# BreakOutBoard_Cyclone.net
KiCad netlist of a schematic drawn in Altium Designer
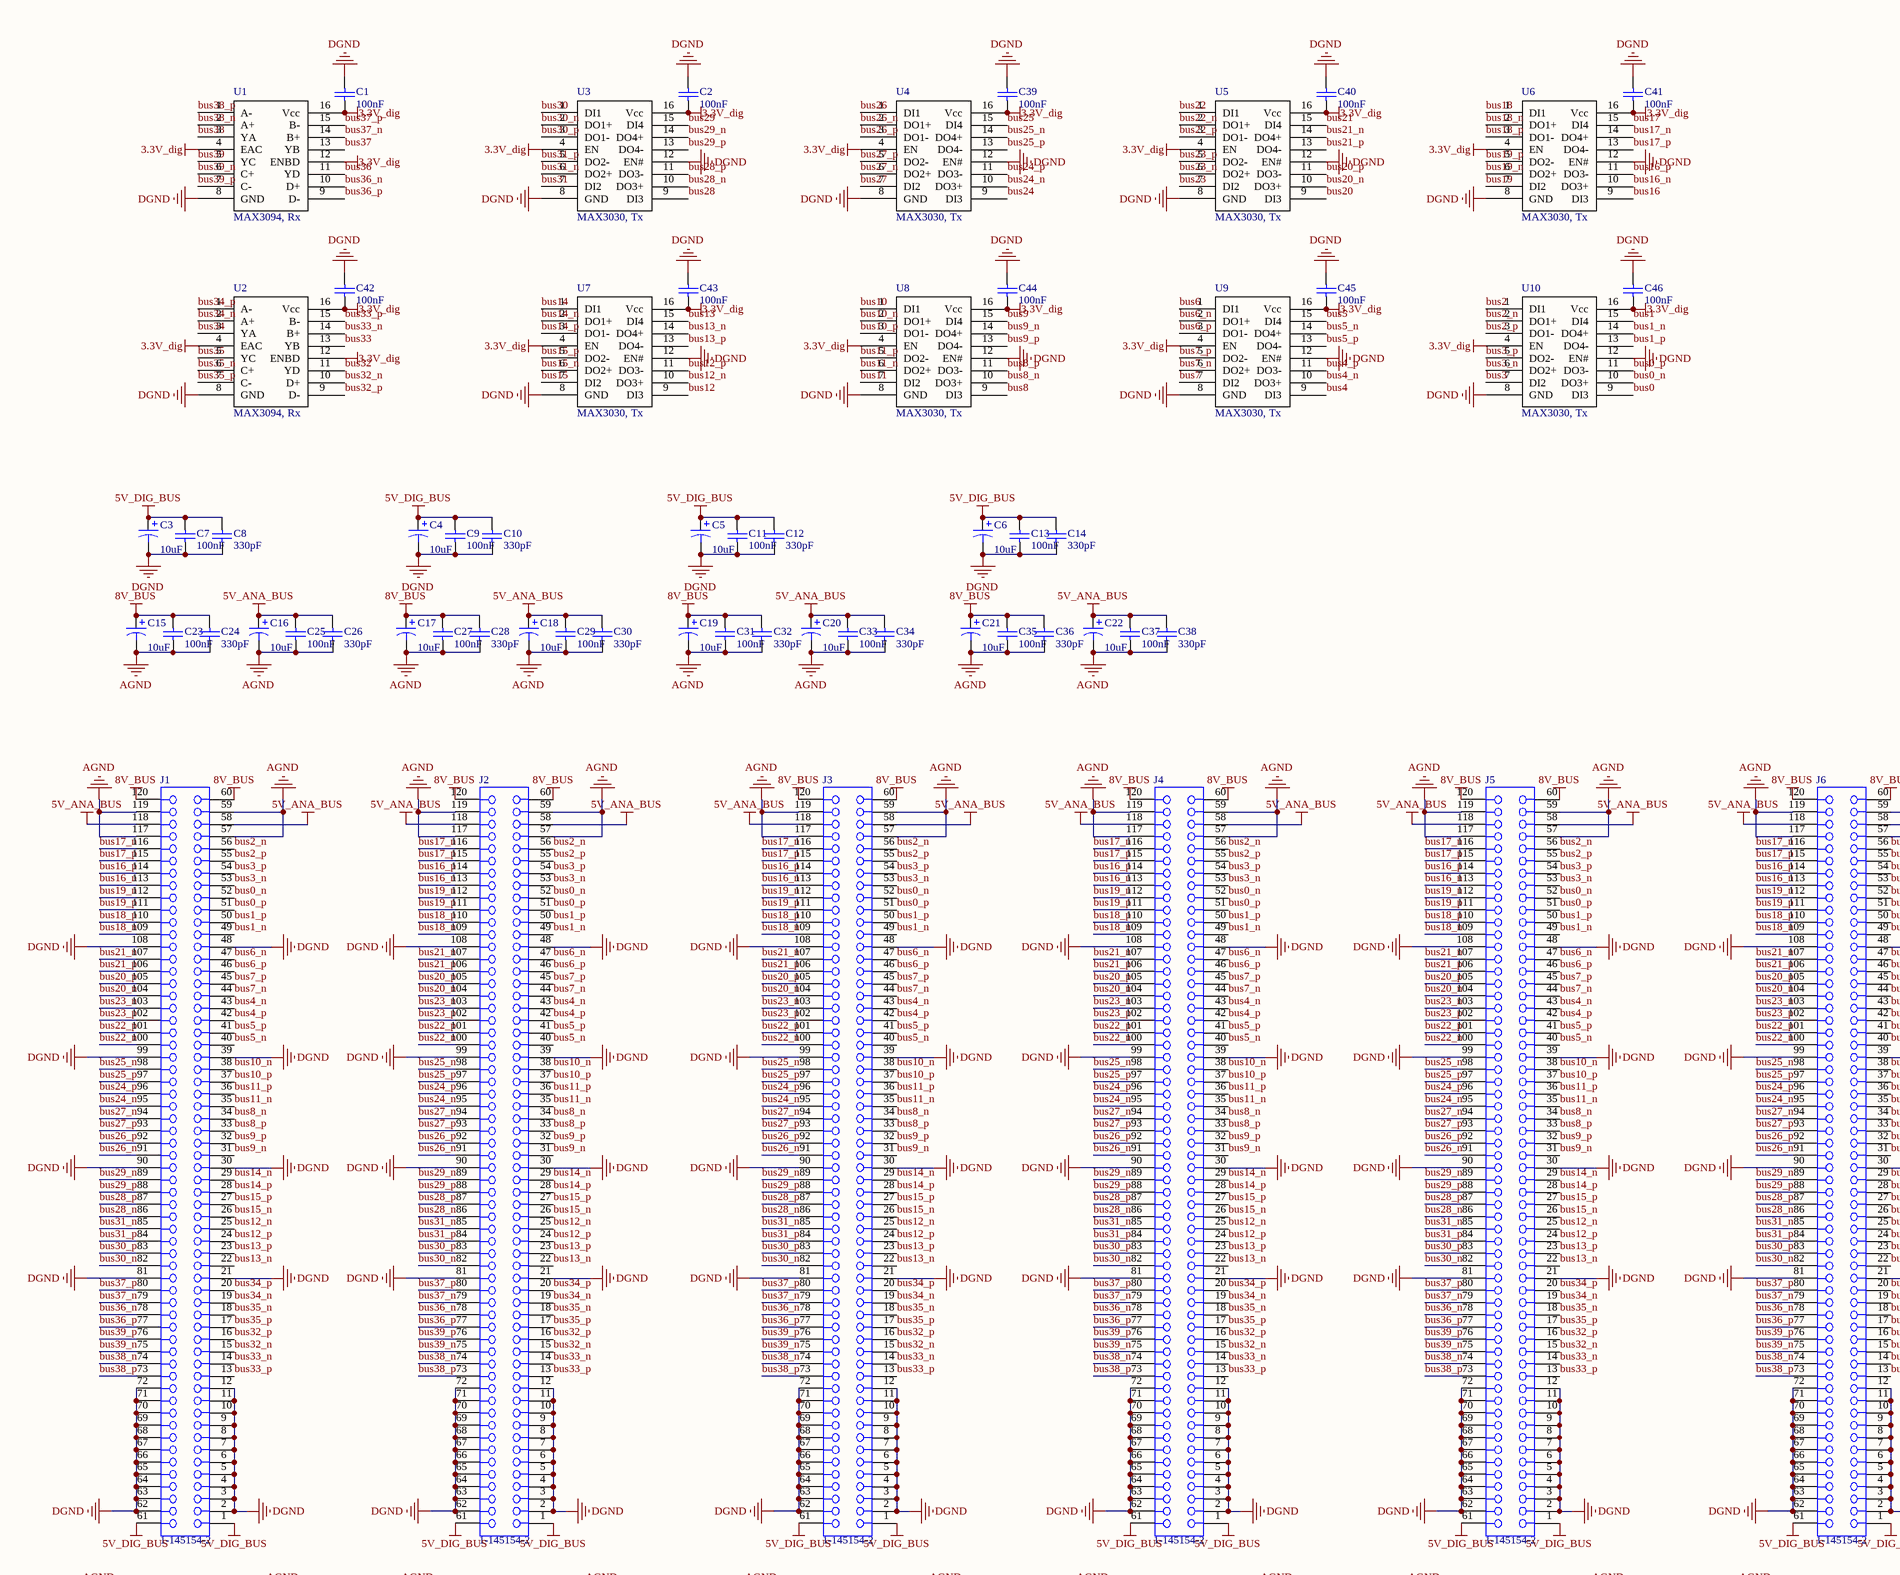
[diagram p0: BreakOutBoard_Cyclone.SchDoc, top left]
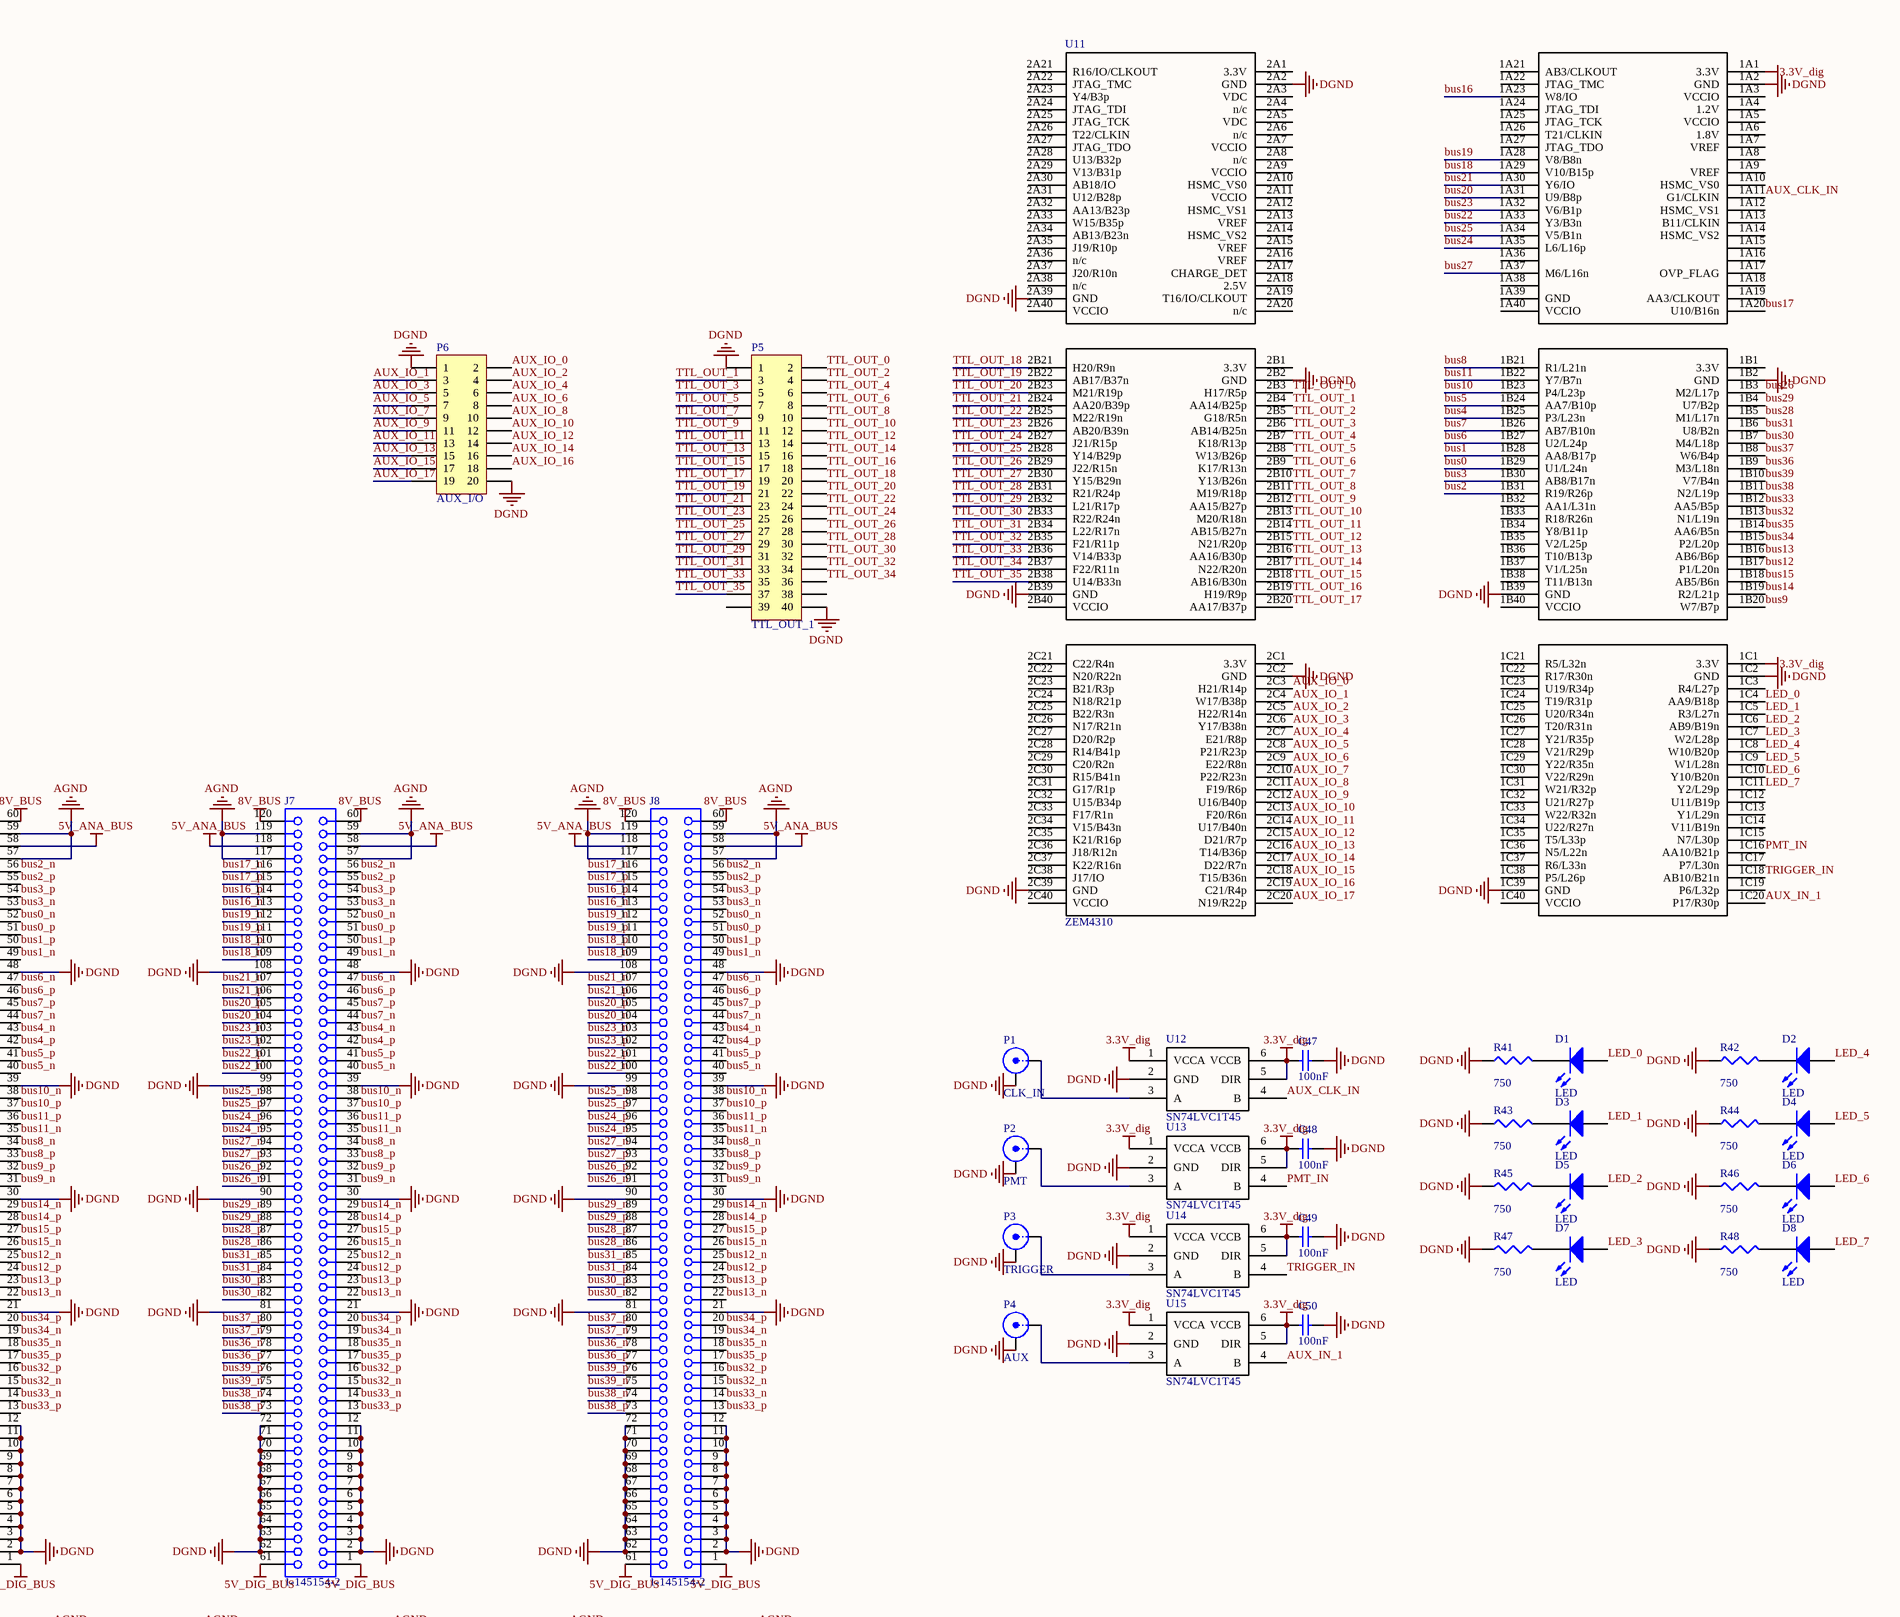
[diagram p1: BreakOutBoard_Cyclone.SchDoc, top right]
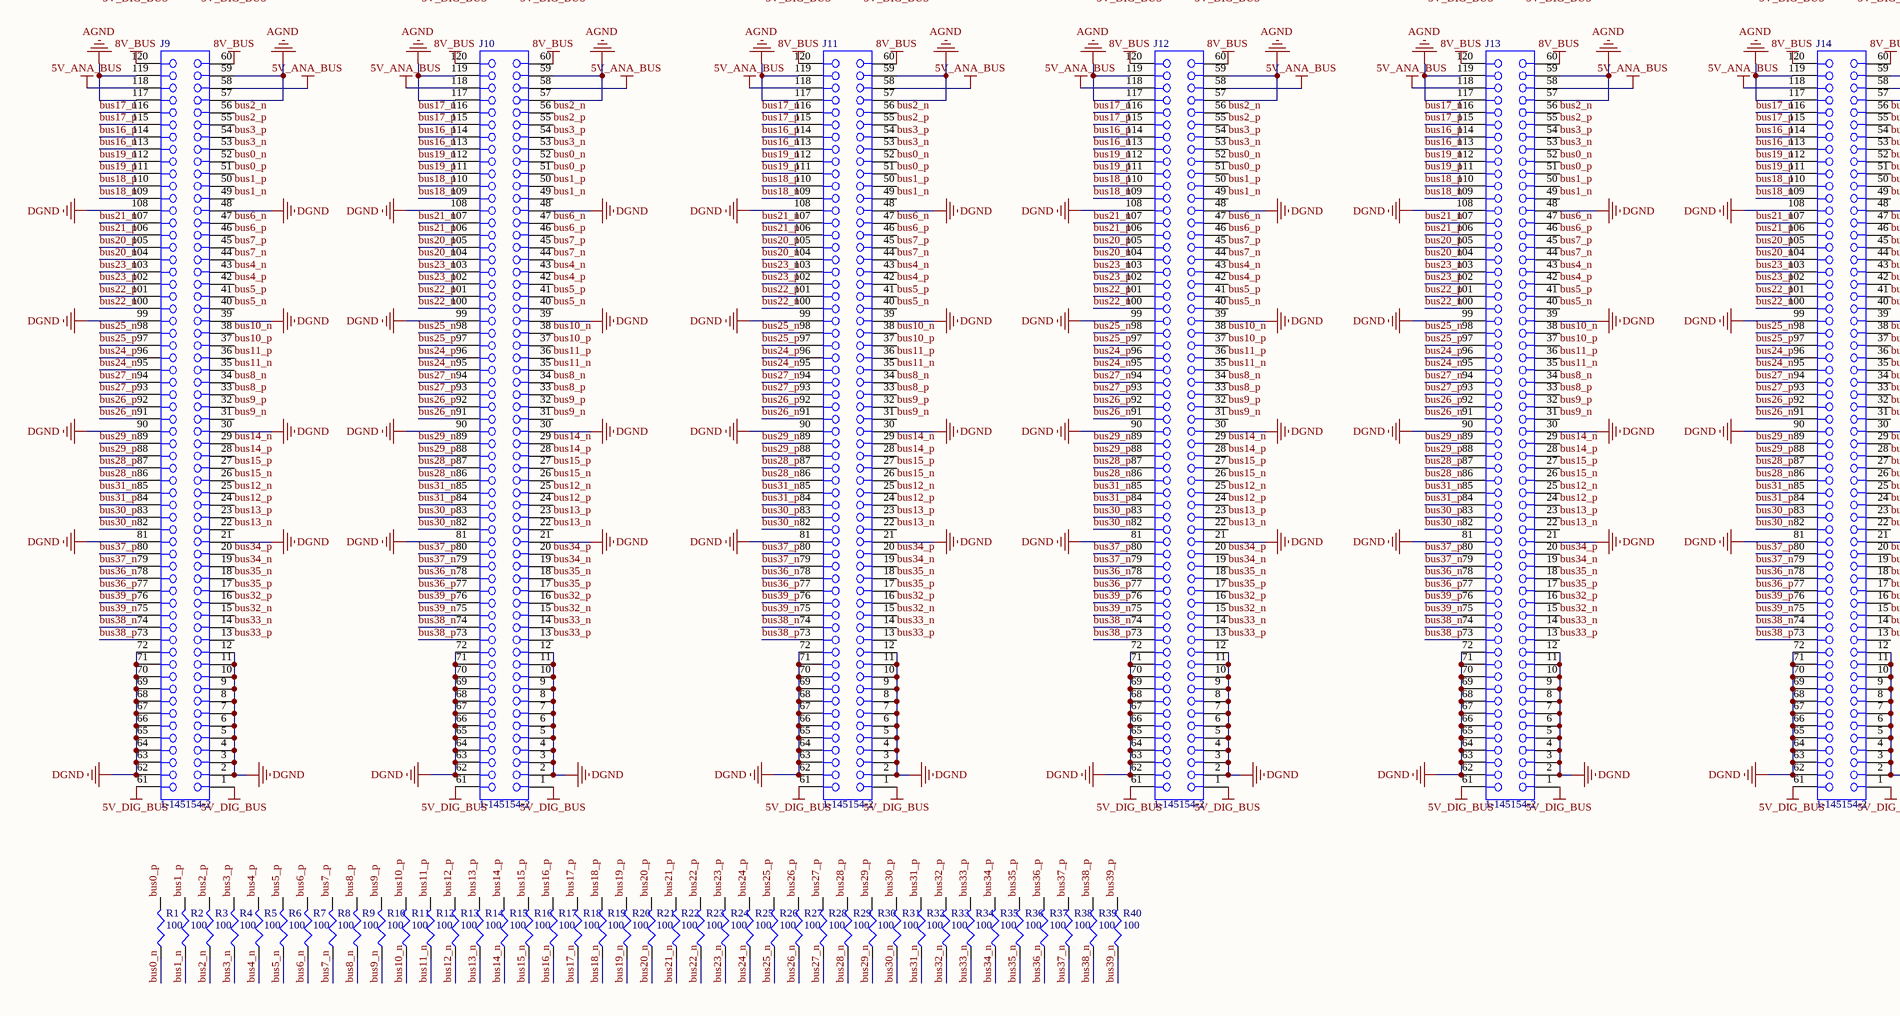
[diagram p2: BreakOutBoard_Cyclone.SchDoc, bottom left]
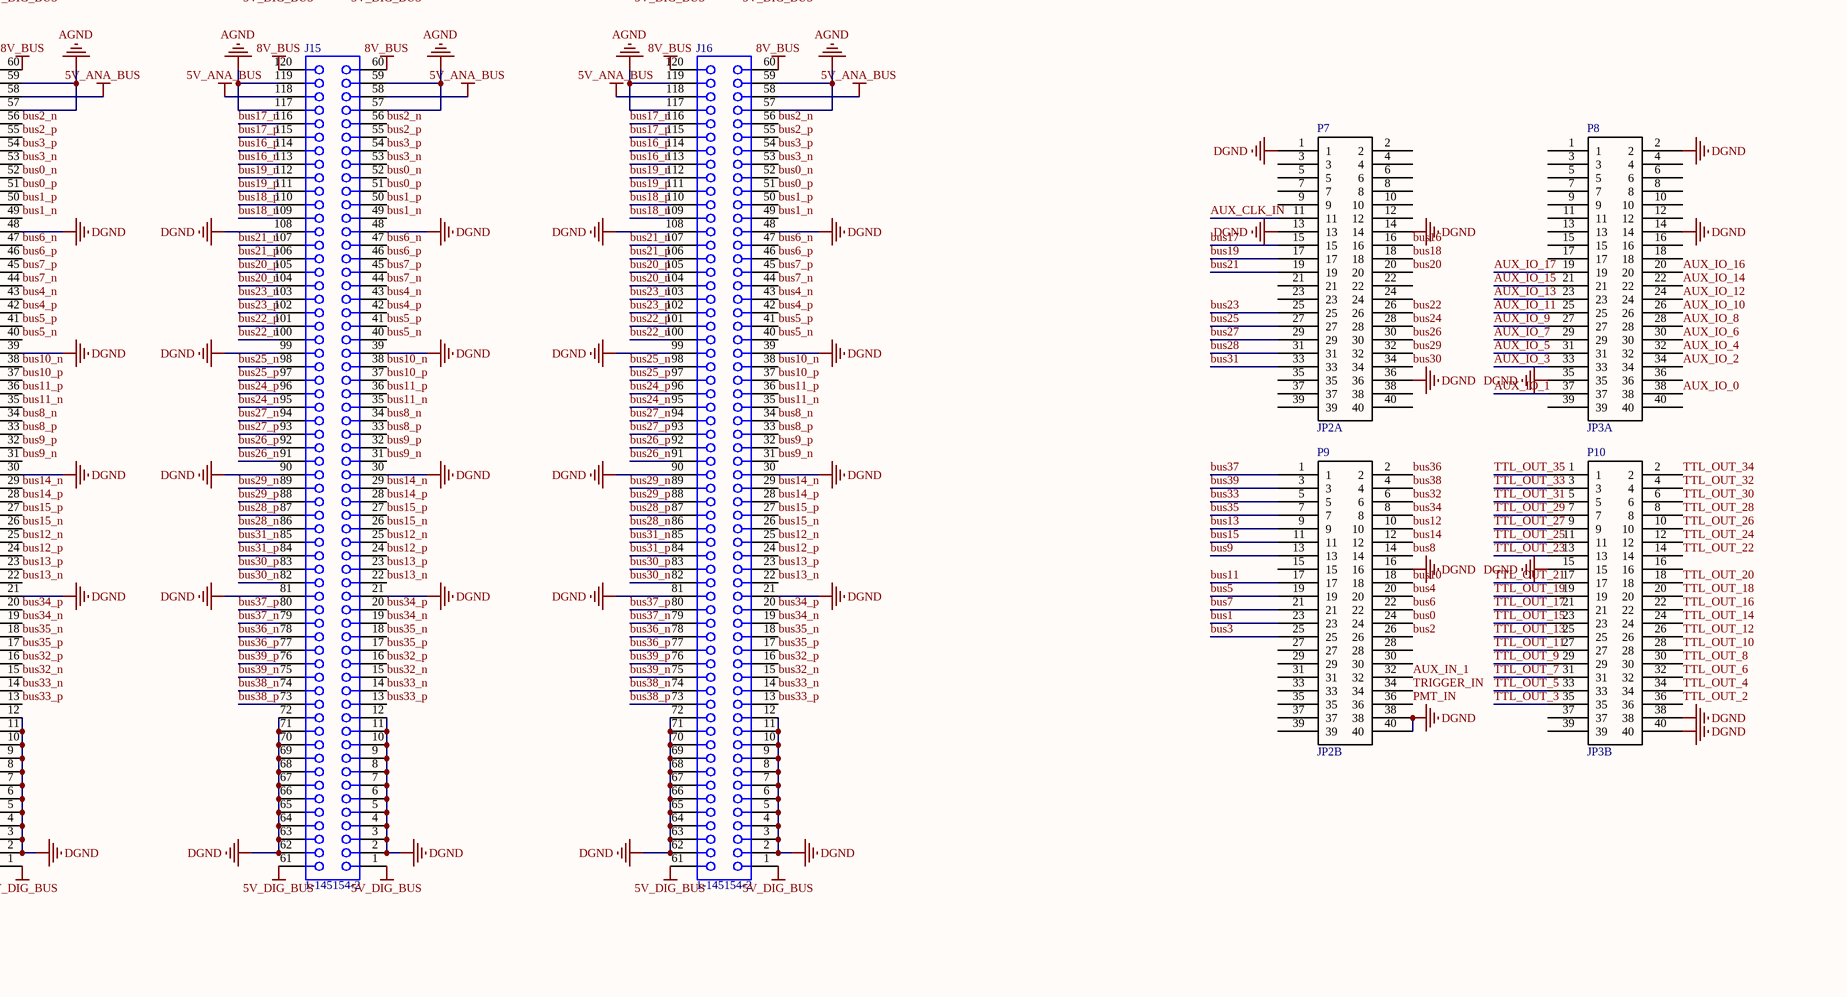
[diagram p3: BreakOutBoard_Cyclone.SchDoc, bottom right]

(export (version "E")
  (design (tool "Eeschema 10.0.6"))
  (components
    (comp (ref "C1")
      (value "100nF")
      (footprint "CAPC2012L")
      (description "Capacitor (Semiconductor SIM Model)")
      (fields (field (name "Comment") "Cap Semi") (field (name "PUBLISHER") "Altium Limited"))
      (libsource (lib "Miscellaneous Devices") (part "Cap Semi"))
    )
    (comp (ref "C2")
      (value "100nF")
      (footprint "CAPC2012L")
      (description "Capacitor (Semiconductor SIM Model)")
      (fields (field (name "Comment") "Cap Semi") (field (name "PUBLISHER") "Altium Limited"))
      (libsource (lib "Miscellaneous Devices") (part "Cap Semi"))
    )
    (comp (ref "C3")
      (value "10uF")
      (footprint "B")
      (description "Polarized Capacitor (Radial)")
      (fields
        (field (name "VOLTAGE") "16V")
        (field (name "Comment") "Cap Pol1")
        (field (name "PUBLISHER") "Altium Limited")
      )
      (libsource (lib "Miscellaneous Devices") (part "Cap Pol1"))
    )
    (comp (ref "C4")
      (value "10uF")
      (footprint "B")
      (description "Polarized Capacitor (Radial)")
      (fields
        (field (name "VOLTAGE") "16V")
        (field (name "Comment") "Cap Pol1")
        (field (name "PUBLISHER") "Altium Limited")
      )
      (libsource (lib "Miscellaneous Devices") (part "Cap Pol1"))
    )
    (comp (ref "C5")
      (value "10uF")
      (footprint "B")
      (description "Polarized Capacitor (Radial)")
      (fields
        (field (name "VOLTAGE") "16V")
        (field (name "Comment") "Cap Pol1")
        (field (name "PUBLISHER") "Altium Limited")
      )
      (libsource (lib "Miscellaneous Devices") (part "Cap Pol1"))
    )
    (comp (ref "C6")
      (value "10uF")
      (footprint "B")
      (description "Polarized Capacitor (Radial)")
      (fields
        (field (name "VOLTAGE") "16V")
        (field (name "Comment") "Cap Pol1")
        (field (name "PUBLISHER") "Altium Limited")
      )
      (libsource (lib "Miscellaneous Devices") (part "Cap Pol1"))
    )
    (comp (ref "C7")
      (value "100nF")
      (footprint "CAPC2012L")
      (description "Capacitor (Semiconductor SIM Model)")
      (fields (field (name "Comment") "Cap Semi") (field (name "PUBLISHER") "Altium Limited"))
      (libsource (lib "Miscellaneous Devices") (part "Cap Semi"))
    )
    (comp (ref "C8")
      (value "330pF")
      (footprint "CAPC2012L")
      (description "Capacitor (Semiconductor SIM Model)")
      (fields (field (name "Comment") "Cap Semi") (field (name "PUBLISHER") "Altium Limited"))
      (libsource (lib "Miscellaneous Devices") (part "Cap Semi"))
    )
    (comp (ref "C9")
      (value "100nF")
      (footprint "CAPC2012L")
      (description "Capacitor (Semiconductor SIM Model)")
      (fields (field (name "Comment") "Cap Semi") (field (name "PUBLISHER") "Altium Limited"))
      (libsource (lib "Miscellaneous Devices") (part "Cap Semi"))
    )
    (comp (ref "C10")
      (value "330pF")
      (footprint "CAPC2012L")
      (description "Capacitor (Semiconductor SIM Model)")
      (fields (field (name "Comment") "Cap Semi") (field (name "PUBLISHER") "Altium Limited"))
      (libsource (lib "Miscellaneous Devices") (part "Cap Semi"))
    )
    (comp (ref "C11")
      (value "100nF")
      (footprint "CAPC2012L")
      (description "Capacitor (Semiconductor SIM Model)")
      (fields (field (name "Comment") "Cap Semi") (field (name "PUBLISHER") "Altium Limited"))
      (libsource (lib "Miscellaneous Devices") (part "Cap Semi"))
    )
    (comp (ref "C12")
      (value "330pF")
      (footprint "CAPC2012L")
      (description "Capacitor (Semiconductor SIM Model)")
      (fields (field (name "Comment") "Cap Semi") (field (name "PUBLISHER") "Altium Limited"))
      (libsource (lib "Miscellaneous Devices") (part "Cap Semi"))
    )
    (comp (ref "C13")
      (value "100nF")
      (footprint "CAPC2012L")
      (description "Capacitor (Semiconductor SIM Model)")
      (fields (field (name "Comment") "Cap Semi") (field (name "PUBLISHER") "Altium Limited"))
      (libsource (lib "Miscellaneous Devices") (part "Cap Semi"))
    )
    (comp (ref "C14")
      (value "330pF")
      (footprint "CAPC2012L")
      (description "Capacitor (Semiconductor SIM Model)")
      (fields (field (name "Comment") "Cap Semi") (field (name "PUBLISHER") "Altium Limited"))
      (libsource (lib "Miscellaneous Devices") (part "Cap Semi"))
    )
    (comp (ref "C15")
      (value "10uF")
      (footprint "B")
      (description "Polarized Capacitor (Radial)")
      (fields
        (field (name "VOLTAGE") "16V")
        (field (name "Comment") "Cap Pol1")
        (field (name "PUBLISHER") "Altium Limited")
      )
      (libsource (lib "Miscellaneous Devices") (part "Cap Pol1"))
    )
    (comp (ref "C16")
      (value "10uF")
      (footprint "B")
      (description "Polarized Capacitor (Radial)")
      (fields
        (field (name "VOLTAGE") "16V")
        (field (name "Comment") "Cap Pol1")
        (field (name "PUBLISHER") "Altium Limited")
      )
      (libsource (lib "Miscellaneous Devices") (part "Cap Pol1"))
    )
    (comp (ref "C17")
      (value "10uF")
      (footprint "B")
      (description "Polarized Capacitor (Radial)")
      (fields
        (field (name "VOLTAGE") "16V")
        (field (name "Comment") "Cap Pol1")
        (field (name "PUBLISHER") "Altium Limited")
      )
      (libsource (lib "Miscellaneous Devices") (part "Cap Pol1"))
    )
    (comp (ref "C18")
      (value "10uF")
      (footprint "B")
      (description "Polarized Capacitor (Radial)")
      (fields
        (field (name "VOLTAGE") "16V")
        (field (name "Comment") "Cap Pol1")
        (field (name "PUBLISHER") "Altium Limited")
      )
      (libsource (lib "Miscellaneous Devices") (part "Cap Pol1"))
    )
    (comp (ref "C19")
      (value "10uF")
      (footprint "B")
      (description "Polarized Capacitor (Radial)")
      (fields
        (field (name "VOLTAGE") "16V")
        (field (name "Comment") "Cap Pol1")
        (field (name "PUBLISHER") "Altium Limited")
      )
      (libsource (lib "Miscellaneous Devices") (part "Cap Pol1"))
    )
    (comp (ref "C20")
      (value "10uF")
      (footprint "B")
      (description "Polarized Capacitor (Radial)")
      (fields
        (field (name "VOLTAGE") "16V")
        (field (name "Comment") "Cap Pol1")
        (field (name "PUBLISHER") "Altium Limited")
      )
      (libsource (lib "Miscellaneous Devices") (part "Cap Pol1"))
    )
    (comp (ref "C21")
      (value "10uF")
      (footprint "B")
      (description "Polarized Capacitor (Radial)")
      (fields
        (field (name "VOLTAGE") "16V")
        (field (name "Comment") "Cap Pol1")
        (field (name "PUBLISHER") "Altium Limited")
      )
      (libsource (lib "Miscellaneous Devices") (part "Cap Pol1"))
    )
    (comp (ref "C22")
      (value "10uF")
      (footprint "B")
      (description "Polarized Capacitor (Radial)")
      (fields
        (field (name "VOLTAGE") "16V")
        (field (name "Comment") "Cap Pol1")
        (field (name "PUBLISHER") "Altium Limited")
      )
      (libsource (lib "Miscellaneous Devices") (part "Cap Pol1"))
    )
    (comp (ref "C23")
      (value "100nF")
      (footprint "CAPC2012L")
      (description "Capacitor (Semiconductor SIM Model)")
      (fields (field (name "Comment") "Cap Semi") (field (name "PUBLISHER") "Altium Limited"))
      (libsource (lib "Miscellaneous Devices") (part "Cap Semi"))
    )
    (comp (ref "C24")
      (value "330pF")
      (footprint "CAPC2012L")
      (description "Capacitor (Semiconductor SIM Model)")
      (fields (field (name "Comment") "Cap Semi") (field (name "PUBLISHER") "Altium Limited"))
      (libsource (lib "Miscellaneous Devices") (part "Cap Semi"))
    )
    (comp (ref "C25")
      (value "100nF")
      (footprint "CAPC2012L")
      (description "Capacitor (Semiconductor SIM Model)")
      (fields (field (name "Comment") "Cap Semi") (field (name "PUBLISHER") "Altium Limited"))
      (libsource (lib "Miscellaneous Devices") (part "Cap Semi"))
    )
    (comp (ref "C26")
      (value "330pF")
      (footprint "CAPC2012L")
      (description "Capacitor (Semiconductor SIM Model)")
      (fields (field (name "Comment") "Cap Semi") (field (name "PUBLISHER") "Altium Limited"))
      (libsource (lib "Miscellaneous Devices") (part "Cap Semi"))
    )
    (comp (ref "C27")
      (value "100nF")
      (footprint "CAPC2012L")
      (description "Capacitor (Semiconductor SIM Model)")
      (fields (field (name "Comment") "Cap Semi") (field (name "PUBLISHER") "Altium Limited"))
      (libsource (lib "Miscellaneous Devices") (part "Cap Semi"))
    )
    (comp (ref "C28")
      (value "330pF")
      (footprint "CAPC2012L")
      (description "Capacitor (Semiconductor SIM Model)")
      (fields (field (name "Comment") "Cap Semi") (field (name "PUBLISHER") "Altium Limited"))
      (libsource (lib "Miscellaneous Devices") (part "Cap Semi"))
    )
    (comp (ref "C29")
      (value "100nF")
      (footprint "CAPC2012L")
      (description "Capacitor (Semiconductor SIM Model)")
      (fields (field (name "Comment") "Cap Semi") (field (name "PUBLISHER") "Altium Limited"))
      (libsource (lib "Miscellaneous Devices") (part "Cap Semi"))
    )
    (comp (ref "C30")
      (value "330pF")
      (footprint "CAPC2012L")
      (description "Capacitor (Semiconductor SIM Model)")
      (fields (field (name "Comment") "Cap Semi") (field (name "PUBLISHER") "Altium Limited"))
      (libsource (lib "Miscellaneous Devices") (part "Cap Semi"))
    )
    (comp (ref "C31")
      (value "100nF")
      (footprint "CAPC2012L")
      (description "Capacitor (Semiconductor SIM Model)")
      (fields (field (name "Comment") "Cap Semi") (field (name "PUBLISHER") "Altium Limited"))
      (libsource (lib "Miscellaneous Devices") (part "Cap Semi"))
    )
    (comp (ref "C32")
      (value "330pF")
      (footprint "CAPC2012L")
      (description "Capacitor (Semiconductor SIM Model)")
      (fields (field (name "Comment") "Cap Semi") (field (name "PUBLISHER") "Altium Limited"))
      (libsource (lib "Miscellaneous Devices") (part "Cap Semi"))
    )
    (comp (ref "C33")
      (value "100nF")
      (footprint "CAPC2012L")
      (description "Capacitor (Semiconductor SIM Model)")
      (fields (field (name "Comment") "Cap Semi") (field (name "PUBLISHER") "Altium Limited"))
      (libsource (lib "Miscellaneous Devices") (part "Cap Semi"))
    )
    (comp (ref "C34")
      (value "330pF")
      (footprint "CAPC2012L")
      (description "Capacitor (Semiconductor SIM Model)")
      (fields (field (name "Comment") "Cap Semi") (field (name "PUBLISHER") "Altium Limited"))
      (libsource (lib "Miscellaneous Devices") (part "Cap Semi"))
    )
    (comp (ref "C35")
      (value "100nF")
      (footprint "CAPC2012L")
      (description "Capacitor (Semiconductor SIM Model)")
      (fields (field (name "Comment") "Cap Semi") (field (name "PUBLISHER") "Altium Limited"))
      (libsource (lib "Miscellaneous Devices") (part "Cap Semi"))
    )
    (comp (ref "C36")
      (value "330pF")
      (footprint "CAPC2012L")
      (description "Capacitor (Semiconductor SIM Model)")
      (fields (field (name "Comment") "Cap Semi") (field (name "PUBLISHER") "Altium Limited"))
      (libsource (lib "Miscellaneous Devices") (part "Cap Semi"))
    )
    (comp (ref "C37")
      (value "100nF")
      (footprint "CAPC2012L")
      (description "Capacitor (Semiconductor SIM Model)")
      (fields (field (name "Comment") "Cap Semi") (field (name "PUBLISHER") "Altium Limited"))
      (libsource (lib "Miscellaneous Devices") (part "Cap Semi"))
    )
    (comp (ref "C38")
      (value "330pF")
      (footprint "CAPC2012L")
      (description "Capacitor (Semiconductor SIM Model)")
      (fields (field (name "Comment") "Cap Semi") (field (name "PUBLISHER") "Altium Limited"))
      (libsource (lib "Miscellaneous Devices") (part "Cap Semi"))
    )
    (comp (ref "C39")
      (value "100nF")
      (footprint "CAPC2012L")
      (description "Capacitor (Semiconductor SIM Model)")
      (fields (field (name "Comment") "Cap Semi") (field (name "PUBLISHER") "Altium Limited"))
      (libsource (lib "Miscellaneous Devices") (part "Cap Semi"))
    )
    (comp (ref "C40")
      (value "100nF")
      (footprint "CAPC2012L")
      (description "Capacitor (Semiconductor SIM Model)")
      (fields (field (name "Comment") "Cap Semi") (field (name "PUBLISHER") "Altium Limited"))
      (libsource (lib "Miscellaneous Devices") (part "Cap Semi"))
    )
    (comp (ref "C41")
      (value "100nF")
      (footprint "CAPC2012L")
      (description "Capacitor (Semiconductor SIM Model)")
      (fields (field (name "Comment") "Cap Semi") (field (name "PUBLISHER") "Altium Limited"))
      (libsource (lib "Miscellaneous Devices") (part "Cap Semi"))
    )
    (comp (ref "C42")
      (value "100nF")
      (footprint "CAPC2012L")
      (description "Capacitor (Semiconductor SIM Model)")
      (fields (field (name "Comment") "Cap Semi") (field (name "PUBLISHER") "Altium Limited"))
      (libsource (lib "Miscellaneous Devices") (part "Cap Semi"))
    )
    (comp (ref "C43")
      (value "100nF")
      (footprint "CAPC2012L")
      (description "Capacitor (Semiconductor SIM Model)")
      (fields (field (name "Comment") "Cap Semi") (field (name "PUBLISHER") "Altium Limited"))
      (libsource (lib "Miscellaneous Devices") (part "Cap Semi"))
    )
    (comp (ref "C44")
      (value "100nF")
      (footprint "CAPC2012L")
      (description "Capacitor (Semiconductor SIM Model)")
      (fields (field (name "Comment") "Cap Semi") (field (name "PUBLISHER") "Altium Limited"))
      (libsource (lib "Miscellaneous Devices") (part "Cap Semi"))
    )
    (comp (ref "C45")
      (value "100nF")
      (footprint "CAPC2012L")
      (description "Capacitor (Semiconductor SIM Model)")
      (fields (field (name "Comment") "Cap Semi") (field (name "PUBLISHER") "Altium Limited"))
      (libsource (lib "Miscellaneous Devices") (part "Cap Semi"))
    )
    (comp (ref "C46")
      (value "100nF")
      (footprint "CAPC2012L")
      (description "Capacitor (Semiconductor SIM Model)")
      (fields (field (name "Comment") "Cap Semi") (field (name "PUBLISHER") "Altium Limited"))
      (libsource (lib "Miscellaneous Devices") (part "Cap Semi"))
    )
    (comp (ref "C47")
      (value "100nF")
      (footprint "CAPC2012L")
      (description "Capacitor (Semiconductor SIM Model)")
      (fields (field (name "Comment") "Cap Semi") (field (name "PUBLISHER") "Altium Limited"))
      (libsource (lib "Miscellaneous Devices") (part "Cap Semi"))
    )
    (comp (ref "C48")
      (value "100nF")
      (footprint "CAPC2012L")
      (description "Capacitor (Semiconductor SIM Model)")
      (fields (field (name "Comment") "Cap Semi") (field (name "PUBLISHER") "Altium Limited"))
      (libsource (lib "Miscellaneous Devices") (part "Cap Semi"))
    )
    (comp (ref "C49")
      (value "100nF")
      (footprint "CAPC2012L")
      (description "Capacitor (Semiconductor SIM Model)")
      (fields (field (name "Comment") "Cap Semi") (field (name "PUBLISHER") "Altium Limited"))
      (libsource (lib "Miscellaneous Devices") (part "Cap Semi"))
    )
    (comp (ref "C50")
      (value "100nF")
      (footprint "CAPC2012L")
      (description "Capacitor (Semiconductor SIM Model)")
      (fields (field (name "Comment") "Cap Semi") (field (name "PUBLISHER") "Altium Limited"))
      (libsource (lib "Miscellaneous Devices") (part "Cap Semi"))
    )
    (comp (ref "D1")
      (value "LED")
      (footprint "RESC2012M")
      (description "Typical BLUE SiC LED")
      (fields (field (name "PUBLISHER") "Altium Limited"))
      (libsource (lib "Miscellaneous Devices") (part "LED3"))
    )
    (comp (ref "D2")
      (value "LED")
      (footprint "RESC2012M")
      (description "Typical BLUE SiC LED")
      (fields (field (name "PUBLISHER") "Altium Limited"))
      (libsource (lib "Miscellaneous Devices") (part "LED3"))
    )
    (comp (ref "D3")
      (value "LED")
      (footprint "RESC2012M")
      (description "Typical BLUE SiC LED")
      (fields (field (name "PUBLISHER") "Altium Limited"))
      (libsource (lib "Miscellaneous Devices") (part "LED3"))
    )
    (comp (ref "D4")
      (value "LED")
      (footprint "RESC2012M")
      (description "Typical BLUE SiC LED")
      (fields (field (name "PUBLISHER") "Altium Limited"))
      (libsource (lib "Miscellaneous Devices") (part "LED3"))
    )
    (comp (ref "D5")
      (value "LED")
      (footprint "RESC2012M")
      (description "Typical BLUE SiC LED")
      (fields (field (name "PUBLISHER") "Altium Limited"))
      (libsource (lib "Miscellaneous Devices") (part "LED3"))
    )
    (comp (ref "D6")
      (value "LED")
      (footprint "RESC2012M")
      (description "Typical BLUE SiC LED")
      (fields (field (name "PUBLISHER") "Altium Limited"))
      (libsource (lib "Miscellaneous Devices") (part "LED3"))
    )
    (comp (ref "D7")
      (value "LED")
      (footprint "RESC2012M")
      (description "Typical BLUE SiC LED")
      (fields (field (name "PUBLISHER") "Altium Limited"))
      (libsource (lib "Miscellaneous Devices") (part "LED3"))
    )
    (comp (ref "D8")
      (value "LED")
      (footprint "RESC2012M")
      (description "Typical BLUE SiC LED")
      (fields (field (name "PUBLISHER") "Altium Limited"))
      (libsource (lib "Miscellaneous Devices") (part "LED3"))
    )
    (comp (ref "J1")
      (value "1-145154-2")
      (footprint "1-145154-2")
      (description "Connector Assembly, 60 Dual Position, 1.27 [.050] Series, Standard Edge")
      (fields (field (name "VOLTAGE") "3.3V, 5V") (field (name "PUBLISHER") "Altium Limited"))
      (libsource (lib "AMP Card Edge 050 Series PCI") (part "1-145154-2"))
    )
    (comp (ref "J2")
      (value "1-145154-2")
      (footprint "1-145154-2")
      (description "Connector Assembly, 60 Dual Position, 1.27 [.050] Series, Standard Edge")
      (fields (field (name "VOLTAGE") "3.3V, 5V") (field (name "PUBLISHER") "Altium Limited"))
      (libsource (lib "AMP Card Edge 050 Series PCI") (part "1-145154-2"))
    )
    (comp (ref "J3")
      (value "1-145154-2")
      (footprint "1-145154-2")
      (description "Connector Assembly, 60 Dual Position, 1.27 [.050] Series, Standard Edge")
      (fields (field (name "VOLTAGE") "3.3V, 5V") (field (name "PUBLISHER") "Altium Limited"))
      (libsource (lib "AMP Card Edge 050 Series PCI") (part "1-145154-2"))
    )
    (comp (ref "J4")
      (value "1-145154-2")
      (footprint "1-145154-2")
      (description "Connector Assembly, 60 Dual Position, 1.27 [.050] Series, Standard Edge")
      (fields (field (name "VOLTAGE") "3.3V, 5V") (field (name "PUBLISHER") "Altium Limited"))
      (libsource (lib "AMP Card Edge 050 Series PCI") (part "1-145154-2"))
    )
    (comp (ref "J5")
      (value "1-145154-2")
      (footprint "1-145154-2")
      (description "Connector Assembly, 60 Dual Position, 1.27 [.050] Series, Standard Edge")
      (fields (field (name "VOLTAGE") "3.3V, 5V") (field (name "PUBLISHER") "Altium Limited"))
      (libsource (lib "AMP Card Edge 050 Series PCI") (part "1-145154-2"))
    )
    (comp (ref "J6")
      (value "1-145154-2")
      (footprint "1-145154-2")
      (description "Connector Assembly, 60 Dual Position, 1.27 [.050] Series, Standard Edge")
      (fields (field (name "VOLTAGE") "3.3V, 5V") (field (name "PUBLISHER") "Altium Limited"))
      (libsource (lib "AMP Card Edge 050 Series PCI") (part "1-145154-2"))
    )
    (comp (ref "J7")
      (value "1-145154-2")
      (footprint "1-145154-2")
      (description "Connector Assembly, 60 Dual Position, 1.27 [.050] Series, Standard Edge")
      (fields (field (name "VOLTAGE") "3.3V, 5V") (field (name "PUBLISHER") "Altium Limited"))
      (libsource (lib "AMP Card Edge 050 Series PCI") (part "1-145154-2"))
    )
    (comp (ref "J8")
      (value "1-145154-2")
      (footprint "1-145154-2")
      (description "Connector Assembly, 60 Dual Position, 1.27 [.050] Series, Standard Edge")
      (fields (field (name "VOLTAGE") "3.3V, 5V") (field (name "PUBLISHER") "Altium Limited"))
      (libsource (lib "AMP Card Edge 050 Series PCI") (part "1-145154-2"))
    )
    (comp (ref "J9")
      (value "1-145154-2")
      (footprint "1-145154-2")
      (description "Connector Assembly, 60 Dual Position, 1.27 [.050] Series, Standard Edge")
      (fields (field (name "VOLTAGE") "3.3V, 5V") (field (name "PUBLISHER") "Altium Limited"))
      (libsource (lib "AMP Card Edge 050 Series PCI") (part "1-145154-2"))
    )
    (comp (ref "J10")
      (value "1-145154-2")
      (footprint "1-145154-2")
      (description "Connector Assembly, 60 Dual Position, 1.27 [.050] Series, Standard Edge")
      (fields (field (name "VOLTAGE") "3.3V, 5V") (field (name "PUBLISHER") "Altium Limited"))
      (libsource (lib "AMP Card Edge 050 Series PCI") (part "1-145154-2"))
    )
    (comp (ref "J11")
      (value "1-145154-2")
      (footprint "1-145154-2")
      (description "Connector Assembly, 60 Dual Position, 1.27 [.050] Series, Standard Edge")
      (fields (field (name "VOLTAGE") "3.3V, 5V") (field (name "PUBLISHER") "Altium Limited"))
      (libsource (lib "AMP Card Edge 050 Series PCI") (part "1-145154-2"))
    )
    (comp (ref "J12")
      (value "1-145154-2")
      (footprint "1-145154-2")
      (description "Connector Assembly, 60 Dual Position, 1.27 [.050] Series, Standard Edge")
      (fields (field (name "VOLTAGE") "3.3V, 5V") (field (name "PUBLISHER") "Altium Limited"))
      (libsource (lib "AMP Card Edge 050 Series PCI") (part "1-145154-2"))
    )
    (comp (ref "J13")
      (value "1-145154-2")
      (footprint "1-145154-2")
      (description "Connector Assembly, 60 Dual Position, 1.27 [.050] Series, Standard Edge")
      (fields (field (name "VOLTAGE") "3.3V, 5V") (field (name "PUBLISHER") "Altium Limited"))
      (libsource (lib "AMP Card Edge 050 Series PCI") (part "1-145154-2"))
    )
    (comp (ref "J14")
      (value "1-145154-2")
      (footprint "1-145154-2")
      (description "Connector Assembly, 60 Dual Position, 1.27 [.050] Series, Standard Edge")
      (fields (field (name "VOLTAGE") "3.3V, 5V") (field (name "PUBLISHER") "Altium Limited"))
      (libsource (lib "AMP Card Edge 050 Series PCI") (part "1-145154-2"))
    )
    (comp (ref "J15")
      (value "1-145154-2")
      (footprint "1-145154-2")
      (description "Connector Assembly, 60 Dual Position, 1.27 [.050] Series, Standard Edge")
      (fields (field (name "VOLTAGE") "3.3V, 5V") (field (name "PUBLISHER") "Altium Limited"))
      (libsource (lib "AMP Card Edge 050 Series PCI") (part "1-145154-2"))
    )
    (comp (ref "J16")
      (value "1-145154-2")
      (footprint "1-145154-2")
      (description "Connector Assembly, 60 Dual Position, 1.27 [.050] Series, Standard Edge")
      (fields (field (name "VOLTAGE") "3.3V, 5V") (field (name "PUBLISHER") "Altium Limited"))
      (libsource (lib "AMP Card Edge 050 Series PCI") (part "1-145154-2"))
    )
    (comp (ref "P1")
      (value "CLK_IN")
      (footprint "BNC_RA CON")
      (description "BNC Elbow Connector")
      (fields (field (name "PUBLISHER") "Altium Limited"))
      (libsource (lib "Miscellaneous Connectors") (part "BNC"))
    )
    (comp (ref "P2")
      (value "PMT")
      (footprint "BNC_RA CON")
      (description "BNC Elbow Connector")
      (fields (field (name "PUBLISHER") "Altium Limited"))
      (libsource (lib "Miscellaneous Connectors") (part "BNC"))
    )
    (comp (ref "P3")
      (value "TRIGGER")
      (footprint "BNC_RA CON")
      (description "BNC Elbow Connector")
      (fields (field (name "PUBLISHER") "Altium Limited"))
      (libsource (lib "Miscellaneous Connectors") (part "BNC"))
    )
    (comp (ref "P4")
      (value "AUX")
      (footprint "BNC_RA CON")
      (description "BNC Elbow Connector")
      (fields (field (name "PUBLISHER") "Altium Limited"))
      (libsource (lib "Miscellaneous Connectors") (part "BNC"))
    )
    (comp (ref "P5")
      (value "TTL_OUT_1")
      (footprint "HDR2X20")
      (description "Header, 20-Pin, Dual row")
      (fields (field (name "PUBLISHER") "Altium Limited"))
      (libsource (lib "Miscellaneous Connectors") (part "Header 20X2"))
    )
    (comp (ref "P6")
      (value "AUX_I/O")
      (footprint "HDR2X10")
      (description "Header, 10-Pin, Dual row")
      (fields (field (name "PUBLISHER") "Altium Limited"))
      (libsource (lib "Miscellaneous Connectors") (part "Header 10X2"))
    )
    (comp (ref "P7")
      (value "JP2A")
      (footprint "connector_40pos_2mm")
      (description "2 mm connector 40 positions")
      (fields (field (name "PUBLISHER") "Altium Limited"))
      (libsource (lib "HH_chips") (part "CONN_40_2mm"))
    )
    (comp (ref "P8")
      (value "JP3A")
      (footprint "connector_40pos_2mm")
      (description "2 mm connector 40 positions")
      (fields (field (name "PUBLISHER") "Altium Limited"))
      (libsource (lib "HH_chips") (part "CONN_40_2mm"))
    )
    (comp (ref "P9")
      (value "JP2B")
      (footprint "connector_40pos_2mm")
      (description "2 mm connector 40 positions")
      (fields (field (name "PUBLISHER") "Altium Limited"))
      (libsource (lib "HH_chips") (part "CONN_40_2mm"))
    )
    (comp (ref "P10")
      (value "JP3B")
      (footprint "connector_40pos_2mm")
      (description "2 mm connector 40 positions")
      (fields (field (name "PUBLISHER") "Altium Limited"))
      (libsource (lib "HH_chips") (part "CONN_40_2mm"))
    )
    (comp (ref "R1")
      (value "100")
      (footprint "RESC3216L")
      (description "Resistor")
      (fields (field (name "PUBLISHER") "Altium Limited"))
      (libsource (lib "Miscellaneous Devices") (part "Res3"))
    )
    (comp (ref "R2")
      (value "100")
      (footprint "RESC3216L")
      (description "Resistor")
      (fields (field (name "PUBLISHER") "Altium Limited"))
      (libsource (lib "Miscellaneous Devices") (part "Res3"))
    )
    (comp (ref "R3")
      (value "100")
      (footprint "RESC3216L")
      (description "Resistor")
      (fields (field (name "PUBLISHER") "Altium Limited"))
      (libsource (lib "Miscellaneous Devices") (part "Res3"))
    )
    (comp (ref "R4")
      (value "100")
      (footprint "RESC3216L")
      (description "Resistor")
      (fields (field (name "PUBLISHER") "Altium Limited"))
      (libsource (lib "Miscellaneous Devices") (part "Res3"))
    )
    (comp (ref "R5")
      (value "100")
      (footprint "RESC3216L")
      (description "Resistor")
      (fields (field (name "PUBLISHER") "Altium Limited"))
      (libsource (lib "Miscellaneous Devices") (part "Res3"))
    )
    (comp (ref "R6")
      (value "100")
      (footprint "RESC3216L")
      (description "Resistor")
      (fields (field (name "PUBLISHER") "Altium Limited"))
      (libsource (lib "Miscellaneous Devices") (part "Res3"))
    )
    (comp (ref "R7")
      (value "100")
      (footprint "RESC3216L")
      (description "Resistor")
      (fields (field (name "PUBLISHER") "Altium Limited"))
      (libsource (lib "Miscellaneous Devices") (part "Res3"))
    )
    (comp (ref "R8")
      (value "100")
      (footprint "RESC3216L")
      (description "Resistor")
      (fields (field (name "PUBLISHER") "Altium Limited"))
      (libsource (lib "Miscellaneous Devices") (part "Res3"))
    )
    (comp (ref "R9")
      (value "100")
      (footprint "RESC3216L")
      (description "Resistor")
      (fields (field (name "PUBLISHER") "Altium Limited"))
      (libsource (lib "Miscellaneous Devices") (part "Res3"))
    )
    (comp (ref "R10")
      (value "100")
      (footprint "RESC3216L")
      (description "Resistor")
      (fields (field (name "PUBLISHER") "Altium Limited"))
      (libsource (lib "Miscellaneous Devices") (part "Res3"))
    )
    (comp (ref "R11")
      (value "100")
      (footprint "RESC3216L")
      (description "Resistor")
      (fields (field (name "PUBLISHER") "Altium Limited"))
      (libsource (lib "Miscellaneous Devices") (part "Res3"))
    )
    (comp (ref "R12")
      (value "100")
      (footprint "RESC3216L")
      (description "Resistor")
      (fields (field (name "PUBLISHER") "Altium Limited"))
      (libsource (lib "Miscellaneous Devices") (part "Res3"))
    )
    (comp (ref "R13")
      (value "100")
      (footprint "RESC3216L")
      (description "Resistor")
      (fields (field (name "PUBLISHER") "Altium Limited"))
      (libsource (lib "Miscellaneous Devices") (part "Res3"))
    )
    (comp (ref "R14")
      (value "100")
      (footprint "RESC3216L")
      (description "Resistor")
      (fields (field (name "PUBLISHER") "Altium Limited"))
      (libsource (lib "Miscellaneous Devices") (part "Res3"))
    )
    (comp (ref "R15")
      (value "100")
      (footprint "RESC3216L")
      (description "Resistor")
      (fields (field (name "PUBLISHER") "Altium Limited"))
      (libsource (lib "Miscellaneous Devices") (part "Res3"))
    )
    (comp (ref "R16")
      (value "100")
      (footprint "RESC3216L")
      (description "Resistor")
      (fields (field (name "PUBLISHER") "Altium Limited"))
      (libsource (lib "Miscellaneous Devices") (part "Res3"))
    )
    (comp (ref "R17")
      (value "100")
      (footprint "RESC3216L")
      (description "Resistor")
      (fields (field (name "PUBLISHER") "Altium Limited"))
      (libsource (lib "Miscellaneous Devices") (part "Res3"))
    )
    (comp (ref "R18")
      (value "100")
      (footprint "RESC3216L")
      (description "Resistor")
      (fields (field (name "PUBLISHER") "Altium Limited"))
      (libsource (lib "Miscellaneous Devices") (part "Res3"))
    )
    (comp (ref "R19")
      (value "100")
      (footprint "RESC3216L")
      (description "Resistor")
      (fields (field (name "PUBLISHER") "Altium Limited"))
      (libsource (lib "Miscellaneous Devices") (part "Res3"))
    )
    (comp (ref "R20")
      (value "100")
      (footprint "RESC3216L")
      (description "Resistor")
      (fields (field (name "PUBLISHER") "Altium Limited"))
      (libsource (lib "Miscellaneous Devices") (part "Res3"))
    )
    (comp (ref "R21")
      (value "100")
      (footprint "RESC3216L")
      (description "Resistor")
      (fields (field (name "PUBLISHER") "Altium Limited"))
      (libsource (lib "Miscellaneous Devices") (part "Res3"))
    )
    (comp (ref "R22")
      (value "100")
      (footprint "RESC3216L")
      (description "Resistor")
      (fields (field (name "PUBLISHER") "Altium Limited"))
      (libsource (lib "Miscellaneous Devices") (part "Res3"))
    )
    (comp (ref "R23")
      (value "100")
      (footprint "RESC3216L")
      (description "Resistor")
      (fields (field (name "PUBLISHER") "Altium Limited"))
      (libsource (lib "Miscellaneous Devices") (part "Res3"))
    )
    (comp (ref "R24")
      (value "100")
      (footprint "RESC3216L")
      (description "Resistor")
      (fields (field (name "PUBLISHER") "Altium Limited"))
      (libsource (lib "Miscellaneous Devices") (part "Res3"))
    )
    (comp (ref "R25")
      (value "100")
      (footprint "RESC3216L")
      (description "Resistor")
      (fields (field (name "PUBLISHER") "Altium Limited"))
      (libsource (lib "Miscellaneous Devices") (part "Res3"))
    )
    (comp (ref "R26")
      (value "100")
      (footprint "RESC3216L")
      (description "Resistor")
      (fields (field (name "PUBLISHER") "Altium Limited"))
      (libsource (lib "Miscellaneous Devices") (part "Res3"))
    )
    (comp (ref "R27")
      (value "100")
      (footprint "RESC3216L")
      (description "Resistor")
      (fields (field (name "PUBLISHER") "Altium Limited"))
      (libsource (lib "Miscellaneous Devices") (part "Res3"))
    )
    (comp (ref "R28")
      (value "100")
      (footprint "RESC3216L")
      (description "Resistor")
      (fields (field (name "PUBLISHER") "Altium Limited"))
      (libsource (lib "Miscellaneous Devices") (part "Res3"))
    )
    (comp (ref "R29")
      (value "100")
      (footprint "RESC3216L")
      (description "Resistor")
      (fields (field (name "PUBLISHER") "Altium Limited"))
      (libsource (lib "Miscellaneous Devices") (part "Res3"))
    )
    (comp (ref "R30")
      (value "100")
      (footprint "RESC3216L")
      (description "Resistor")
      (fields (field (name "PUBLISHER") "Altium Limited"))
      (libsource (lib "Miscellaneous Devices") (part "Res3"))
    )
    (comp (ref "R31")
      (value "100")
      (footprint "RESC3216L")
      (description "Resistor")
      (fields (field (name "PUBLISHER") "Altium Limited"))
      (libsource (lib "Miscellaneous Devices") (part "Res3"))
    )
    (comp (ref "R32")
      (value "100")
      (footprint "RESC3216L")
      (description "Resistor")
      (fields (field (name "PUBLISHER") "Altium Limited"))
      (libsource (lib "Miscellaneous Devices") (part "Res3"))
    )
    (comp (ref "R33")
      (value "100")
      (footprint "RESC3216L")
      (description "Resistor")
      (fields (field (name "PUBLISHER") "Altium Limited"))
      (libsource (lib "Miscellaneous Devices") (part "Res3"))
    )
    (comp (ref "R34")
      (value "100")
      (footprint "RESC3216L")
      (description "Resistor")
      (fields (field (name "PUBLISHER") "Altium Limited"))
      (libsource (lib "Miscellaneous Devices") (part "Res3"))
    )
    (comp (ref "R35")
      (value "100")
      (footprint "RESC3216L")
      (description "Resistor")
      (fields (field (name "PUBLISHER") "Altium Limited"))
      (libsource (lib "Miscellaneous Devices") (part "Res3"))
    )
    (comp (ref "R36")
      (value "100")
      (footprint "RESC3216L")
      (description "Resistor")
      (fields (field (name "PUBLISHER") "Altium Limited"))
      (libsource (lib "Miscellaneous Devices") (part "Res3"))
    )
    (comp (ref "R37")
      (value "100")
      (footprint "RESC3216L")
      (description "Resistor")
      (fields (field (name "PUBLISHER") "Altium Limited"))
      (libsource (lib "Miscellaneous Devices") (part "Res3"))
    )
    (comp (ref "R38")
      (value "100")
      (footprint "RESC3216L")
      (description "Resistor")
      (fields (field (name "PUBLISHER") "Altium Limited"))
      (libsource (lib "Miscellaneous Devices") (part "Res3"))
    )
    (comp (ref "R39")
      (value "100")
      (footprint "RESC3216L")
      (description "Resistor")
      (fields (field (name "PUBLISHER") "Altium Limited"))
      (libsource (lib "Miscellaneous Devices") (part "Res3"))
    )
    (comp (ref "R40")
      (value "100")
      (footprint "RESC3216L")
      (description "Resistor")
      (fields (field (name "PUBLISHER") "Altium Limited"))
      (libsource (lib "Miscellaneous Devices") (part "Res3"))
    )
    (comp (ref "R41")
      (value "750")
      (footprint "RESC2012M")
      (description "Resistor")
      (fields (field (name "Comment") "Res3") (field (name "PUBLISHER") "Altium Limited"))
      (libsource (lib "Miscellaneous Devices") (part "Res3"))
    )
    (comp (ref "R42")
      (value "750")
      (footprint "RESC2012M")
      (description "Resistor")
      (fields (field (name "Comment") "Res3") (field (name "PUBLISHER") "Altium Limited"))
      (libsource (lib "Miscellaneous Devices") (part "Res3"))
    )
    (comp (ref "R43")
      (value "750")
      (footprint "RESC2012M")
      (description "Resistor")
      (fields (field (name "Comment") "Res3") (field (name "PUBLISHER") "Altium Limited"))
      (libsource (lib "Miscellaneous Devices") (part "Res3"))
    )
    (comp (ref "R44")
      (value "750")
      (footprint "RESC2012M")
      (description "Resistor")
      (fields (field (name "Comment") "Res3") (field (name "PUBLISHER") "Altium Limited"))
      (libsource (lib "Miscellaneous Devices") (part "Res3"))
    )
    (comp (ref "R45")
      (value "750")
      (footprint "RESC2012M")
      (description "Resistor")
      (fields (field (name "Comment") "Res3") (field (name "PUBLISHER") "Altium Limited"))
      (libsource (lib "Miscellaneous Devices") (part "Res3"))
    )
    (comp (ref "R46")
      (value "750")
      (footprint "RESC2012M")
      (description "Resistor")
      (fields (field (name "Comment") "Res3") (field (name "PUBLISHER") "Altium Limited"))
      (libsource (lib "Miscellaneous Devices") (part "Res3"))
    )
    (comp (ref "R47")
      (value "750")
      (footprint "RESC2012M")
      (description "Resistor")
      (fields (field (name "Comment") "Res3") (field (name "PUBLISHER") "Altium Limited"))
      (libsource (lib "Miscellaneous Devices") (part "Res3"))
    )
    (comp (ref "R48")
      (value "750")
      (footprint "RESC2012M")
      (description "Resistor")
      (fields (field (name "Comment") "Res3") (field (name "PUBLISHER") "Altium Limited"))
      (libsource (lib "Miscellaneous Devices") (part "Res3"))
    )
    (comp (ref "U1")
      (value "MAX3094, Rx")
      (footprint "NSO16_N")
      (description "Differential Line Receivers")
      (libsource (lib "HH_chips") (part "MAX3094"))
    )
    (comp (ref "U2")
      (value "MAX3094, Rx")
      (footprint "NSO16_N")
      (description "Differential Line Receivers")
      (libsource (lib "HH_chips") (part "MAX3094"))
    )
    (comp (ref "U3")
      (value "MAX3030, Tx")
      (footprint "NSO16_N")
      (description "Differential Line Transmitter")
      (libsource (lib "HH_chips") (part "MAX3030"))
    )
    (comp (ref "U4")
      (value "MAX3030, Tx")
      (footprint "NSO16_N")
      (description "Differential Line Transmitter")
      (libsource (lib "HH_chips") (part "MAX3030"))
    )
    (comp (ref "U5")
      (value "MAX3030, Tx")
      (footprint "NSO16_N")
      (description "Differential Line Transmitter")
      (libsource (lib "HH_chips") (part "MAX3030"))
    )
    (comp (ref "U6")
      (value "MAX3030, Tx")
      (footprint "NSO16_N")
      (description "Differential Line Transmitter")
      (libsource (lib "HH_chips") (part "MAX3030"))
    )
    (comp (ref "U7")
      (value "MAX3030, Tx")
      (footprint "NSO16_N")
      (description "Differential Line Transmitter")
      (libsource (lib "HH_chips") (part "MAX3030"))
    )
    (comp (ref "U8")
      (value "MAX3030, Tx")
      (footprint "NSO16_N")
      (description "Differential Line Transmitter")
      (libsource (lib "HH_chips") (part "MAX3030"))
    )
    (comp (ref "U9")
      (value "MAX3030, Tx")
      (footprint "NSO16_N")
      (description "Differential Line Transmitter")
      (libsource (lib "HH_chips") (part "MAX3030"))
    )
    (comp (ref "U10")
      (value "MAX3030, Tx")
      (footprint "NSO16_N")
      (description "Differential Line Transmitter")
      (libsource (lib "HH_chips") (part "MAX3030"))
    )
    (comp (ref "U11")
      (value "ZEM4310")
      (footprint "ZEM4310")
      (description "ZEM4310 breakout module")
      (libsource (lib "HH_chips") (part "ZEM4310"))
    )
    (comp (ref "U12")
      (value "SN74LVC1T45")
      (footprint "SOT23-6")
      (description "Logic Translator (Bidirectional)")
      (libsource (lib "HH_chips") (part "SN74LVC1T45"))
    )
    (comp (ref "U13")
      (value "SN74LVC1T45")
      (footprint "SOT23-6")
      (description "Logic Translator (Bidirectional)")
      (libsource (lib "HH_chips") (part "SN74LVC1T45"))
    )
    (comp (ref "U14")
      (value "SN74LVC1T45")
      (footprint "SOT23-6")
      (description "Logic Translator (Bidirectional)")
      (libsource (lib "HH_chips") (part "SN74LVC1T45"))
    )
    (comp (ref "U15")
      (value "SN74LVC1T45")
      (footprint "SOT23-6")
      (description "Logic Translator (Bidirectional)")
      (libsource (lib "HH_chips") (part "SN74LVC1T45"))
    )
  )
  (nets
    (net (code "1") (name "/AUX_CLK_IN") (class "Default")
      (node (ref "P7") (pin "11") (pinfunction "11_11") (pintype "passive"))
      (node (ref "U11") (pin "1A11") (pinfunction "G1/CLKIN_1A11") (pintype "passive"))
      (node (ref "U12") (pin "4") (pinfunction "B_4") (pintype "passive"))
    )
    (net (code "2") (name "/AUX_IN_1") (class "Default")
      (node (ref "P9") (pin "32") (pinfunction "32_32") (pintype "passive"))
      (node (ref "U11") (pin "1C20") (pinfunction "P17/R30p_1C20") (pintype "passive"))
      (node (ref "U15") (pin "4") (pinfunction "B_4") (pintype "passive"))
    )
    (net (code "3") (name "/AUX_IO_0") (class "Default")
      (node (ref "P6") (pin "2") (pinfunction "2_2") (pintype "passive"))
      (node (ref "P8") (pin "38") (pinfunction "38_38") (pintype "passive"))
      (node (ref "U11") (pin "2C3") (pinfunction "H21/R14p_2C3") (pintype "passive"))
    )
    (net (code "4") (name "/AUX_IO_1") (class "Default")
      (node (ref "P6") (pin "3") (pinfunction "3_3") (pintype "passive"))
      (node (ref "P8") (pin "37") (pinfunction "37_37") (pintype "passive"))
      (node (ref "U11") (pin "2C4") (pinfunction "W17/B38p_2C4") (pintype "passive"))
    )
    (net (code "5") (name "/AUX_IO_2") (class "Default")
      (node (ref "P6") (pin "4") (pinfunction "4_4") (pintype "passive"))
      (node (ref "P8") (pin "34") (pinfunction "34_34") (pintype "passive"))
      (node (ref "U11") (pin "2C5") (pinfunction "H22/R14n_2C5") (pintype "passive"))
    )
    (net (code "6") (name "/AUX_IO_3") (class "Default")
      (node (ref "P6") (pin "5") (pinfunction "5_5") (pintype "passive"))
      (node (ref "P8") (pin "33") (pinfunction "33_33") (pintype "passive"))
      (node (ref "U11") (pin "2C6") (pinfunction "Y17/B38n_2C6") (pintype "passive"))
    )
    (net (code "7") (name "/AUX_IO_4") (class "Default")
      (node (ref "P6") (pin "6") (pinfunction "6_6") (pintype "passive"))
      (node (ref "P8") (pin "32") (pinfunction "32_32") (pintype "passive"))
      (node (ref "U11") (pin "2C7") (pinfunction "E21/R8p_2C7") (pintype "passive"))
    )
    (net (code "8") (name "/AUX_IO_5") (class "Default")
      (node (ref "P6") (pin "7") (pinfunction "7_7") (pintype "passive"))
      (node (ref "P8") (pin "31") (pinfunction "31_31") (pintype "passive"))
      (node (ref "U11") (pin "2C8") (pinfunction "P21/R23p_2C8") (pintype "passive"))
    )
    (net (code "9") (name "/AUX_IO_6") (class "Default")
      (node (ref "P6") (pin "8") (pinfunction "8_8") (pintype "passive"))
      (node (ref "P8") (pin "30") (pinfunction "30_30") (pintype "passive"))
      (node (ref "U11") (pin "2C9") (pinfunction "E22/R8n_2C9") (pintype "passive"))
    )
    (net (code "10") (name "/AUX_IO_7") (class "Default")
      (node (ref "P6") (pin "9") (pinfunction "9_9") (pintype "passive"))
      (node (ref "P8") (pin "29") (pinfunction "29_29") (pintype "passive"))
      (node (ref "U11") (pin "2C10") (pinfunction "P22/R23n_2C10") (pintype "passive"))
    )
    (net (code "11") (name "/AUX_IO_8") (class "Default")
      (node (ref "P6") (pin "10") (pinfunction "10_10") (pintype "passive"))
      (node (ref "P8") (pin "28") (pinfunction "28_28") (pintype "passive"))
      (node (ref "U11") (pin "2C11") (pinfunction "F19/R6p_2C11") (pintype "passive"))
    )
    (net (code "12") (name "/AUX_IO_9") (class "Default")
      (node (ref "P6") (pin "11") (pinfunction "11_11") (pintype "passive"))
      (node (ref "P8") (pin "27") (pinfunction "27_27") (pintype "passive"))
      (node (ref "U11") (pin "2C12") (pinfunction "U16/B40p_2C12") (pintype "passive"))
    )
    (net (code "13") (name "/AUX_IO_10") (class "Default")
      (node (ref "P6") (pin "12") (pinfunction "12_12") (pintype "passive"))
      (node (ref "P8") (pin "26") (pinfunction "26_26") (pintype "passive"))
      (node (ref "U11") (pin "2C13") (pinfunction "F20/R6n_2C13") (pintype "passive"))
    )
    (net (code "14") (name "/AUX_IO_11") (class "Default")
      (node (ref "P6") (pin "13") (pinfunction "13_13") (pintype "passive"))
      (node (ref "P8") (pin "25") (pinfunction "25_25") (pintype "passive"))
      (node (ref "U11") (pin "2C14") (pinfunction "U17/B40n_2C14") (pintype "passive"))
    )
    (net (code "15") (name "/AUX_IO_12") (class "Default")
      (node (ref "P6") (pin "14") (pinfunction "14_14") (pintype "passive"))
      (node (ref "P8") (pin "24") (pinfunction "24_24") (pintype "passive"))
      (node (ref "U11") (pin "2C15") (pinfunction "D21/R7p_2C15") (pintype "passive"))
    )
    (net (code "16") (name "/AUX_IO_13") (class "Default")
      (node (ref "P6") (pin "15") (pinfunction "15_15") (pintype "passive"))
      (node (ref "P8") (pin "23") (pinfunction "23_23") (pintype "passive"))
      (node (ref "U11") (pin "2C16") (pinfunction "T14/B36p_2C16") (pintype "passive"))
    )
    (net (code "17") (name "/AUX_IO_14") (class "Default")
      (node (ref "P6") (pin "16") (pinfunction "16_16") (pintype "passive"))
      (node (ref "P8") (pin "22") (pinfunction "22_22") (pintype "passive"))
      (node (ref "U11") (pin "2C17") (pinfunction "D22/R7n_2C17") (pintype "passive"))
    )
    (net (code "18") (name "/AUX_IO_15") (class "Default")
      (node (ref "P6") (pin "17") (pinfunction "17_17") (pintype "passive"))
      (node (ref "P8") (pin "21") (pinfunction "21_21") (pintype "passive"))
      (node (ref "U11") (pin "2C18") (pinfunction "T15/B36n_2C18") (pintype "passive"))
    )
    (net (code "19") (name "/AUX_IO_16") (class "Default")
      (node (ref "P6") (pin "18") (pinfunction "18_18") (pintype "passive"))
      (node (ref "P8") (pin "20") (pinfunction "20_20") (pintype "passive"))
      (node (ref "U11") (pin "2C19") (pinfunction "C21/R4p_2C19") (pintype "passive"))
    )
    (net (code "20") (name "/AUX_IO_17") (class "Default")
      (node (ref "P6") (pin "19") (pinfunction "19_19") (pintype "passive"))
      (node (ref "P8") (pin "19") (pinfunction "19_19") (pintype "passive"))
      (node (ref "U11") (pin "2C20") (pinfunction "N19/R22p_2C20") (pintype "passive"))
    )
    (net (code "21") (name "/LED_0") (class "Default")
      (node (ref "D1") (pin "1") (pinfunction "A_1") (pintype "passive"))
      (node (ref "U11") (pin "1C4") (pinfunction "AA9/B18p_1C4") (pintype "passive"))
    )
    (net (code "22") (name "/LED_1") (class "Default")
      (node (ref "D3") (pin "1") (pinfunction "A_1") (pintype "passive"))
      (node (ref "U11") (pin "1C5") (pinfunction "R3/L27n_1C5") (pintype "passive"))
    )
    (net (code "23") (name "/LED_2") (class "Default")
      (node (ref "D5") (pin "1") (pinfunction "A_1") (pintype "passive"))
      (node (ref "U11") (pin "1C6") (pinfunction "AB9/B19n_1C6") (pintype "passive"))
    )
    (net (code "24") (name "/LED_3") (class "Default")
      (node (ref "D7") (pin "1") (pinfunction "A_1") (pintype "passive"))
      (node (ref "U11") (pin "1C7") (pinfunction "W2/L28p_1C7") (pintype "passive"))
    )
    (net (code "25") (name "/LED_4") (class "Default")
      (node (ref "D2") (pin "1") (pinfunction "A_1") (pintype "passive"))
      (node (ref "U11") (pin "1C8") (pinfunction "W10/B20p_1C8") (pintype "passive"))
    )
    (net (code "26") (name "/LED_5") (class "Default")
      (node (ref "D4") (pin "1") (pinfunction "A_1") (pintype "passive"))
      (node (ref "U11") (pin "1C9") (pinfunction "W1/L28n_1C9") (pintype "passive"))
    )
    (net (code "27") (name "/LED_6") (class "Default")
      (node (ref "D6") (pin "1") (pinfunction "A_1") (pintype "passive"))
      (node (ref "U11") (pin "1C10") (pinfunction "Y10/B20n_1C10") (pintype "passive"))
    )
    (net (code "28") (name "/LED_7") (class "Default")
      (node (ref "D8") (pin "1") (pinfunction "A_1") (pintype "passive"))
      (node (ref "U11") (pin "1C11") (pinfunction "Y2/L29p_1C11") (pintype "passive"))
    )
    (net (code "29") (name "/PMT_IN") (class "Default")
      (node (ref "P9") (pin "36") (pinfunction "36_36") (pintype "passive"))
      (node (ref "U11") (pin "1C16") (pinfunction "AA10/B21p_1C16") (pintype "passive"))
      (node (ref "U13") (pin "4") (pinfunction "B_4") (pintype "passive"))
    )
    (net (code "30") (name "/TRIGGER_IN") (class "Default")
      (node (ref "P9") (pin "34") (pinfunction "34_34") (pintype "passive"))
      (node (ref "U11") (pin "1C18") (pinfunction "AB10/B21n_1C18") (pintype "passive"))
      (node (ref "U14") (pin "4") (pinfunction "B_4") (pintype "passive"))
    )
    (net (code "31") (name "/TTL_OUT_0") (class "Default")
      (node (ref "P5") (pin "2") (pinfunction "2_2") (pintype "passive"))
      (node (ref "U11") (pin "2B3") (pinfunction "H17/R5p_2B3") (pintype "passive"))
    )
    (net (code "32") (name "/TTL_OUT_1") (class "Default")
      (node (ref "P5") (pin "3") (pinfunction "3_3") (pintype "passive"))
      (node (ref "U11") (pin "2B4") (pinfunction "AA14/B25p_2B4") (pintype "passive"))
    )
    (net (code "33") (name "/TTL_OUT_2") (class "Default")
      (node (ref "P10") (pin "36") (pinfunction "36_36") (pintype "passive"))
      (node (ref "P5") (pin "4") (pinfunction "4_4") (pintype "passive"))
      (node (ref "U11") (pin "2B5") (pinfunction "G18/R5n_2B5") (pintype "passive"))
    )
    (net (code "34") (name "/TTL_OUT_3") (class "Default")
      (node (ref "P10") (pin "35") (pinfunction "35_35") (pintype "passive"))
      (node (ref "P5") (pin "5") (pinfunction "5_5") (pintype "passive"))
      (node (ref "U11") (pin "2B6") (pinfunction "AB14/B25n_2B6") (pintype "passive"))
    )
    (net (code "35") (name "/TTL_OUT_4") (class "Default")
      (node (ref "P10") (pin "34") (pinfunction "34_34") (pintype "passive"))
      (node (ref "P5") (pin "6") (pinfunction "6_6") (pintype "passive"))
      (node (ref "U11") (pin "2B7") (pinfunction "K18/R13p_2B7") (pintype "passive"))
    )
    (net (code "36") (name "/TTL_OUT_5") (class "Default")
      (node (ref "P10") (pin "33") (pinfunction "33_33") (pintype "passive"))
      (node (ref "P5") (pin "7") (pinfunction "7_7") (pintype "passive"))
      (node (ref "U11") (pin "2B8") (pinfunction "W13/B26p_2B8") (pintype "passive"))
    )
    (net (code "37") (name "/TTL_OUT_6") (class "Default")
      (node (ref "P10") (pin "32") (pinfunction "32_32") (pintype "passive"))
      (node (ref "P5") (pin "8") (pinfunction "8_8") (pintype "passive"))
      (node (ref "U11") (pin "2B9") (pinfunction "K17/R13n_2B9") (pintype "passive"))
    )
    (net (code "38") (name "/TTL_OUT_7") (class "Default")
      (node (ref "P10") (pin "31") (pinfunction "31_31") (pintype "passive"))
      (node (ref "P5") (pin "9") (pinfunction "9_9") (pintype "passive"))
      (node (ref "U11") (pin "2B10") (pinfunction "Y13/B26n_2B10") (pintype "passive"))
    )
    (net (code "39") (name "/TTL_OUT_8") (class "Default")
      (node (ref "P10") (pin "30") (pinfunction "30_30") (pintype "passive"))
      (node (ref "P5") (pin "10") (pinfunction "10_10") (pintype "passive"))
      (node (ref "U11") (pin "2B11") (pinfunction "M19/R18p_2B11") (pintype "passive"))
    )
    (net (code "40") (name "/TTL_OUT_9") (class "Default")
      (node (ref "P10") (pin "29") (pinfunction "29_29") (pintype "passive"))
      (node (ref "P5") (pin "11") (pinfunction "11_11") (pintype "passive"))
      (node (ref "U11") (pin "2B12") (pinfunction "AA15/B27p_2B12") (pintype "passive"))
    )
    (net (code "41") (name "/TTL_OUT_10") (class "Default")
      (node (ref "P10") (pin "28") (pinfunction "28_28") (pintype "passive"))
      (node (ref "P5") (pin "12") (pinfunction "12_12") (pintype "passive"))
      (node (ref "U11") (pin "2B13") (pinfunction "M20/R18n_2B13") (pintype "passive"))
    )
    (net (code "42") (name "/TTL_OUT_11") (class "Default")
      (node (ref "P10") (pin "27") (pinfunction "27_27") (pintype "passive"))
      (node (ref "P5") (pin "13") (pinfunction "13_13") (pintype "passive"))
      (node (ref "U11") (pin "2B14") (pinfunction "AB15/B27n_2B14") (pintype "passive"))
    )
    (net (code "43") (name "/TTL_OUT_12") (class "Default")
      (node (ref "P10") (pin "26") (pinfunction "26_26") (pintype "passive"))
      (node (ref "P5") (pin "14") (pinfunction "14_14") (pintype "passive"))
      (node (ref "U11") (pin "2B15") (pinfunction "N21/R20p_2B15") (pintype "passive"))
    )
    (net (code "44") (name "/TTL_OUT_13") (class "Default")
      (node (ref "P10") (pin "25") (pinfunction "25_25") (pintype "passive"))
      (node (ref "P5") (pin "15") (pinfunction "15_15") (pintype "passive"))
      (node (ref "U11") (pin "2B16") (pinfunction "AA16/B30p_2B16") (pintype "passive"))
    )
    (net (code "45") (name "/TTL_OUT_14") (class "Default")
      (node (ref "P10") (pin "24") (pinfunction "24_24") (pintype "passive"))
      (node (ref "P5") (pin "16") (pinfunction "16_16") (pintype "passive"))
      (node (ref "U11") (pin "2B17") (pinfunction "N22/R20n_2B17") (pintype "passive"))
    )
    (net (code "46") (name "/TTL_OUT_15") (class "Default")
      (node (ref "P10") (pin "23") (pinfunction "23_23") (pintype "passive"))
      (node (ref "P5") (pin "17") (pinfunction "17_17") (pintype "passive"))
      (node (ref "U11") (pin "2B18") (pinfunction "AB16/B30n_2B18") (pintype "passive"))
    )
    (net (code "47") (name "/TTL_OUT_16") (class "Default")
      (node (ref "P10") (pin "22") (pinfunction "22_22") (pintype "passive"))
      (node (ref "P5") (pin "18") (pinfunction "18_18") (pintype "passive"))
      (node (ref "U11") (pin "2B19") (pinfunction "H19/R9p_2B19") (pintype "passive"))
    )
    (net (code "48") (name "/TTL_OUT_17") (class "Default")
      (node (ref "P10") (pin "21") (pinfunction "21_21") (pintype "passive"))
      (node (ref "P5") (pin "19") (pinfunction "19_19") (pintype "passive"))
      (node (ref "U11") (pin "2B20") (pinfunction "AA17/B37p_2B20") (pintype "passive"))
    )
    (net (code "49") (name "/TTL_OUT_18") (class "Default")
      (node (ref "P10") (pin "20") (pinfunction "20_20") (pintype "passive"))
      (node (ref "P5") (pin "20") (pinfunction "20_20") (pintype "passive"))
      (node (ref "U11") (pin "2B21") (pinfunction "H20/R9n_2B21") (pintype "passive"))
    )
    (net (code "50") (name "/TTL_OUT_19") (class "Default")
      (node (ref "P10") (pin "19") (pinfunction "19_19") (pintype "passive"))
      (node (ref "P5") (pin "21") (pinfunction "21_21") (pintype "passive"))
      (node (ref "U11") (pin "2B22") (pinfunction "AB17/B37n_2B22") (pintype "passive"))
    )
    (net (code "51") (name "/TTL_OUT_20") (class "Default")
      (node (ref "P10") (pin "18") (pinfunction "18_18") (pintype "passive"))
      (node (ref "P5") (pin "22") (pinfunction "22_22") (pintype "passive"))
      (node (ref "U11") (pin "2B23") (pinfunction "M21/R19p_2B23") (pintype "passive"))
    )
    (net (code "52") (name "/TTL_OUT_21") (class "Default")
      (node (ref "P10") (pin "17") (pinfunction "17_17") (pintype "passive"))
      (node (ref "P5") (pin "23") (pinfunction "23_23") (pintype "passive"))
      (node (ref "U11") (pin "2B24") (pinfunction "AA20/B39p_2B24") (pintype "passive"))
    )
    (net (code "53") (name "/TTL_OUT_22") (class "Default")
      (node (ref "P10") (pin "14") (pinfunction "14_14") (pintype "passive"))
      (node (ref "P5") (pin "24") (pinfunction "24_24") (pintype "passive"))
      (node (ref "U11") (pin "2B25") (pinfunction "M22/R19n_2B25") (pintype "passive"))
    )
    (net (code "54") (name "/TTL_OUT_23") (class "Default")
      (node (ref "P10") (pin "13") (pinfunction "13_13") (pintype "passive"))
      (node (ref "P5") (pin "25") (pinfunction "25_25") (pintype "passive"))
      (node (ref "U11") (pin "2B26") (pinfunction "AB20/B39n_2B26") (pintype "passive"))
    )
    (net (code "55") (name "/TTL_OUT_24") (class "Default")
      (node (ref "P10") (pin "12") (pinfunction "12_12") (pintype "passive"))
      (node (ref "P5") (pin "26") (pinfunction "26_26") (pintype "passive"))
      (node (ref "U11") (pin "2B27") (pinfunction "J21/R15p_2B27") (pintype "passive"))
    )
    (net (code "56") (name "/TTL_OUT_25") (class "Default")
      (node (ref "P10") (pin "11") (pinfunction "11_11") (pintype "passive"))
      (node (ref "P5") (pin "27") (pinfunction "27_27") (pintype "passive"))
      (node (ref "U11") (pin "2B28") (pinfunction "Y14/B29p_2B28") (pintype "passive"))
    )
    (net (code "57") (name "/TTL_OUT_26") (class "Default")
      (node (ref "P10") (pin "10") (pinfunction "10_10") (pintype "passive"))
      (node (ref "P5") (pin "28") (pinfunction "28_28") (pintype "passive"))
      (node (ref "U11") (pin "2B29") (pinfunction "J22/R15n_2B29") (pintype "passive"))
    )
    (net (code "58") (name "/TTL_OUT_27") (class "Default")
      (node (ref "P10") (pin "9") (pinfunction "9_9") (pintype "passive"))
      (node (ref "P5") (pin "29") (pinfunction "29_29") (pintype "passive"))
      (node (ref "U11") (pin "2B30") (pinfunction "Y15/B29n_2B30") (pintype "passive"))
    )
    (net (code "59") (name "/TTL_OUT_28") (class "Default")
      (node (ref "P10") (pin "8") (pinfunction "8_8") (pintype "passive"))
      (node (ref "P5") (pin "30") (pinfunction "30_30") (pintype "passive"))
      (node (ref "U11") (pin "2B31") (pinfunction "R21/R24p_2B31") (pintype "passive"))
    )
    (net (code "60") (name "/TTL_OUT_29") (class "Default")
      (node (ref "P10") (pin "7") (pinfunction "7_7") (pintype "passive"))
      (node (ref "P5") (pin "31") (pinfunction "31_31") (pintype "passive"))
      (node (ref "U11") (pin "2B32") (pinfunction "L21/R17p_2B32") (pintype "passive"))
    )
    (net (code "61") (name "/TTL_OUT_30") (class "Default")
      (node (ref "P10") (pin "6") (pinfunction "6_6") (pintype "passive"))
      (node (ref "P5") (pin "32") (pinfunction "32_32") (pintype "passive"))
      (node (ref "U11") (pin "2B33") (pinfunction "R22/R24n_2B33") (pintype "passive"))
    )
    (net (code "62") (name "/TTL_OUT_31") (class "Default")
      (node (ref "P10") (pin "5") (pinfunction "5_5") (pintype "passive"))
      (node (ref "P5") (pin "33") (pinfunction "33_33") (pintype "passive"))
      (node (ref "U11") (pin "2B34") (pinfunction "L22/R17n_2B34") (pintype "passive"))
    )
    (net (code "63") (name "/TTL_OUT_32") (class "Default")
      (node (ref "P10") (pin "4") (pinfunction "4_4") (pintype "passive"))
      (node (ref "P5") (pin "34") (pinfunction "34_34") (pintype "passive"))
      (node (ref "U11") (pin "2B35") (pinfunction "F21/R11p_2B35") (pintype "passive"))
    )
    (net (code "64") (name "/TTL_OUT_33") (class "Default")
      (node (ref "P10") (pin "3") (pinfunction "3_3") (pintype "passive"))
      (node (ref "P5") (pin "35") (pinfunction "35_35") (pintype "passive"))
      (node (ref "U11") (pin "2B36") (pinfunction "V14/B33p_2B36") (pintype "passive"))
    )
    (net (code "65") (name "/TTL_OUT_34") (class "Default")
      (node (ref "P10") (pin "2") (pinfunction "2_2") (pintype "passive"))
      (node (ref "P5") (pin "36") (pinfunction "36_36") (pintype "passive"))
      (node (ref "U11") (pin "2B37") (pinfunction "F22/R11n_2B37") (pintype "passive"))
    )
    (net (code "66") (name "/TTL_OUT_35") (class "Default")
      (node (ref "P10") (pin "1") (pinfunction "1_1") (pintype "passive"))
      (node (ref "P5") (pin "37") (pinfunction "37_37") (pintype "passive"))
      (node (ref "U11") (pin "2B38") (pinfunction "U14/B33n_2B38") (pintype "passive"))
    )
    (net (code "67") (name "/bus0") (class "Default")
      (node (ref "P9") (pin "24") (pinfunction "24_24") (pintype "passive"))
      (node (ref "U10") (pin "9") (pinfunction "DI3_9") (pintype "passive"))
      (node (ref "U11") (pin "1B29") (pinfunction "U1/L24n_1B29") (pintype "passive"))
    )
    (net (code "68") (name "/bus0_n") (class "Default")
      (node (ref "J1") (pin "52") (pinfunction "A52_52") (pintype "passive"))
      (node (ref "J10") (pin "52") (pinfunction "A52_52") (pintype "passive"))
      (node (ref "J11") (pin "52") (pinfunction "A52_52") (pintype "passive"))
      (node (ref "J12") (pin "52") (pinfunction "A52_52") (pintype "passive"))
      (node (ref "J13") (pin "52") (pinfunction "A52_52") (pintype "passive"))
      (node (ref "J14") (pin "52") (pinfunction "A52_52") (pintype "passive"))
      (node (ref "J15") (pin "52") (pinfunction "A52_52") (pintype "passive"))
      (node (ref "J16") (pin "52") (pinfunction "A52_52") (pintype "passive"))
      (node (ref "J2") (pin "52") (pinfunction "A52_52") (pintype "passive"))
      (node (ref "J3") (pin "52") (pinfunction "A52_52") (pintype "passive"))
      (node (ref "J4") (pin "52") (pinfunction "A52_52") (pintype "passive"))
      (node (ref "J5") (pin "52") (pinfunction "A52_52") (pintype "passive"))
      (node (ref "J6") (pin "52") (pinfunction "A52_52") (pintype "passive"))
      (node (ref "J7") (pin "52") (pinfunction "A52_52") (pintype "passive"))
      (node (ref "J8") (pin "52") (pinfunction "A52_52") (pintype "passive"))
      (node (ref "J9") (pin "52") (pinfunction "A52_52") (pintype "passive"))
      (node (ref "R1") (pin "1") (pinfunction "1_1") (pintype "passive"))
      (node (ref "U10") (pin "10") (pinfunction "DO3+_10") (pintype "passive"))
    )
    (net (code "69") (name "/bus0_p") (class "Default")
      (node (ref "J1") (pin "51") (pinfunction "A51_51") (pintype "passive"))
      (node (ref "J10") (pin "51") (pinfunction "A51_51") (pintype "passive"))
      (node (ref "J11") (pin "51") (pinfunction "A51_51") (pintype "passive"))
      (node (ref "J12") (pin "51") (pinfunction "A51_51") (pintype "passive"))
      (node (ref "J13") (pin "51") (pinfunction "A51_51") (pintype "passive"))
      (node (ref "J14") (pin "51") (pinfunction "A51_51") (pintype "passive"))
      (node (ref "J15") (pin "51") (pinfunction "A51_51") (pintype "passive"))
      (node (ref "J16") (pin "51") (pinfunction "A51_51") (pintype "passive"))
      (node (ref "J2") (pin "51") (pinfunction "A51_51") (pintype "passive"))
      (node (ref "J3") (pin "51") (pinfunction "A51_51") (pintype "passive"))
      (node (ref "J4") (pin "51") (pinfunction "A51_51") (pintype "passive"))
      (node (ref "J5") (pin "51") (pinfunction "A51_51") (pintype "passive"))
      (node (ref "J6") (pin "51") (pinfunction "A51_51") (pintype "passive"))
      (node (ref "J7") (pin "51") (pinfunction "A51_51") (pintype "passive"))
      (node (ref "J8") (pin "51") (pinfunction "A51_51") (pintype "passive"))
      (node (ref "J9") (pin "51") (pinfunction "A51_51") (pintype "passive"))
      (node (ref "R1") (pin "2") (pinfunction "2_2") (pintype "passive"))
      (node (ref "U10") (pin "11") (pinfunction "DO3-_11") (pintype "passive"))
    )
    (net (code "70") (name "/bus1") (class "Default")
      (node (ref "P9") (pin "23") (pinfunction "23_23") (pintype "passive"))
      (node (ref "U10") (pin "15") (pinfunction "DI4_15") (pintype "passive"))
      (node (ref "U11") (pin "1B28") (pinfunction "AA8/B17p_1B28") (pintype "passive"))
    )
    (net (code "71") (name "/bus1_n") (class "Default")
      (node (ref "J1") (pin "49") (pinfunction "A49_49") (pintype "passive"))
      (node (ref "J10") (pin "49") (pinfunction "A49_49") (pintype "passive"))
      (node (ref "J11") (pin "49") (pinfunction "A49_49") (pintype "passive"))
      (node (ref "J12") (pin "49") (pinfunction "A49_49") (pintype "passive"))
      (node (ref "J13") (pin "49") (pinfunction "A49_49") (pintype "passive"))
      (node (ref "J14") (pin "49") (pinfunction "A49_49") (pintype "passive"))
      (node (ref "J15") (pin "49") (pinfunction "A49_49") (pintype "passive"))
      (node (ref "J16") (pin "49") (pinfunction "A49_49") (pintype "passive"))
      (node (ref "J2") (pin "49") (pinfunction "A49_49") (pintype "passive"))
      (node (ref "J3") (pin "49") (pinfunction "A49_49") (pintype "passive"))
      (node (ref "J4") (pin "49") (pinfunction "A49_49") (pintype "passive"))
      (node (ref "J5") (pin "49") (pinfunction "A49_49") (pintype "passive"))
      (node (ref "J6") (pin "49") (pinfunction "A49_49") (pintype "passive"))
      (node (ref "J7") (pin "49") (pinfunction "A49_49") (pintype "passive"))
      (node (ref "J8") (pin "49") (pinfunction "A49_49") (pintype "passive"))
      (node (ref "J9") (pin "49") (pinfunction "A49_49") (pintype "passive"))
      (node (ref "R2") (pin "1") (pinfunction "1_1") (pintype "passive"))
      (node (ref "U10") (pin "14") (pinfunction "DO4+_14") (pintype "passive"))
    )
    (net (code "72") (name "/bus1_p") (class "Default")
      (node (ref "J1") (pin "50") (pinfunction "A50_50") (pintype "passive"))
      (node (ref "J10") (pin "50") (pinfunction "A50_50") (pintype "passive"))
      (node (ref "J11") (pin "50") (pinfunction "A50_50") (pintype "passive"))
      (node (ref "J12") (pin "50") (pinfunction "A50_50") (pintype "passive"))
      (node (ref "J13") (pin "50") (pinfunction "A50_50") (pintype "passive"))
      (node (ref "J14") (pin "50") (pinfunction "A50_50") (pintype "passive"))
      (node (ref "J15") (pin "50") (pinfunction "A50_50") (pintype "passive"))
      (node (ref "J16") (pin "50") (pinfunction "A50_50") (pintype "passive"))
      (node (ref "J2") (pin "50") (pinfunction "A50_50") (pintype "passive"))
      (node (ref "J3") (pin "50") (pinfunction "A50_50") (pintype "passive"))
      (node (ref "J4") (pin "50") (pinfunction "A50_50") (pintype "passive"))
      (node (ref "J5") (pin "50") (pinfunction "A50_50") (pintype "passive"))
      (node (ref "J6") (pin "50") (pinfunction "A50_50") (pintype "passive"))
      (node (ref "J7") (pin "50") (pinfunction "A50_50") (pintype "passive"))
      (node (ref "J8") (pin "50") (pinfunction "A50_50") (pintype "passive"))
      (node (ref "J9") (pin "50") (pinfunction "A50_50") (pintype "passive"))
      (node (ref "R2") (pin "2") (pinfunction "2_2") (pintype "passive"))
      (node (ref "U10") (pin "13") (pinfunction "DO4-_13") (pintype "passive"))
    )
    (net (code "73") (name "/bus2") (class "Default")
      (node (ref "P9") (pin "26") (pinfunction "26_26") (pintype "passive"))
      (node (ref "U10") (pin "1") (pinfunction "DI1_1") (pintype "passive"))
      (node (ref "U11") (pin "1B31") (pinfunction "R19/R26p_1B31") (pintype "passive"))
    )
    (net (code "74") (name "/bus2_n") (class "Default")
      (node (ref "J1") (pin "56") (pinfunction "A56_56") (pintype "passive"))
      (node (ref "J10") (pin "56") (pinfunction "A56_56") (pintype "passive"))
      (node (ref "J11") (pin "56") (pinfunction "A56_56") (pintype "passive"))
      (node (ref "J12") (pin "56") (pinfunction "A56_56") (pintype "passive"))
      (node (ref "J13") (pin "56") (pinfunction "A56_56") (pintype "passive"))
      (node (ref "J14") (pin "56") (pinfunction "A56_56") (pintype "passive"))
      (node (ref "J15") (pin "56") (pinfunction "A56_56") (pintype "passive"))
      (node (ref "J16") (pin "56") (pinfunction "A56_56") (pintype "passive"))
      (node (ref "J2") (pin "56") (pinfunction "A56_56") (pintype "passive"))
      (node (ref "J3") (pin "56") (pinfunction "A56_56") (pintype "passive"))
      (node (ref "J4") (pin "56") (pinfunction "A56_56") (pintype "passive"))
      (node (ref "J5") (pin "56") (pinfunction "A56_56") (pintype "passive"))
      (node (ref "J6") (pin "56") (pinfunction "A56_56") (pintype "passive"))
      (node (ref "J7") (pin "56") (pinfunction "A56_56") (pintype "passive"))
      (node (ref "J8") (pin "56") (pinfunction "A56_56") (pintype "passive"))
      (node (ref "J9") (pin "56") (pinfunction "A56_56") (pintype "passive"))
      (node (ref "R3") (pin "1") (pinfunction "1_1") (pintype "passive"))
      (node (ref "U10") (pin "2") (pinfunction "DO1+_2") (pintype "passive"))
    )
    (net (code "75") (name "/bus2_p") (class "Default")
      (node (ref "J1") (pin "55") (pinfunction "A55_55") (pintype "passive"))
      (node (ref "J10") (pin "55") (pinfunction "A55_55") (pintype "passive"))
      (node (ref "J11") (pin "55") (pinfunction "A55_55") (pintype "passive"))
      (node (ref "J12") (pin "55") (pinfunction "A55_55") (pintype "passive"))
      (node (ref "J13") (pin "55") (pinfunction "A55_55") (pintype "passive"))
      (node (ref "J14") (pin "55") (pinfunction "A55_55") (pintype "passive"))
      (node (ref "J15") (pin "55") (pinfunction "A55_55") (pintype "passive"))
      (node (ref "J16") (pin "55") (pinfunction "A55_55") (pintype "passive"))
      (node (ref "J2") (pin "55") (pinfunction "A55_55") (pintype "passive"))
      (node (ref "J3") (pin "55") (pinfunction "A55_55") (pintype "passive"))
      (node (ref "J4") (pin "55") (pinfunction "A55_55") (pintype "passive"))
      (node (ref "J5") (pin "55") (pinfunction "A55_55") (pintype "passive"))
      (node (ref "J6") (pin "55") (pinfunction "A55_55") (pintype "passive"))
      (node (ref "J7") (pin "55") (pinfunction "A55_55") (pintype "passive"))
      (node (ref "J8") (pin "55") (pinfunction "A55_55") (pintype "passive"))
      (node (ref "J9") (pin "55") (pinfunction "A55_55") (pintype "passive"))
      (node (ref "R3") (pin "2") (pinfunction "2_2") (pintype "passive"))
      (node (ref "U10") (pin "3") (pinfunction "DO1-_3") (pintype "passive"))
    )
    (net (code "76") (name "/bus3") (class "Default")
      (node (ref "P9") (pin "25") (pinfunction "25_25") (pintype "passive"))
      (node (ref "U10") (pin "7") (pinfunction "DI2_7") (pintype "passive"))
      (node (ref "U11") (pin "1B30") (pinfunction "AB8/B17n_1B30") (pintype "passive"))
    )
    (net (code "77") (name "/bus3_n") (class "Default")
      (node (ref "J1") (pin "53") (pinfunction "A53_53") (pintype "passive"))
      (node (ref "J10") (pin "53") (pinfunction "A53_53") (pintype "passive"))
      (node (ref "J11") (pin "53") (pinfunction "A53_53") (pintype "passive"))
      (node (ref "J12") (pin "53") (pinfunction "A53_53") (pintype "passive"))
      (node (ref "J13") (pin "53") (pinfunction "A53_53") (pintype "passive"))
      (node (ref "J14") (pin "53") (pinfunction "A53_53") (pintype "passive"))
      (node (ref "J15") (pin "53") (pinfunction "A53_53") (pintype "passive"))
      (node (ref "J16") (pin "53") (pinfunction "A53_53") (pintype "passive"))
      (node (ref "J2") (pin "53") (pinfunction "A53_53") (pintype "passive"))
      (node (ref "J3") (pin "53") (pinfunction "A53_53") (pintype "passive"))
      (node (ref "J4") (pin "53") (pinfunction "A53_53") (pintype "passive"))
      (node (ref "J5") (pin "53") (pinfunction "A53_53") (pintype "passive"))
      (node (ref "J6") (pin "53") (pinfunction "A53_53") (pintype "passive"))
      (node (ref "J7") (pin "53") (pinfunction "A53_53") (pintype "passive"))
      (node (ref "J8") (pin "53") (pinfunction "A53_53") (pintype "passive"))
      (node (ref "J9") (pin "53") (pinfunction "A53_53") (pintype "passive"))
      (node (ref "R4") (pin "1") (pinfunction "1_1") (pintype "passive"))
      (node (ref "U10") (pin "6") (pinfunction "DO2+_6") (pintype "passive"))
    )
    (net (code "78") (name "/bus3_p") (class "Default")
      (node (ref "J1") (pin "54") (pinfunction "A54_54") (pintype "passive"))
      (node (ref "J10") (pin "54") (pinfunction "A54_54") (pintype "passive"))
      (node (ref "J11") (pin "54") (pinfunction "A54_54") (pintype "passive"))
      (node (ref "J12") (pin "54") (pinfunction "A54_54") (pintype "passive"))
      (node (ref "J13") (pin "54") (pinfunction "A54_54") (pintype "passive"))
      (node (ref "J14") (pin "54") (pinfunction "A54_54") (pintype "passive"))
      (node (ref "J15") (pin "54") (pinfunction "A54_54") (pintype "passive"))
      (node (ref "J16") (pin "54") (pinfunction "A54_54") (pintype "passive"))
      (node (ref "J2") (pin "54") (pinfunction "A54_54") (pintype "passive"))
      (node (ref "J3") (pin "54") (pinfunction "A54_54") (pintype "passive"))
      (node (ref "J4") (pin "54") (pinfunction "A54_54") (pintype "passive"))
      (node (ref "J5") (pin "54") (pinfunction "A54_54") (pintype "passive"))
      (node (ref "J6") (pin "54") (pinfunction "A54_54") (pintype "passive"))
      (node (ref "J7") (pin "54") (pinfunction "A54_54") (pintype "passive"))
      (node (ref "J8") (pin "54") (pinfunction "A54_54") (pintype "passive"))
      (node (ref "J9") (pin "54") (pinfunction "A54_54") (pintype "passive"))
      (node (ref "R4") (pin "2") (pinfunction "2_2") (pintype "passive"))
      (node (ref "U10") (pin "5") (pinfunction "DO2-_5") (pintype "passive"))
    )
    (net (code "79") (name "/bus4") (class "Default")
      (node (ref "P9") (pin "20") (pinfunction "20_20") (pintype "passive"))
      (node (ref "U11") (pin "1B25") (pinfunction "P3/L23n_1B25") (pintype "passive"))
      (node (ref "U9") (pin "9") (pinfunction "DI3_9") (pintype "passive"))
    )
    (net (code "80") (name "/bus4_n") (class "Default")
      (node (ref "J1") (pin "43") (pinfunction "A43_43") (pintype "passive"))
      (node (ref "J10") (pin "43") (pinfunction "A43_43") (pintype "passive"))
      (node (ref "J11") (pin "43") (pinfunction "A43_43") (pintype "passive"))
      (node (ref "J12") (pin "43") (pinfunction "A43_43") (pintype "passive"))
      (node (ref "J13") (pin "43") (pinfunction "A43_43") (pintype "passive"))
      (node (ref "J14") (pin "43") (pinfunction "A43_43") (pintype "passive"))
      (node (ref "J15") (pin "43") (pinfunction "A43_43") (pintype "passive"))
      (node (ref "J16") (pin "43") (pinfunction "A43_43") (pintype "passive"))
      (node (ref "J2") (pin "43") (pinfunction "A43_43") (pintype "passive"))
      (node (ref "J3") (pin "43") (pinfunction "A43_43") (pintype "passive"))
      (node (ref "J4") (pin "43") (pinfunction "A43_43") (pintype "passive"))
      (node (ref "J5") (pin "43") (pinfunction "A43_43") (pintype "passive"))
      (node (ref "J6") (pin "43") (pinfunction "A43_43") (pintype "passive"))
      (node (ref "J7") (pin "43") (pinfunction "A43_43") (pintype "passive"))
      (node (ref "J8") (pin "43") (pinfunction "A43_43") (pintype "passive"))
      (node (ref "J9") (pin "43") (pinfunction "A43_43") (pintype "passive"))
      (node (ref "R5") (pin "1") (pinfunction "1_1") (pintype "passive"))
      (node (ref "U9") (pin "10") (pinfunction "DO3+_10") (pintype "passive"))
    )
    (net (code "81") (name "/bus4_p") (class "Default")
      (node (ref "J1") (pin "42") (pinfunction "A42_42") (pintype "passive"))
      (node (ref "J10") (pin "42") (pinfunction "A42_42") (pintype "passive"))
      (node (ref "J11") (pin "42") (pinfunction "A42_42") (pintype "passive"))
      (node (ref "J12") (pin "42") (pinfunction "A42_42") (pintype "passive"))
      (node (ref "J13") (pin "42") (pinfunction "A42_42") (pintype "passive"))
      (node (ref "J14") (pin "42") (pinfunction "A42_42") (pintype "passive"))
      (node (ref "J15") (pin "42") (pinfunction "A42_42") (pintype "passive"))
      (node (ref "J16") (pin "42") (pinfunction "A42_42") (pintype "passive"))
      (node (ref "J2") (pin "42") (pinfunction "A42_42") (pintype "passive"))
      (node (ref "J3") (pin "42") (pinfunction "A42_42") (pintype "passive"))
      (node (ref "J4") (pin "42") (pinfunction "A42_42") (pintype "passive"))
      (node (ref "J5") (pin "42") (pinfunction "A42_42") (pintype "passive"))
      (node (ref "J6") (pin "42") (pinfunction "A42_42") (pintype "passive"))
      (node (ref "J7") (pin "42") (pinfunction "A42_42") (pintype "passive"))
      (node (ref "J8") (pin "42") (pinfunction "A42_42") (pintype "passive"))
      (node (ref "J9") (pin "42") (pinfunction "A42_42") (pintype "passive"))
      (node (ref "R5") (pin "2") (pinfunction "2_2") (pintype "passive"))
      (node (ref "U9") (pin "11") (pinfunction "DO3-_11") (pintype "passive"))
    )
    (net (code "82") (name "/bus5") (class "Default")
      (node (ref "P9") (pin "19") (pinfunction "19_19") (pintype "passive"))
      (node (ref "U11") (pin "1B24") (pinfunction "AA7/B10p_1B24") (pintype "passive"))
      (node (ref "U9") (pin "15") (pinfunction "DI4_15") (pintype "passive"))
    )
    (net (code "83") (name "/bus5_n") (class "Default")
      (node (ref "J1") (pin "40") (pinfunction "A40_40") (pintype "passive"))
      (node (ref "J10") (pin "40") (pinfunction "A40_40") (pintype "passive"))
      (node (ref "J11") (pin "40") (pinfunction "A40_40") (pintype "passive"))
      (node (ref "J12") (pin "40") (pinfunction "A40_40") (pintype "passive"))
      (node (ref "J13") (pin "40") (pinfunction "A40_40") (pintype "passive"))
      (node (ref "J14") (pin "40") (pinfunction "A40_40") (pintype "passive"))
      (node (ref "J15") (pin "40") (pinfunction "A40_40") (pintype "passive"))
      (node (ref "J16") (pin "40") (pinfunction "A40_40") (pintype "passive"))
      (node (ref "J2") (pin "40") (pinfunction "A40_40") (pintype "passive"))
      (node (ref "J3") (pin "40") (pinfunction "A40_40") (pintype "passive"))
      (node (ref "J4") (pin "40") (pinfunction "A40_40") (pintype "passive"))
      (node (ref "J5") (pin "40") (pinfunction "A40_40") (pintype "passive"))
      (node (ref "J6") (pin "40") (pinfunction "A40_40") (pintype "passive"))
      (node (ref "J7") (pin "40") (pinfunction "A40_40") (pintype "passive"))
      (node (ref "J8") (pin "40") (pinfunction "A40_40") (pintype "passive"))
      (node (ref "J9") (pin "40") (pinfunction "A40_40") (pintype "passive"))
      (node (ref "R6") (pin "1") (pinfunction "1_1") (pintype "passive"))
      (node (ref "U9") (pin "14") (pinfunction "DO4+_14") (pintype "passive"))
    )
    (net (code "84") (name "/bus5_p") (class "Default")
      (node (ref "J1") (pin "41") (pinfunction "A41_41") (pintype "passive"))
      (node (ref "J10") (pin "41") (pinfunction "A41_41") (pintype "passive"))
      (node (ref "J11") (pin "41") (pinfunction "A41_41") (pintype "passive"))
      (node (ref "J12") (pin "41") (pinfunction "A41_41") (pintype "passive"))
      (node (ref "J13") (pin "41") (pinfunction "A41_41") (pintype "passive"))
      (node (ref "J14") (pin "41") (pinfunction "A41_41") (pintype "passive"))
      (node (ref "J15") (pin "41") (pinfunction "A41_41") (pintype "passive"))
      (node (ref "J16") (pin "41") (pinfunction "A41_41") (pintype "passive"))
      (node (ref "J2") (pin "41") (pinfunction "A41_41") (pintype "passive"))
      (node (ref "J3") (pin "41") (pinfunction "A41_41") (pintype "passive"))
      (node (ref "J4") (pin "41") (pinfunction "A41_41") (pintype "passive"))
      (node (ref "J5") (pin "41") (pinfunction "A41_41") (pintype "passive"))
      (node (ref "J6") (pin "41") (pinfunction "A41_41") (pintype "passive"))
      (node (ref "J7") (pin "41") (pinfunction "A41_41") (pintype "passive"))
      (node (ref "J8") (pin "41") (pinfunction "A41_41") (pintype "passive"))
      (node (ref "J9") (pin "41") (pinfunction "A41_41") (pintype "passive"))
      (node (ref "R6") (pin "2") (pinfunction "2_2") (pintype "passive"))
      (node (ref "U9") (pin "13") (pinfunction "DO4-_13") (pintype "passive"))
    )
    (net (code "85") (name "/bus6") (class "Default")
      (node (ref "P9") (pin "22") (pinfunction "22_22") (pintype "passive"))
      (node (ref "U11") (pin "1B27") (pinfunction "U2/L24p_1B27") (pintype "passive"))
      (node (ref "U9") (pin "1") (pinfunction "DI1_1") (pintype "passive"))
    )
    (net (code "86") (name "/bus6_n") (class "Default")
      (node (ref "J1") (pin "47") (pinfunction "A47_47") (pintype "passive"))
      (node (ref "J10") (pin "47") (pinfunction "A47_47") (pintype "passive"))
      (node (ref "J11") (pin "47") (pinfunction "A47_47") (pintype "passive"))
      (node (ref "J12") (pin "47") (pinfunction "A47_47") (pintype "passive"))
      (node (ref "J13") (pin "47") (pinfunction "A47_47") (pintype "passive"))
      (node (ref "J14") (pin "47") (pinfunction "A47_47") (pintype "passive"))
      (node (ref "J15") (pin "47") (pinfunction "A47_47") (pintype "passive"))
      (node (ref "J16") (pin "47") (pinfunction "A47_47") (pintype "passive"))
      (node (ref "J2") (pin "47") (pinfunction "A47_47") (pintype "passive"))
      (node (ref "J3") (pin "47") (pinfunction "A47_47") (pintype "passive"))
      (node (ref "J4") (pin "47") (pinfunction "A47_47") (pintype "passive"))
      (node (ref "J5") (pin "47") (pinfunction "A47_47") (pintype "passive"))
      (node (ref "J6") (pin "47") (pinfunction "A47_47") (pintype "passive"))
      (node (ref "J7") (pin "47") (pinfunction "A47_47") (pintype "passive"))
      (node (ref "J8") (pin "47") (pinfunction "A47_47") (pintype "passive"))
      (node (ref "J9") (pin "47") (pinfunction "A47_47") (pintype "passive"))
      (node (ref "R7") (pin "1") (pinfunction "1_1") (pintype "passive"))
      (node (ref "U9") (pin "2") (pinfunction "DO1+_2") (pintype "passive"))
    )
    (net (code "87") (name "/bus6_p") (class "Default")
      (node (ref "J1") (pin "46") (pinfunction "A46_46") (pintype "passive"))
      (node (ref "J10") (pin "46") (pinfunction "A46_46") (pintype "passive"))
      (node (ref "J11") (pin "46") (pinfunction "A46_46") (pintype "passive"))
      (node (ref "J12") (pin "46") (pinfunction "A46_46") (pintype "passive"))
      (node (ref "J13") (pin "46") (pinfunction "A46_46") (pintype "passive"))
      (node (ref "J14") (pin "46") (pinfunction "A46_46") (pintype "passive"))
      (node (ref "J15") (pin "46") (pinfunction "A46_46") (pintype "passive"))
      (node (ref "J16") (pin "46") (pinfunction "A46_46") (pintype "passive"))
      (node (ref "J2") (pin "46") (pinfunction "A46_46") (pintype "passive"))
      (node (ref "J3") (pin "46") (pinfunction "A46_46") (pintype "passive"))
      (node (ref "J4") (pin "46") (pinfunction "A46_46") (pintype "passive"))
      (node (ref "J5") (pin "46") (pinfunction "A46_46") (pintype "passive"))
      (node (ref "J6") (pin "46") (pinfunction "A46_46") (pintype "passive"))
      (node (ref "J7") (pin "46") (pinfunction "A46_46") (pintype "passive"))
      (node (ref "J8") (pin "46") (pinfunction "A46_46") (pintype "passive"))
      (node (ref "J9") (pin "46") (pinfunction "A46_46") (pintype "passive"))
      (node (ref "R7") (pin "2") (pinfunction "2_2") (pintype "passive"))
      (node (ref "U9") (pin "3") (pinfunction "DO1-_3") (pintype "passive"))
    )
    (net (code "88") (name "/bus7") (class "Default")
      (node (ref "P9") (pin "21") (pinfunction "21_21") (pintype "passive"))
      (node (ref "U11") (pin "1B26") (pinfunction "AB7/B10n_1B26") (pintype "passive"))
      (node (ref "U9") (pin "7") (pinfunction "DI2_7") (pintype "passive"))
    )
    (net (code "89") (name "/bus7_n") (class "Default")
      (node (ref "J1") (pin "44") (pinfunction "A44_44") (pintype "passive"))
      (node (ref "J10") (pin "44") (pinfunction "A44_44") (pintype "passive"))
      (node (ref "J11") (pin "44") (pinfunction "A44_44") (pintype "passive"))
      (node (ref "J12") (pin "44") (pinfunction "A44_44") (pintype "passive"))
      (node (ref "J13") (pin "44") (pinfunction "A44_44") (pintype "passive"))
      (node (ref "J14") (pin "44") (pinfunction "A44_44") (pintype "passive"))
      (node (ref "J15") (pin "44") (pinfunction "A44_44") (pintype "passive"))
      (node (ref "J16") (pin "44") (pinfunction "A44_44") (pintype "passive"))
      (node (ref "J2") (pin "44") (pinfunction "A44_44") (pintype "passive"))
      (node (ref "J3") (pin "44") (pinfunction "A44_44") (pintype "passive"))
      (node (ref "J4") (pin "44") (pinfunction "A44_44") (pintype "passive"))
      (node (ref "J5") (pin "44") (pinfunction "A44_44") (pintype "passive"))
      (node (ref "J6") (pin "44") (pinfunction "A44_44") (pintype "passive"))
      (node (ref "J7") (pin "44") (pinfunction "A44_44") (pintype "passive"))
      (node (ref "J8") (pin "44") (pinfunction "A44_44") (pintype "passive"))
      (node (ref "J9") (pin "44") (pinfunction "A44_44") (pintype "passive"))
      (node (ref "R8") (pin "1") (pinfunction "1_1") (pintype "passive"))
      (node (ref "U9") (pin "6") (pinfunction "DO2+_6") (pintype "passive"))
    )
    (net (code "90") (name "/bus7_p") (class "Default")
      (node (ref "J1") (pin "45") (pinfunction "A45_45") (pintype "passive"))
      (node (ref "J10") (pin "45") (pinfunction "A45_45") (pintype "passive"))
      (node (ref "J11") (pin "45") (pinfunction "A45_45") (pintype "passive"))
      (node (ref "J12") (pin "45") (pinfunction "A45_45") (pintype "passive"))
      (node (ref "J13") (pin "45") (pinfunction "A45_45") (pintype "passive"))
      (node (ref "J14") (pin "45") (pinfunction "A45_45") (pintype "passive"))
      (node (ref "J15") (pin "45") (pinfunction "A45_45") (pintype "passive"))
      (node (ref "J16") (pin "45") (pinfunction "A45_45") (pintype "passive"))
      (node (ref "J2") (pin "45") (pinfunction "A45_45") (pintype "passive"))
      (node (ref "J3") (pin "45") (pinfunction "A45_45") (pintype "passive"))
      (node (ref "J4") (pin "45") (pinfunction "A45_45") (pintype "passive"))
      (node (ref "J5") (pin "45") (pinfunction "A45_45") (pintype "passive"))
      (node (ref "J6") (pin "45") (pinfunction "A45_45") (pintype "passive"))
      (node (ref "J7") (pin "45") (pinfunction "A45_45") (pintype "passive"))
      (node (ref "J8") (pin "45") (pinfunction "A45_45") (pintype "passive"))
      (node (ref "J9") (pin "45") (pinfunction "A45_45") (pintype "passive"))
      (node (ref "R8") (pin "2") (pinfunction "2_2") (pintype "passive"))
      (node (ref "U9") (pin "5") (pinfunction "DO2-_5") (pintype "passive"))
    )
    (net (code "91") (name "/bus8") (class "Default")
      (node (ref "P9") (pin "14") (pinfunction "14_14") (pintype "passive"))
      (node (ref "U11") (pin "1B21") (pinfunction "R1/L21n_1B21") (pintype "passive"))
      (node (ref "U8") (pin "9") (pinfunction "DI3_9") (pintype "passive"))
    )
    (net (code "92") (name "/bus8_n") (class "Default")
      (node (ref "J1") (pin "34") (pinfunction "A34_34") (pintype "passive"))
      (node (ref "J10") (pin "34") (pinfunction "A34_34") (pintype "passive"))
      (node (ref "J11") (pin "34") (pinfunction "A34_34") (pintype "passive"))
      (node (ref "J12") (pin "34") (pinfunction "A34_34") (pintype "passive"))
      (node (ref "J13") (pin "34") (pinfunction "A34_34") (pintype "passive"))
      (node (ref "J14") (pin "34") (pinfunction "A34_34") (pintype "passive"))
      (node (ref "J15") (pin "34") (pinfunction "A34_34") (pintype "passive"))
      (node (ref "J16") (pin "34") (pinfunction "A34_34") (pintype "passive"))
      (node (ref "J2") (pin "34") (pinfunction "A34_34") (pintype "passive"))
      (node (ref "J3") (pin "34") (pinfunction "A34_34") (pintype "passive"))
      (node (ref "J4") (pin "34") (pinfunction "A34_34") (pintype "passive"))
      (node (ref "J5") (pin "34") (pinfunction "A34_34") (pintype "passive"))
      (node (ref "J6") (pin "34") (pinfunction "A34_34") (pintype "passive"))
      (node (ref "J7") (pin "34") (pinfunction "A34_34") (pintype "passive"))
      (node (ref "J8") (pin "34") (pinfunction "A34_34") (pintype "passive"))
      (node (ref "J9") (pin "34") (pinfunction "A34_34") (pintype "passive"))
      (node (ref "R9") (pin "1") (pinfunction "1_1") (pintype "passive"))
      (node (ref "U8") (pin "10") (pinfunction "DO3+_10") (pintype "passive"))
    )
    (net (code "93") (name "/bus8_p") (class "Default")
      (node (ref "J1") (pin "33") (pinfunction "A33_33") (pintype "passive"))
      (node (ref "J10") (pin "33") (pinfunction "A33_33") (pintype "passive"))
      (node (ref "J11") (pin "33") (pinfunction "A33_33") (pintype "passive"))
      (node (ref "J12") (pin "33") (pinfunction "A33_33") (pintype "passive"))
      (node (ref "J13") (pin "33") (pinfunction "A33_33") (pintype "passive"))
      (node (ref "J14") (pin "33") (pinfunction "A33_33") (pintype "passive"))
      (node (ref "J15") (pin "33") (pinfunction "A33_33") (pintype "passive"))
      (node (ref "J16") (pin "33") (pinfunction "A33_33") (pintype "passive"))
      (node (ref "J2") (pin "33") (pinfunction "A33_33") (pintype "passive"))
      (node (ref "J3") (pin "33") (pinfunction "A33_33") (pintype "passive"))
      (node (ref "J4") (pin "33") (pinfunction "A33_33") (pintype "passive"))
      (node (ref "J5") (pin "33") (pinfunction "A33_33") (pintype "passive"))
      (node (ref "J6") (pin "33") (pinfunction "A33_33") (pintype "passive"))
      (node (ref "J7") (pin "33") (pinfunction "A33_33") (pintype "passive"))
      (node (ref "J8") (pin "33") (pinfunction "A33_33") (pintype "passive"))
      (node (ref "J9") (pin "33") (pinfunction "A33_33") (pintype "passive"))
      (node (ref "R9") (pin "2") (pinfunction "2_2") (pintype "passive"))
      (node (ref "U8") (pin "11") (pinfunction "DO3-_11") (pintype "passive"))
    )
    (net (code "94") (name "/bus9") (class "Default")
      (node (ref "P9") (pin "13") (pinfunction "13_13") (pintype "passive"))
      (node (ref "U11") (pin "1B20") (pinfunction "W7/B7p_1B20") (pintype "passive"))
      (node (ref "U8") (pin "15") (pinfunction "DI4_15") (pintype "passive"))
    )
    (net (code "95") (name "/bus9_n") (class "Default")
      (node (ref "J1") (pin "31") (pinfunction "A31_31") (pintype "passive"))
      (node (ref "J10") (pin "31") (pinfunction "A31_31") (pintype "passive"))
      (node (ref "J11") (pin "31") (pinfunction "A31_31") (pintype "passive"))
      (node (ref "J12") (pin "31") (pinfunction "A31_31") (pintype "passive"))
      (node (ref "J13") (pin "31") (pinfunction "A31_31") (pintype "passive"))
      (node (ref "J14") (pin "31") (pinfunction "A31_31") (pintype "passive"))
      (node (ref "J15") (pin "31") (pinfunction "A31_31") (pintype "passive"))
      (node (ref "J16") (pin "31") (pinfunction "A31_31") (pintype "passive"))
      (node (ref "J2") (pin "31") (pinfunction "A31_31") (pintype "passive"))
      (node (ref "J3") (pin "31") (pinfunction "A31_31") (pintype "passive"))
      (node (ref "J4") (pin "31") (pinfunction "A31_31") (pintype "passive"))
      (node (ref "J5") (pin "31") (pinfunction "A31_31") (pintype "passive"))
      (node (ref "J6") (pin "31") (pinfunction "A31_31") (pintype "passive"))
      (node (ref "J7") (pin "31") (pinfunction "A31_31") (pintype "passive"))
      (node (ref "J8") (pin "31") (pinfunction "A31_31") (pintype "passive"))
      (node (ref "J9") (pin "31") (pinfunction "A31_31") (pintype "passive"))
      (node (ref "R10") (pin "1") (pinfunction "1_1") (pintype "passive"))
      (node (ref "U8") (pin "14") (pinfunction "DO4+_14") (pintype "passive"))
    )
    (net (code "96") (name "/bus9_p") (class "Default")
      (node (ref "J1") (pin "32") (pinfunction "A32_32") (pintype "passive"))
      (node (ref "J10") (pin "32") (pinfunction "A32_32") (pintype "passive"))
      (node (ref "J11") (pin "32") (pinfunction "A32_32") (pintype "passive"))
      (node (ref "J12") (pin "32") (pinfunction "A32_32") (pintype "passive"))
      (node (ref "J13") (pin "32") (pinfunction "A32_32") (pintype "passive"))
      (node (ref "J14") (pin "32") (pinfunction "A32_32") (pintype "passive"))
      (node (ref "J15") (pin "32") (pinfunction "A32_32") (pintype "passive"))
      (node (ref "J16") (pin "32") (pinfunction "A32_32") (pintype "passive"))
      (node (ref "J2") (pin "32") (pinfunction "A32_32") (pintype "passive"))
      (node (ref "J3") (pin "32") (pinfunction "A32_32") (pintype "passive"))
      (node (ref "J4") (pin "32") (pinfunction "A32_32") (pintype "passive"))
      (node (ref "J5") (pin "32") (pinfunction "A32_32") (pintype "passive"))
      (node (ref "J6") (pin "32") (pinfunction "A32_32") (pintype "passive"))
      (node (ref "J7") (pin "32") (pinfunction "A32_32") (pintype "passive"))
      (node (ref "J8") (pin "32") (pinfunction "A32_32") (pintype "passive"))
      (node (ref "J9") (pin "32") (pinfunction "A32_32") (pintype "passive"))
      (node (ref "R10") (pin "2") (pinfunction "2_2") (pintype "passive"))
      (node (ref "U8") (pin "13") (pinfunction "DO4-_13") (pintype "passive"))
    )
    (net (code "97") (name "/bus10") (class "Default")
      (node (ref "P9") (pin "18") (pinfunction "18_18") (pintype "passive"))
      (node (ref "U11") (pin "1B23") (pinfunction "P4/L23p_1B23") (pintype "passive"))
      (node (ref "U8") (pin "1") (pinfunction "DI1_1") (pintype "passive"))
    )
    (net (code "98") (name "/bus10_n") (class "Default")
      (node (ref "J1") (pin "38") (pinfunction "A38_38") (pintype "passive"))
      (node (ref "J10") (pin "38") (pinfunction "A38_38") (pintype "passive"))
      (node (ref "J11") (pin "38") (pinfunction "A38_38") (pintype "passive"))
      (node (ref "J12") (pin "38") (pinfunction "A38_38") (pintype "passive"))
      (node (ref "J13") (pin "38") (pinfunction "A38_38") (pintype "passive"))
      (node (ref "J14") (pin "38") (pinfunction "A38_38") (pintype "passive"))
      (node (ref "J15") (pin "38") (pinfunction "A38_38") (pintype "passive"))
      (node (ref "J16") (pin "38") (pinfunction "A38_38") (pintype "passive"))
      (node (ref "J2") (pin "38") (pinfunction "A38_38") (pintype "passive"))
      (node (ref "J3") (pin "38") (pinfunction "A38_38") (pintype "passive"))
      (node (ref "J4") (pin "38") (pinfunction "A38_38") (pintype "passive"))
      (node (ref "J5") (pin "38") (pinfunction "A38_38") (pintype "passive"))
      (node (ref "J6") (pin "38") (pinfunction "A38_38") (pintype "passive"))
      (node (ref "J7") (pin "38") (pinfunction "A38_38") (pintype "passive"))
      (node (ref "J8") (pin "38") (pinfunction "A38_38") (pintype "passive"))
      (node (ref "J9") (pin "38") (pinfunction "A38_38") (pintype "passive"))
      (node (ref "R11") (pin "1") (pinfunction "1_1") (pintype "passive"))
      (node (ref "U8") (pin "2") (pinfunction "DO1+_2") (pintype "passive"))
    )
    (net (code "99") (name "/bus10_p") (class "Default")
      (node (ref "J1") (pin "37") (pinfunction "A37_37") (pintype "passive"))
      (node (ref "J10") (pin "37") (pinfunction "A37_37") (pintype "passive"))
      (node (ref "J11") (pin "37") (pinfunction "A37_37") (pintype "passive"))
      (node (ref "J12") (pin "37") (pinfunction "A37_37") (pintype "passive"))
      (node (ref "J13") (pin "37") (pinfunction "A37_37") (pintype "passive"))
      (node (ref "J14") (pin "37") (pinfunction "A37_37") (pintype "passive"))
      (node (ref "J15") (pin "37") (pinfunction "A37_37") (pintype "passive"))
      (node (ref "J16") (pin "37") (pinfunction "A37_37") (pintype "passive"))
      (node (ref "J2") (pin "37") (pinfunction "A37_37") (pintype "passive"))
      (node (ref "J3") (pin "37") (pinfunction "A37_37") (pintype "passive"))
      (node (ref "J4") (pin "37") (pinfunction "A37_37") (pintype "passive"))
      (node (ref "J5") (pin "37") (pinfunction "A37_37") (pintype "passive"))
      (node (ref "J6") (pin "37") (pinfunction "A37_37") (pintype "passive"))
      (node (ref "J7") (pin "37") (pinfunction "A37_37") (pintype "passive"))
      (node (ref "J8") (pin "37") (pinfunction "A37_37") (pintype "passive"))
      (node (ref "J9") (pin "37") (pinfunction "A37_37") (pintype "passive"))
      (node (ref "R11") (pin "2") (pinfunction "2_2") (pintype "passive"))
      (node (ref "U8") (pin "3") (pinfunction "DO1-_3") (pintype "passive"))
    )
    (net (code "100") (name "/bus11") (class "Default")
      (node (ref "P9") (pin "17") (pinfunction "17_17") (pintype "passive"))
      (node (ref "U11") (pin "1B22") (pinfunction "Y7/B7n_1B22") (pintype "passive"))
      (node (ref "U8") (pin "7") (pinfunction "DI2_7") (pintype "passive"))
    )
    (net (code "101") (name "/bus11_n") (class "Default")
      (node (ref "J1") (pin "35") (pinfunction "A35_35") (pintype "passive"))
      (node (ref "J10") (pin "35") (pinfunction "A35_35") (pintype "passive"))
      (node (ref "J11") (pin "35") (pinfunction "A35_35") (pintype "passive"))
      (node (ref "J12") (pin "35") (pinfunction "A35_35") (pintype "passive"))
      (node (ref "J13") (pin "35") (pinfunction "A35_35") (pintype "passive"))
      (node (ref "J14") (pin "35") (pinfunction "A35_35") (pintype "passive"))
      (node (ref "J15") (pin "35") (pinfunction "A35_35") (pintype "passive"))
      (node (ref "J16") (pin "35") (pinfunction "A35_35") (pintype "passive"))
      (node (ref "J2") (pin "35") (pinfunction "A35_35") (pintype "passive"))
      (node (ref "J3") (pin "35") (pinfunction "A35_35") (pintype "passive"))
      (node (ref "J4") (pin "35") (pinfunction "A35_35") (pintype "passive"))
      (node (ref "J5") (pin "35") (pinfunction "A35_35") (pintype "passive"))
      (node (ref "J6") (pin "35") (pinfunction "A35_35") (pintype "passive"))
      (node (ref "J7") (pin "35") (pinfunction "A35_35") (pintype "passive"))
      (node (ref "J8") (pin "35") (pinfunction "A35_35") (pintype "passive"))
      (node (ref "J9") (pin "35") (pinfunction "A35_35") (pintype "passive"))
      (node (ref "R12") (pin "1") (pinfunction "1_1") (pintype "passive"))
      (node (ref "U8") (pin "6") (pinfunction "DO2+_6") (pintype "passive"))
    )
    (net (code "102") (name "/bus11_p") (class "Default")
      (node (ref "J1") (pin "36") (pinfunction "A36_36") (pintype "passive"))
      (node (ref "J10") (pin "36") (pinfunction "A36_36") (pintype "passive"))
      (node (ref "J11") (pin "36") (pinfunction "A36_36") (pintype "passive"))
      (node (ref "J12") (pin "36") (pinfunction "A36_36") (pintype "passive"))
      (node (ref "J13") (pin "36") (pinfunction "A36_36") (pintype "passive"))
      (node (ref "J14") (pin "36") (pinfunction "A36_36") (pintype "passive"))
      (node (ref "J15") (pin "36") (pinfunction "A36_36") (pintype "passive"))
      (node (ref "J16") (pin "36") (pinfunction "A36_36") (pintype "passive"))
      (node (ref "J2") (pin "36") (pinfunction "A36_36") (pintype "passive"))
      (node (ref "J3") (pin "36") (pinfunction "A36_36") (pintype "passive"))
      (node (ref "J4") (pin "36") (pinfunction "A36_36") (pintype "passive"))
      (node (ref "J5") (pin "36") (pinfunction "A36_36") (pintype "passive"))
      (node (ref "J6") (pin "36") (pinfunction "A36_36") (pintype "passive"))
      (node (ref "J7") (pin "36") (pinfunction "A36_36") (pintype "passive"))
      (node (ref "J8") (pin "36") (pinfunction "A36_36") (pintype "passive"))
      (node (ref "J9") (pin "36") (pinfunction "A36_36") (pintype "passive"))
      (node (ref "R12") (pin "2") (pinfunction "2_2") (pintype "passive"))
      (node (ref "U8") (pin "5") (pinfunction "DO2-_5") (pintype "passive"))
    )
    (net (code "103") (name "/bus12") (class "Default")
      (node (ref "P9") (pin "10") (pinfunction "10_10") (pintype "passive"))
      (node (ref "U11") (pin "1B17") (pinfunction "P1/L20n_1B17") (pintype "passive"))
      (node (ref "U7") (pin "9") (pinfunction "DI3_9") (pintype "passive"))
    )
    (net (code "104") (name "/bus12_n") (class "Default")
      (node (ref "J1") (pin "25") (pinfunction "A25_25") (pintype "passive"))
      (node (ref "J10") (pin "25") (pinfunction "A25_25") (pintype "passive"))
      (node (ref "J11") (pin "25") (pinfunction "A25_25") (pintype "passive"))
      (node (ref "J12") (pin "25") (pinfunction "A25_25") (pintype "passive"))
      (node (ref "J13") (pin "25") (pinfunction "A25_25") (pintype "passive"))
      (node (ref "J14") (pin "25") (pinfunction "A25_25") (pintype "passive"))
      (node (ref "J15") (pin "25") (pinfunction "A25_25") (pintype "passive"))
      (node (ref "J16") (pin "25") (pinfunction "A25_25") (pintype "passive"))
      (node (ref "J2") (pin "25") (pinfunction "A25_25") (pintype "passive"))
      (node (ref "J3") (pin "25") (pinfunction "A25_25") (pintype "passive"))
      (node (ref "J4") (pin "25") (pinfunction "A25_25") (pintype "passive"))
      (node (ref "J5") (pin "25") (pinfunction "A25_25") (pintype "passive"))
      (node (ref "J6") (pin "25") (pinfunction "A25_25") (pintype "passive"))
      (node (ref "J7") (pin "25") (pinfunction "A25_25") (pintype "passive"))
      (node (ref "J8") (pin "25") (pinfunction "A25_25") (pintype "passive"))
      (node (ref "J9") (pin "25") (pinfunction "A25_25") (pintype "passive"))
      (node (ref "R13") (pin "1") (pinfunction "1_1") (pintype "passive"))
      (node (ref "U7") (pin "10") (pinfunction "DO3+_10") (pintype "passive"))
    )
    (net (code "105") (name "/bus12_p") (class "Default")
      (node (ref "J1") (pin "24") (pinfunction "A24_24") (pintype "passive"))
      (node (ref "J10") (pin "24") (pinfunction "A24_24") (pintype "passive"))
      (node (ref "J11") (pin "24") (pinfunction "A24_24") (pintype "passive"))
      (node (ref "J12") (pin "24") (pinfunction "A24_24") (pintype "passive"))
      (node (ref "J13") (pin "24") (pinfunction "A24_24") (pintype "passive"))
      (node (ref "J14") (pin "24") (pinfunction "A24_24") (pintype "passive"))
      (node (ref "J15") (pin "24") (pinfunction "A24_24") (pintype "passive"))
      (node (ref "J16") (pin "24") (pinfunction "A24_24") (pintype "passive"))
      (node (ref "J2") (pin "24") (pinfunction "A24_24") (pintype "passive"))
      (node (ref "J3") (pin "24") (pinfunction "A24_24") (pintype "passive"))
      (node (ref "J4") (pin "24") (pinfunction "A24_24") (pintype "passive"))
      (node (ref "J5") (pin "24") (pinfunction "A24_24") (pintype "passive"))
      (node (ref "J6") (pin "24") (pinfunction "A24_24") (pintype "passive"))
      (node (ref "J7") (pin "24") (pinfunction "A24_24") (pintype "passive"))
      (node (ref "J8") (pin "24") (pinfunction "A24_24") (pintype "passive"))
      (node (ref "J9") (pin "24") (pinfunction "A24_24") (pintype "passive"))
      (node (ref "R13") (pin "2") (pinfunction "2_2") (pintype "passive"))
      (node (ref "U7") (pin "11") (pinfunction "DO3-_11") (pintype "passive"))
    )
    (net (code "106") (name "/bus13") (class "Default")
      (node (ref "P9") (pin "9") (pinfunction "9_9") (pintype "passive"))
      (node (ref "U11") (pin "1B16") (pinfunction "AB6/B6p_1B16") (pintype "passive"))
      (node (ref "U7") (pin "15") (pinfunction "DI4_15") (pintype "passive"))
    )
    (net (code "107") (name "/bus13_n") (class "Default")
      (node (ref "J1") (pin "22") (pinfunction "A22_22") (pintype "passive"))
      (node (ref "J10") (pin "22") (pinfunction "A22_22") (pintype "passive"))
      (node (ref "J11") (pin "22") (pinfunction "A22_22") (pintype "passive"))
      (node (ref "J12") (pin "22") (pinfunction "A22_22") (pintype "passive"))
      (node (ref "J13") (pin "22") (pinfunction "A22_22") (pintype "passive"))
      (node (ref "J14") (pin "22") (pinfunction "A22_22") (pintype "passive"))
      (node (ref "J15") (pin "22") (pinfunction "A22_22") (pintype "passive"))
      (node (ref "J16") (pin "22") (pinfunction "A22_22") (pintype "passive"))
      (node (ref "J2") (pin "22") (pinfunction "A22_22") (pintype "passive"))
      (node (ref "J3") (pin "22") (pinfunction "A22_22") (pintype "passive"))
      (node (ref "J4") (pin "22") (pinfunction "A22_22") (pintype "passive"))
      (node (ref "J5") (pin "22") (pinfunction "A22_22") (pintype "passive"))
      (node (ref "J6") (pin "22") (pinfunction "A22_22") (pintype "passive"))
      (node (ref "J7") (pin "22") (pinfunction "A22_22") (pintype "passive"))
      (node (ref "J8") (pin "22") (pinfunction "A22_22") (pintype "passive"))
      (node (ref "J9") (pin "22") (pinfunction "A22_22") (pintype "passive"))
      (node (ref "R14") (pin "1") (pinfunction "1_1") (pintype "passive"))
      (node (ref "U7") (pin "14") (pinfunction "DO4+_14") (pintype "passive"))
    )
    (net (code "108") (name "/bus13_p") (class "Default")
      (node (ref "J1") (pin "23") (pinfunction "A23_23") (pintype "passive"))
      (node (ref "J10") (pin "23") (pinfunction "A23_23") (pintype "passive"))
      (node (ref "J11") (pin "23") (pinfunction "A23_23") (pintype "passive"))
      (node (ref "J12") (pin "23") (pinfunction "A23_23") (pintype "passive"))
      (node (ref "J13") (pin "23") (pinfunction "A23_23") (pintype "passive"))
      (node (ref "J14") (pin "23") (pinfunction "A23_23") (pintype "passive"))
      (node (ref "J15") (pin "23") (pinfunction "A23_23") (pintype "passive"))
      (node (ref "J16") (pin "23") (pinfunction "A23_23") (pintype "passive"))
      (node (ref "J2") (pin "23") (pinfunction "A23_23") (pintype "passive"))
      (node (ref "J3") (pin "23") (pinfunction "A23_23") (pintype "passive"))
      (node (ref "J4") (pin "23") (pinfunction "A23_23") (pintype "passive"))
      (node (ref "J5") (pin "23") (pinfunction "A23_23") (pintype "passive"))
      (node (ref "J6") (pin "23") (pinfunction "A23_23") (pintype "passive"))
      (node (ref "J7") (pin "23") (pinfunction "A23_23") (pintype "passive"))
      (node (ref "J8") (pin "23") (pinfunction "A23_23") (pintype "passive"))
      (node (ref "J9") (pin "23") (pinfunction "A23_23") (pintype "passive"))
      (node (ref "R14") (pin "2") (pinfunction "2_2") (pintype "passive"))
      (node (ref "U7") (pin "13") (pinfunction "DO4-_13") (pintype "passive"))
    )
    (net (code "109") (name "/bus14") (class "Default")
      (node (ref "P9") (pin "12") (pinfunction "12_12") (pintype "passive"))
      (node (ref "U11") (pin "1B19") (pinfunction "R2/L21p_1B19") (pintype "passive"))
      (node (ref "U7") (pin "1") (pinfunction "DI1_1") (pintype "passive"))
    )
    (net (code "110") (name "/bus14_n") (class "Default")
      (node (ref "J1") (pin "29") (pinfunction "A29_29") (pintype "passive"))
      (node (ref "J10") (pin "29") (pinfunction "A29_29") (pintype "passive"))
      (node (ref "J11") (pin "29") (pinfunction "A29_29") (pintype "passive"))
      (node (ref "J12") (pin "29") (pinfunction "A29_29") (pintype "passive"))
      (node (ref "J13") (pin "29") (pinfunction "A29_29") (pintype "passive"))
      (node (ref "J14") (pin "29") (pinfunction "A29_29") (pintype "passive"))
      (node (ref "J15") (pin "29") (pinfunction "A29_29") (pintype "passive"))
      (node (ref "J16") (pin "29") (pinfunction "A29_29") (pintype "passive"))
      (node (ref "J2") (pin "29") (pinfunction "A29_29") (pintype "passive"))
      (node (ref "J3") (pin "29") (pinfunction "A29_29") (pintype "passive"))
      (node (ref "J4") (pin "29") (pinfunction "A29_29") (pintype "passive"))
      (node (ref "J5") (pin "29") (pinfunction "A29_29") (pintype "passive"))
      (node (ref "J6") (pin "29") (pinfunction "A29_29") (pintype "passive"))
      (node (ref "J7") (pin "29") (pinfunction "A29_29") (pintype "passive"))
      (node (ref "J8") (pin "29") (pinfunction "A29_29") (pintype "passive"))
      (node (ref "J9") (pin "29") (pinfunction "A29_29") (pintype "passive"))
      (node (ref "R15") (pin "1") (pinfunction "1_1") (pintype "passive"))
      (node (ref "U7") (pin "2") (pinfunction "DO1+_2") (pintype "passive"))
    )
    (net (code "111") (name "/bus14_p") (class "Default")
      (node (ref "J1") (pin "28") (pinfunction "A28_28") (pintype "passive"))
      (node (ref "J10") (pin "28") (pinfunction "A28_28") (pintype "passive"))
      (node (ref "J11") (pin "28") (pinfunction "A28_28") (pintype "passive"))
      (node (ref "J12") (pin "28") (pinfunction "A28_28") (pintype "passive"))
      (node (ref "J13") (pin "28") (pinfunction "A28_28") (pintype "passive"))
      (node (ref "J14") (pin "28") (pinfunction "A28_28") (pintype "passive"))
      (node (ref "J15") (pin "28") (pinfunction "A28_28") (pintype "passive"))
      (node (ref "J16") (pin "28") (pinfunction "A28_28") (pintype "passive"))
      (node (ref "J2") (pin "28") (pinfunction "A28_28") (pintype "passive"))
      (node (ref "J3") (pin "28") (pinfunction "A28_28") (pintype "passive"))
      (node (ref "J4") (pin "28") (pinfunction "A28_28") (pintype "passive"))
      (node (ref "J5") (pin "28") (pinfunction "A28_28") (pintype "passive"))
      (node (ref "J6") (pin "28") (pinfunction "A28_28") (pintype "passive"))
      (node (ref "J7") (pin "28") (pinfunction "A28_28") (pintype "passive"))
      (node (ref "J8") (pin "28") (pinfunction "A28_28") (pintype "passive"))
      (node (ref "J9") (pin "28") (pinfunction "A28_28") (pintype "passive"))
      (node (ref "R15") (pin "2") (pinfunction "2_2") (pintype "passive"))
      (node (ref "U7") (pin "3") (pinfunction "DO1-_3") (pintype "passive"))
    )
    (net (code "112") (name "/bus15") (class "Default")
      (node (ref "P9") (pin "11") (pinfunction "11_11") (pintype "passive"))
      (node (ref "U11") (pin "1B18") (pinfunction "AB5/B6n_1B18") (pintype "passive"))
      (node (ref "U7") (pin "7") (pinfunction "DI2_7") (pintype "passive"))
    )
    (net (code "113") (name "/bus15_n") (class "Default")
      (node (ref "J1") (pin "26") (pinfunction "A26_26") (pintype "passive"))
      (node (ref "J10") (pin "26") (pinfunction "A26_26") (pintype "passive"))
      (node (ref "J11") (pin "26") (pinfunction "A26_26") (pintype "passive"))
      (node (ref "J12") (pin "26") (pinfunction "A26_26") (pintype "passive"))
      (node (ref "J13") (pin "26") (pinfunction "A26_26") (pintype "passive"))
      (node (ref "J14") (pin "26") (pinfunction "A26_26") (pintype "passive"))
      (node (ref "J15") (pin "26") (pinfunction "A26_26") (pintype "passive"))
      (node (ref "J16") (pin "26") (pinfunction "A26_26") (pintype "passive"))
      (node (ref "J2") (pin "26") (pinfunction "A26_26") (pintype "passive"))
      (node (ref "J3") (pin "26") (pinfunction "A26_26") (pintype "passive"))
      (node (ref "J4") (pin "26") (pinfunction "A26_26") (pintype "passive"))
      (node (ref "J5") (pin "26") (pinfunction "A26_26") (pintype "passive"))
      (node (ref "J6") (pin "26") (pinfunction "A26_26") (pintype "passive"))
      (node (ref "J7") (pin "26") (pinfunction "A26_26") (pintype "passive"))
      (node (ref "J8") (pin "26") (pinfunction "A26_26") (pintype "passive"))
      (node (ref "J9") (pin "26") (pinfunction "A26_26") (pintype "passive"))
      (node (ref "R16") (pin "1") (pinfunction "1_1") (pintype "passive"))
      (node (ref "U7") (pin "6") (pinfunction "DO2+_6") (pintype "passive"))
    )
    (net (code "114") (name "/bus15_p") (class "Default")
      (node (ref "J1") (pin "27") (pinfunction "A27_27") (pintype "passive"))
      (node (ref "J10") (pin "27") (pinfunction "A27_27") (pintype "passive"))
      (node (ref "J11") (pin "27") (pinfunction "A27_27") (pintype "passive"))
      (node (ref "J12") (pin "27") (pinfunction "A27_27") (pintype "passive"))
      (node (ref "J13") (pin "27") (pinfunction "A27_27") (pintype "passive"))
      (node (ref "J14") (pin "27") (pinfunction "A27_27") (pintype "passive"))
      (node (ref "J15") (pin "27") (pinfunction "A27_27") (pintype "passive"))
      (node (ref "J16") (pin "27") (pinfunction "A27_27") (pintype "passive"))
      (node (ref "J2") (pin "27") (pinfunction "A27_27") (pintype "passive"))
      (node (ref "J3") (pin "27") (pinfunction "A27_27") (pintype "passive"))
      (node (ref "J4") (pin "27") (pinfunction "A27_27") (pintype "passive"))
      (node (ref "J5") (pin "27") (pinfunction "A27_27") (pintype "passive"))
      (node (ref "J6") (pin "27") (pinfunction "A27_27") (pintype "passive"))
      (node (ref "J7") (pin "27") (pinfunction "A27_27") (pintype "passive"))
      (node (ref "J8") (pin "27") (pinfunction "A27_27") (pintype "passive"))
      (node (ref "J9") (pin "27") (pinfunction "A27_27") (pintype "passive"))
      (node (ref "R16") (pin "2") (pinfunction "2_2") (pintype "passive"))
      (node (ref "U7") (pin "5") (pinfunction "DO2-_5") (pintype "passive"))
    )
    (net (code "115") (name "/bus16") (class "Default")
      (node (ref "P7") (pin "16") (pinfunction "16_16") (pintype "passive"))
      (node (ref "U11") (pin "1A23") (pinfunction "W8/IO_1A23") (pintype "passive"))
      (node (ref "U6") (pin "9") (pinfunction "DI3_9") (pintype "passive"))
    )
    (net (code "116") (name "/bus16_n") (class "Default")
      (node (ref "J1") (pin "113") (pinfunction "B53_113") (pintype "passive"))
      (node (ref "J10") (pin "113") (pinfunction "B53_113") (pintype "passive"))
      (node (ref "J11") (pin "113") (pinfunction "B53_113") (pintype "passive"))
      (node (ref "J12") (pin "113") (pinfunction "B53_113") (pintype "passive"))
      (node (ref "J13") (pin "113") (pinfunction "B53_113") (pintype "passive"))
      (node (ref "J14") (pin "113") (pinfunction "B53_113") (pintype "passive"))
      (node (ref "J15") (pin "113") (pinfunction "B53_113") (pintype "passive"))
      (node (ref "J16") (pin "113") (pinfunction "B53_113") (pintype "passive"))
      (node (ref "J2") (pin "113") (pinfunction "B53_113") (pintype "passive"))
      (node (ref "J3") (pin "113") (pinfunction "B53_113") (pintype "passive"))
      (node (ref "J4") (pin "113") (pinfunction "B53_113") (pintype "passive"))
      (node (ref "J5") (pin "113") (pinfunction "B53_113") (pintype "passive"))
      (node (ref "J6") (pin "113") (pinfunction "B53_113") (pintype "passive"))
      (node (ref "J7") (pin "113") (pinfunction "B53_113") (pintype "passive"))
      (node (ref "J8") (pin "113") (pinfunction "B53_113") (pintype "passive"))
      (node (ref "J9") (pin "113") (pinfunction "B53_113") (pintype "passive"))
      (node (ref "R17") (pin "1") (pinfunction "1_1") (pintype "passive"))
      (node (ref "U6") (pin "10") (pinfunction "DO3+_10") (pintype "passive"))
    )
    (net (code "117") (name "/bus16_p") (class "Default")
      (node (ref "J1") (pin "114") (pinfunction "B54_114") (pintype "passive"))
      (node (ref "J10") (pin "114") (pinfunction "B54_114") (pintype "passive"))
      (node (ref "J11") (pin "114") (pinfunction "B54_114") (pintype "passive"))
      (node (ref "J12") (pin "114") (pinfunction "B54_114") (pintype "passive"))
      (node (ref "J13") (pin "114") (pinfunction "B54_114") (pintype "passive"))
      (node (ref "J14") (pin "114") (pinfunction "B54_114") (pintype "passive"))
      (node (ref "J15") (pin "114") (pinfunction "B54_114") (pintype "passive"))
      (node (ref "J16") (pin "114") (pinfunction "B54_114") (pintype "passive"))
      (node (ref "J2") (pin "114") (pinfunction "B54_114") (pintype "passive"))
      (node (ref "J3") (pin "114") (pinfunction "B54_114") (pintype "passive"))
      (node (ref "J4") (pin "114") (pinfunction "B54_114") (pintype "passive"))
      (node (ref "J5") (pin "114") (pinfunction "B54_114") (pintype "passive"))
      (node (ref "J6") (pin "114") (pinfunction "B54_114") (pintype "passive"))
      (node (ref "J7") (pin "114") (pinfunction "B54_114") (pintype "passive"))
      (node (ref "J8") (pin "114") (pinfunction "B54_114") (pintype "passive"))
      (node (ref "J9") (pin "114") (pinfunction "B54_114") (pintype "passive"))
      (node (ref "R17") (pin "2") (pinfunction "2_2") (pintype "passive"))
      (node (ref "U6") (pin "11") (pinfunction "DO3-_11") (pintype "passive"))
    )
    (net (code "118") (name "/bus17") (class "Default")
      (node (ref "P7") (pin "15") (pinfunction "15_15") (pintype "passive"))
      (node (ref "U11") (pin "1A20") (pinfunction "U10/B16n_1A20") (pintype "passive"))
      (node (ref "U6") (pin "15") (pinfunction "DI4_15") (pintype "passive"))
    )
    (net (code "119") (name "/bus17_n") (class "Default")
      (node (ref "J1") (pin "116") (pinfunction "B56_116") (pintype "passive"))
      (node (ref "J10") (pin "116") (pinfunction "B56_116") (pintype "passive"))
      (node (ref "J11") (pin "116") (pinfunction "B56_116") (pintype "passive"))
      (node (ref "J12") (pin "116") (pinfunction "B56_116") (pintype "passive"))
      (node (ref "J13") (pin "116") (pinfunction "B56_116") (pintype "passive"))
      (node (ref "J14") (pin "116") (pinfunction "B56_116") (pintype "passive"))
      (node (ref "J15") (pin "116") (pinfunction "B56_116") (pintype "passive"))
      (node (ref "J16") (pin "116") (pinfunction "B56_116") (pintype "passive"))
      (node (ref "J2") (pin "116") (pinfunction "B56_116") (pintype "passive"))
      (node (ref "J3") (pin "116") (pinfunction "B56_116") (pintype "passive"))
      (node (ref "J4") (pin "116") (pinfunction "B56_116") (pintype "passive"))
      (node (ref "J5") (pin "116") (pinfunction "B56_116") (pintype "passive"))
      (node (ref "J6") (pin "116") (pinfunction "B56_116") (pintype "passive"))
      (node (ref "J7") (pin "116") (pinfunction "B56_116") (pintype "passive"))
      (node (ref "J8") (pin "116") (pinfunction "B56_116") (pintype "passive"))
      (node (ref "J9") (pin "116") (pinfunction "B56_116") (pintype "passive"))
      (node (ref "R18") (pin "1") (pinfunction "1_1") (pintype "passive"))
      (node (ref "U6") (pin "14") (pinfunction "DO4+_14") (pintype "passive"))
    )
    (net (code "120") (name "/bus17_p") (class "Default")
      (node (ref "J1") (pin "115") (pinfunction "B55_115") (pintype "passive"))
      (node (ref "J10") (pin "115") (pinfunction "B55_115") (pintype "passive"))
      (node (ref "J11") (pin "115") (pinfunction "B55_115") (pintype "passive"))
      (node (ref "J12") (pin "115") (pinfunction "B55_115") (pintype "passive"))
      (node (ref "J13") (pin "115") (pinfunction "B55_115") (pintype "passive"))
      (node (ref "J14") (pin "115") (pinfunction "B55_115") (pintype "passive"))
      (node (ref "J15") (pin "115") (pinfunction "B55_115") (pintype "passive"))
      (node (ref "J16") (pin "115") (pinfunction "B55_115") (pintype "passive"))
      (node (ref "J2") (pin "115") (pinfunction "B55_115") (pintype "passive"))
      (node (ref "J3") (pin "115") (pinfunction "B55_115") (pintype "passive"))
      (node (ref "J4") (pin "115") (pinfunction "B55_115") (pintype "passive"))
      (node (ref "J5") (pin "115") (pinfunction "B55_115") (pintype "passive"))
      (node (ref "J6") (pin "115") (pinfunction "B55_115") (pintype "passive"))
      (node (ref "J7") (pin "115") (pinfunction "B55_115") (pintype "passive"))
      (node (ref "J8") (pin "115") (pinfunction "B55_115") (pintype "passive"))
      (node (ref "J9") (pin "115") (pinfunction "B55_115") (pintype "passive"))
      (node (ref "R18") (pin "2") (pinfunction "2_2") (pintype "passive"))
      (node (ref "U6") (pin "13") (pinfunction "DO4-_13") (pintype "passive"))
    )
    (net (code "121") (name "/bus18") (class "Default")
      (node (ref "P7") (pin "18") (pinfunction "18_18") (pintype "passive"))
      (node (ref "U11") (pin "1A29") (pinfunction "V10/B15p_1A29") (pintype "passive"))
      (node (ref "U6") (pin "1") (pinfunction "DI1_1") (pintype "passive"))
    )
    (net (code "122") (name "/bus18_n") (class "Default")
      (node (ref "J1") (pin "109") (pinfunction "B49_109") (pintype "passive"))
      (node (ref "J10") (pin "109") (pinfunction "B49_109") (pintype "passive"))
      (node (ref "J11") (pin "109") (pinfunction "B49_109") (pintype "passive"))
      (node (ref "J12") (pin "109") (pinfunction "B49_109") (pintype "passive"))
      (node (ref "J13") (pin "109") (pinfunction "B49_109") (pintype "passive"))
      (node (ref "J14") (pin "109") (pinfunction "B49_109") (pintype "passive"))
      (node (ref "J15") (pin "109") (pinfunction "B49_109") (pintype "passive"))
      (node (ref "J16") (pin "109") (pinfunction "B49_109") (pintype "passive"))
      (node (ref "J2") (pin "109") (pinfunction "B49_109") (pintype "passive"))
      (node (ref "J3") (pin "109") (pinfunction "B49_109") (pintype "passive"))
      (node (ref "J4") (pin "109") (pinfunction "B49_109") (pintype "passive"))
      (node (ref "J5") (pin "109") (pinfunction "B49_109") (pintype "passive"))
      (node (ref "J6") (pin "109") (pinfunction "B49_109") (pintype "passive"))
      (node (ref "J7") (pin "109") (pinfunction "B49_109") (pintype "passive"))
      (node (ref "J8") (pin "109") (pinfunction "B49_109") (pintype "passive"))
      (node (ref "J9") (pin "109") (pinfunction "B49_109") (pintype "passive"))
      (node (ref "R19") (pin "1") (pinfunction "1_1") (pintype "passive"))
      (node (ref "U6") (pin "2") (pinfunction "DO1+_2") (pintype "passive"))
    )
    (net (code "123") (name "/bus18_p") (class "Default")
      (node (ref "J1") (pin "110") (pinfunction "B50_110") (pintype "passive"))
      (node (ref "J10") (pin "110") (pinfunction "B50_110") (pintype "passive"))
      (node (ref "J11") (pin "110") (pinfunction "B50_110") (pintype "passive"))
      (node (ref "J12") (pin "110") (pinfunction "B50_110") (pintype "passive"))
      (node (ref "J13") (pin "110") (pinfunction "B50_110") (pintype "passive"))
      (node (ref "J14") (pin "110") (pinfunction "B50_110") (pintype "passive"))
      (node (ref "J15") (pin "110") (pinfunction "B50_110") (pintype "passive"))
      (node (ref "J16") (pin "110") (pinfunction "B50_110") (pintype "passive"))
      (node (ref "J2") (pin "110") (pinfunction "B50_110") (pintype "passive"))
      (node (ref "J3") (pin "110") (pinfunction "B50_110") (pintype "passive"))
      (node (ref "J4") (pin "110") (pinfunction "B50_110") (pintype "passive"))
      (node (ref "J5") (pin "110") (pinfunction "B50_110") (pintype "passive"))
      (node (ref "J6") (pin "110") (pinfunction "B50_110") (pintype "passive"))
      (node (ref "J7") (pin "110") (pinfunction "B50_110") (pintype "passive"))
      (node (ref "J8") (pin "110") (pinfunction "B50_110") (pintype "passive"))
      (node (ref "J9") (pin "110") (pinfunction "B50_110") (pintype "passive"))
      (node (ref "R19") (pin "2") (pinfunction "2_2") (pintype "passive"))
      (node (ref "U6") (pin "3") (pinfunction "DO1-_3") (pintype "passive"))
    )
    (net (code "124") (name "/bus19") (class "Default")
      (node (ref "P7") (pin "17") (pinfunction "17_17") (pintype "passive"))
      (node (ref "U11") (pin "1A28") (pinfunction "V8/B8n_1A28") (pintype "passive"))
      (node (ref "U6") (pin "7") (pinfunction "DI2_7") (pintype "passive"))
    )
    (net (code "125") (name "/bus19_n") (class "Default")
      (node (ref "J1") (pin "112") (pinfunction "B52_112") (pintype "passive"))
      (node (ref "J10") (pin "112") (pinfunction "B52_112") (pintype "passive"))
      (node (ref "J11") (pin "112") (pinfunction "B52_112") (pintype "passive"))
      (node (ref "J12") (pin "112") (pinfunction "B52_112") (pintype "passive"))
      (node (ref "J13") (pin "112") (pinfunction "B52_112") (pintype "passive"))
      (node (ref "J14") (pin "112") (pinfunction "B52_112") (pintype "passive"))
      (node (ref "J15") (pin "112") (pinfunction "B52_112") (pintype "passive"))
      (node (ref "J16") (pin "112") (pinfunction "B52_112") (pintype "passive"))
      (node (ref "J2") (pin "112") (pinfunction "B52_112") (pintype "passive"))
      (node (ref "J3") (pin "112") (pinfunction "B52_112") (pintype "passive"))
      (node (ref "J4") (pin "112") (pinfunction "B52_112") (pintype "passive"))
      (node (ref "J5") (pin "112") (pinfunction "B52_112") (pintype "passive"))
      (node (ref "J6") (pin "112") (pinfunction "B52_112") (pintype "passive"))
      (node (ref "J7") (pin "112") (pinfunction "B52_112") (pintype "passive"))
      (node (ref "J8") (pin "112") (pinfunction "B52_112") (pintype "passive"))
      (node (ref "J9") (pin "112") (pinfunction "B52_112") (pintype "passive"))
      (node (ref "R20") (pin "1") (pinfunction "1_1") (pintype "passive"))
      (node (ref "U6") (pin "6") (pinfunction "DO2+_6") (pintype "passive"))
    )
    (net (code "126") (name "/bus19_p") (class "Default")
      (node (ref "J1") (pin "111") (pinfunction "B51_111") (pintype "passive"))
      (node (ref "J10") (pin "111") (pinfunction "B51_111") (pintype "passive"))
      (node (ref "J11") (pin "111") (pinfunction "B51_111") (pintype "passive"))
      (node (ref "J12") (pin "111") (pinfunction "B51_111") (pintype "passive"))
      (node (ref "J13") (pin "111") (pinfunction "B51_111") (pintype "passive"))
      (node (ref "J14") (pin "111") (pinfunction "B51_111") (pintype "passive"))
      (node (ref "J15") (pin "111") (pinfunction "B51_111") (pintype "passive"))
      (node (ref "J16") (pin "111") (pinfunction "B51_111") (pintype "passive"))
      (node (ref "J2") (pin "111") (pinfunction "B51_111") (pintype "passive"))
      (node (ref "J3") (pin "111") (pinfunction "B51_111") (pintype "passive"))
      (node (ref "J4") (pin "111") (pinfunction "B51_111") (pintype "passive"))
      (node (ref "J5") (pin "111") (pinfunction "B51_111") (pintype "passive"))
      (node (ref "J6") (pin "111") (pinfunction "B51_111") (pintype "passive"))
      (node (ref "J7") (pin "111") (pinfunction "B51_111") (pintype "passive"))
      (node (ref "J8") (pin "111") (pinfunction "B51_111") (pintype "passive"))
      (node (ref "J9") (pin "111") (pinfunction "B51_111") (pintype "passive"))
      (node (ref "R20") (pin "2") (pinfunction "2_2") (pintype "passive"))
      (node (ref "U6") (pin "5") (pinfunction "DO2-_5") (pintype "passive"))
    )
    (net (code "127") (name "/bus20") (class "Default")
      (node (ref "P7") (pin "20") (pinfunction "20_20") (pintype "passive"))
      (node (ref "U11") (pin "1A31") (pinfunction "U9/B8p_1A31") (pintype "passive"))
      (node (ref "U5") (pin "9") (pinfunction "DI3_9") (pintype "passive"))
    )
    (net (code "128") (name "/bus20_n") (class "Default")
      (node (ref "J1") (pin "104") (pinfunction "B44_104") (pintype "passive"))
      (node (ref "J10") (pin "104") (pinfunction "B44_104") (pintype "passive"))
      (node (ref "J11") (pin "104") (pinfunction "B44_104") (pintype "passive"))
      (node (ref "J12") (pin "104") (pinfunction "B44_104") (pintype "passive"))
      (node (ref "J13") (pin "104") (pinfunction "B44_104") (pintype "passive"))
      (node (ref "J14") (pin "104") (pinfunction "B44_104") (pintype "passive"))
      (node (ref "J15") (pin "104") (pinfunction "B44_104") (pintype "passive"))
      (node (ref "J16") (pin "104") (pinfunction "B44_104") (pintype "passive"))
      (node (ref "J2") (pin "104") (pinfunction "B44_104") (pintype "passive"))
      (node (ref "J3") (pin "104") (pinfunction "B44_104") (pintype "passive"))
      (node (ref "J4") (pin "104") (pinfunction "B44_104") (pintype "passive"))
      (node (ref "J5") (pin "104") (pinfunction "B44_104") (pintype "passive"))
      (node (ref "J6") (pin "104") (pinfunction "B44_104") (pintype "passive"))
      (node (ref "J7") (pin "104") (pinfunction "B44_104") (pintype "passive"))
      (node (ref "J8") (pin "104") (pinfunction "B44_104") (pintype "passive"))
      (node (ref "J9") (pin "104") (pinfunction "B44_104") (pintype "passive"))
      (node (ref "R21") (pin "1") (pinfunction "1_1") (pintype "passive"))
      (node (ref "U5") (pin "10") (pinfunction "DO3+_10") (pintype "passive"))
    )
    (net (code "129") (name "/bus20_p") (class "Default")
      (node (ref "J1") (pin "105") (pinfunction "B45_105") (pintype "passive"))
      (node (ref "J10") (pin "105") (pinfunction "B45_105") (pintype "passive"))
      (node (ref "J11") (pin "105") (pinfunction "B45_105") (pintype "passive"))
      (node (ref "J12") (pin "105") (pinfunction "B45_105") (pintype "passive"))
      (node (ref "J13") (pin "105") (pinfunction "B45_105") (pintype "passive"))
      (node (ref "J14") (pin "105") (pinfunction "B45_105") (pintype "passive"))
      (node (ref "J15") (pin "105") (pinfunction "B45_105") (pintype "passive"))
      (node (ref "J16") (pin "105") (pinfunction "B45_105") (pintype "passive"))
      (node (ref "J2") (pin "105") (pinfunction "B45_105") (pintype "passive"))
      (node (ref "J3") (pin "105") (pinfunction "B45_105") (pintype "passive"))
      (node (ref "J4") (pin "105") (pinfunction "B45_105") (pintype "passive"))
      (node (ref "J5") (pin "105") (pinfunction "B45_105") (pintype "passive"))
      (node (ref "J6") (pin "105") (pinfunction "B45_105") (pintype "passive"))
      (node (ref "J7") (pin "105") (pinfunction "B45_105") (pintype "passive"))
      (node (ref "J8") (pin "105") (pinfunction "B45_105") (pintype "passive"))
      (node (ref "J9") (pin "105") (pinfunction "B45_105") (pintype "passive"))
      (node (ref "R21") (pin "2") (pinfunction "2_2") (pintype "passive"))
      (node (ref "U5") (pin "11") (pinfunction "DO3-_11") (pintype "passive"))
    )
    (net (code "130") (name "/bus21") (class "Default")
      (node (ref "P7") (pin "19") (pinfunction "19_19") (pintype "passive"))
      (node (ref "U11") (pin "1A30") (pinfunction "Y6/IO_1A30") (pintype "passive"))
      (node (ref "U5") (pin "15") (pinfunction "DI4_15") (pintype "passive"))
    )
    (net (code "131") (name "/bus21_n") (class "Default")
      (node (ref "J1") (pin "107") (pinfunction "B47_107") (pintype "passive"))
      (node (ref "J10") (pin "107") (pinfunction "B47_107") (pintype "passive"))
      (node (ref "J11") (pin "107") (pinfunction "B47_107") (pintype "passive"))
      (node (ref "J12") (pin "107") (pinfunction "B47_107") (pintype "passive"))
      (node (ref "J13") (pin "107") (pinfunction "B47_107") (pintype "passive"))
      (node (ref "J14") (pin "107") (pinfunction "B47_107") (pintype "passive"))
      (node (ref "J15") (pin "107") (pinfunction "B47_107") (pintype "passive"))
      (node (ref "J16") (pin "107") (pinfunction "B47_107") (pintype "passive"))
      (node (ref "J2") (pin "107") (pinfunction "B47_107") (pintype "passive"))
      (node (ref "J3") (pin "107") (pinfunction "B47_107") (pintype "passive"))
      (node (ref "J4") (pin "107") (pinfunction "B47_107") (pintype "passive"))
      (node (ref "J5") (pin "107") (pinfunction "B47_107") (pintype "passive"))
      (node (ref "J6") (pin "107") (pinfunction "B47_107") (pintype "passive"))
      (node (ref "J7") (pin "107") (pinfunction "B47_107") (pintype "passive"))
      (node (ref "J8") (pin "107") (pinfunction "B47_107") (pintype "passive"))
      (node (ref "J9") (pin "107") (pinfunction "B47_107") (pintype "passive"))
      (node (ref "R22") (pin "1") (pinfunction "1_1") (pintype "passive"))
      (node (ref "U5") (pin "14") (pinfunction "DO4+_14") (pintype "passive"))
    )
    (net (code "132") (name "/bus21_p") (class "Default")
      (node (ref "J1") (pin "106") (pinfunction "B46_106") (pintype "passive"))
      (node (ref "J10") (pin "106") (pinfunction "B46_106") (pintype "passive"))
      (node (ref "J11") (pin "106") (pinfunction "B46_106") (pintype "passive"))
      (node (ref "J12") (pin "106") (pinfunction "B46_106") (pintype "passive"))
      (node (ref "J13") (pin "106") (pinfunction "B46_106") (pintype "passive"))
      (node (ref "J14") (pin "106") (pinfunction "B46_106") (pintype "passive"))
      (node (ref "J15") (pin "106") (pinfunction "B46_106") (pintype "passive"))
      (node (ref "J16") (pin "106") (pinfunction "B46_106") (pintype "passive"))
      (node (ref "J2") (pin "106") (pinfunction "B46_106") (pintype "passive"))
      (node (ref "J3") (pin "106") (pinfunction "B46_106") (pintype "passive"))
      (node (ref "J4") (pin "106") (pinfunction "B46_106") (pintype "passive"))
      (node (ref "J5") (pin "106") (pinfunction "B46_106") (pintype "passive"))
      (node (ref "J6") (pin "106") (pinfunction "B46_106") (pintype "passive"))
      (node (ref "J7") (pin "106") (pinfunction "B46_106") (pintype "passive"))
      (node (ref "J8") (pin "106") (pinfunction "B46_106") (pintype "passive"))
      (node (ref "J9") (pin "106") (pinfunction "B46_106") (pintype "passive"))
      (node (ref "R22") (pin "2") (pinfunction "2_2") (pintype "passive"))
      (node (ref "U5") (pin "13") (pinfunction "DO4-_13") (pintype "passive"))
    )
    (net (code "133") (name "/bus22") (class "Default")
      (node (ref "P7") (pin "26") (pinfunction "26_26") (pintype "passive"))
      (node (ref "U11") (pin "1A33") (pinfunction "Y3/B3n_1A33") (pintype "passive"))
      (node (ref "U5") (pin "1") (pinfunction "DI1_1") (pintype "passive"))
    )
    (net (code "134") (name "/bus22_n") (class "Default")
      (node (ref "J1") (pin "100") (pinfunction "B40_100") (pintype "passive"))
      (node (ref "J10") (pin "100") (pinfunction "B40_100") (pintype "passive"))
      (node (ref "J11") (pin "100") (pinfunction "B40_100") (pintype "passive"))
      (node (ref "J12") (pin "100") (pinfunction "B40_100") (pintype "passive"))
      (node (ref "J13") (pin "100") (pinfunction "B40_100") (pintype "passive"))
      (node (ref "J14") (pin "100") (pinfunction "B40_100") (pintype "passive"))
      (node (ref "J15") (pin "100") (pinfunction "B40_100") (pintype "passive"))
      (node (ref "J16") (pin "100") (pinfunction "B40_100") (pintype "passive"))
      (node (ref "J2") (pin "100") (pinfunction "B40_100") (pintype "passive"))
      (node (ref "J3") (pin "100") (pinfunction "B40_100") (pintype "passive"))
      (node (ref "J4") (pin "100") (pinfunction "B40_100") (pintype "passive"))
      (node (ref "J5") (pin "100") (pinfunction "B40_100") (pintype "passive"))
      (node (ref "J6") (pin "100") (pinfunction "B40_100") (pintype "passive"))
      (node (ref "J7") (pin "100") (pinfunction "B40_100") (pintype "passive"))
      (node (ref "J8") (pin "100") (pinfunction "B40_100") (pintype "passive"))
      (node (ref "J9") (pin "100") (pinfunction "B40_100") (pintype "passive"))
      (node (ref "R23") (pin "1") (pinfunction "1_1") (pintype "passive"))
      (node (ref "U5") (pin "2") (pinfunction "DO1+_2") (pintype "passive"))
    )
    (net (code "135") (name "/bus22_p") (class "Default")
      (node (ref "J1") (pin "101") (pinfunction "B41_101") (pintype "passive"))
      (node (ref "J10") (pin "101") (pinfunction "B41_101") (pintype "passive"))
      (node (ref "J11") (pin "101") (pinfunction "B41_101") (pintype "passive"))
      (node (ref "J12") (pin "101") (pinfunction "B41_101") (pintype "passive"))
      (node (ref "J13") (pin "101") (pinfunction "B41_101") (pintype "passive"))
      (node (ref "J14") (pin "101") (pinfunction "B41_101") (pintype "passive"))
      (node (ref "J15") (pin "101") (pinfunction "B41_101") (pintype "passive"))
      (node (ref "J16") (pin "101") (pinfunction "B41_101") (pintype "passive"))
      (node (ref "J2") (pin "101") (pinfunction "B41_101") (pintype "passive"))
      (node (ref "J3") (pin "101") (pinfunction "B41_101") (pintype "passive"))
      (node (ref "J4") (pin "101") (pinfunction "B41_101") (pintype "passive"))
      (node (ref "J5") (pin "101") (pinfunction "B41_101") (pintype "passive"))
      (node (ref "J6") (pin "101") (pinfunction "B41_101") (pintype "passive"))
      (node (ref "J7") (pin "101") (pinfunction "B41_101") (pintype "passive"))
      (node (ref "J8") (pin "101") (pinfunction "B41_101") (pintype "passive"))
      (node (ref "J9") (pin "101") (pinfunction "B41_101") (pintype "passive"))
      (node (ref "R23") (pin "2") (pinfunction "2_2") (pintype "passive"))
      (node (ref "U5") (pin "3") (pinfunction "DO1-_3") (pintype "passive"))
    )
    (net (code "136") (name "/bus23") (class "Default")
      (node (ref "P7") (pin "25") (pinfunction "25_25") (pintype "passive"))
      (node (ref "U11") (pin "1A32") (pinfunction "V6/B1p_1A32") (pintype "passive"))
      (node (ref "U5") (pin "7") (pinfunction "DI2_7") (pintype "passive"))
    )
    (net (code "137") (name "/bus23_n") (class "Default")
      (node (ref "J1") (pin "103") (pinfunction "B43_103") (pintype "passive"))
      (node (ref "J10") (pin "103") (pinfunction "B43_103") (pintype "passive"))
      (node (ref "J11") (pin "103") (pinfunction "B43_103") (pintype "passive"))
      (node (ref "J12") (pin "103") (pinfunction "B43_103") (pintype "passive"))
      (node (ref "J13") (pin "103") (pinfunction "B43_103") (pintype "passive"))
      (node (ref "J14") (pin "103") (pinfunction "B43_103") (pintype "passive"))
      (node (ref "J15") (pin "103") (pinfunction "B43_103") (pintype "passive"))
      (node (ref "J16") (pin "103") (pinfunction "B43_103") (pintype "passive"))
      (node (ref "J2") (pin "103") (pinfunction "B43_103") (pintype "passive"))
      (node (ref "J3") (pin "103") (pinfunction "B43_103") (pintype "passive"))
      (node (ref "J4") (pin "103") (pinfunction "B43_103") (pintype "passive"))
      (node (ref "J5") (pin "103") (pinfunction "B43_103") (pintype "passive"))
      (node (ref "J6") (pin "103") (pinfunction "B43_103") (pintype "passive"))
      (node (ref "J7") (pin "103") (pinfunction "B43_103") (pintype "passive"))
      (node (ref "J8") (pin "103") (pinfunction "B43_103") (pintype "passive"))
      (node (ref "J9") (pin "103") (pinfunction "B43_103") (pintype "passive"))
      (node (ref "R24") (pin "1") (pinfunction "1_1") (pintype "passive"))
      (node (ref "U5") (pin "6") (pinfunction "DO2+_6") (pintype "passive"))
    )
    (net (code "138") (name "/bus23_p") (class "Default")
      (node (ref "J1") (pin "102") (pinfunction "B42_102") (pintype "passive"))
      (node (ref "J10") (pin "102") (pinfunction "B42_102") (pintype "passive"))
      (node (ref "J11") (pin "102") (pinfunction "B42_102") (pintype "passive"))
      (node (ref "J12") (pin "102") (pinfunction "B42_102") (pintype "passive"))
      (node (ref "J13") (pin "102") (pinfunction "B42_102") (pintype "passive"))
      (node (ref "J14") (pin "102") (pinfunction "B42_102") (pintype "passive"))
      (node (ref "J15") (pin "102") (pinfunction "B42_102") (pintype "passive"))
      (node (ref "J16") (pin "102") (pinfunction "B42_102") (pintype "passive"))
      (node (ref "J2") (pin "102") (pinfunction "B42_102") (pintype "passive"))
      (node (ref "J3") (pin "102") (pinfunction "B42_102") (pintype "passive"))
      (node (ref "J4") (pin "102") (pinfunction "B42_102") (pintype "passive"))
      (node (ref "J5") (pin "102") (pinfunction "B42_102") (pintype "passive"))
      (node (ref "J6") (pin "102") (pinfunction "B42_102") (pintype "passive"))
      (node (ref "J7") (pin "102") (pinfunction "B42_102") (pintype "passive"))
      (node (ref "J8") (pin "102") (pinfunction "B42_102") (pintype "passive"))
      (node (ref "J9") (pin "102") (pinfunction "B42_102") (pintype "passive"))
      (node (ref "R24") (pin "2") (pinfunction "2_2") (pintype "passive"))
      (node (ref "U5") (pin "5") (pinfunction "DO2-_5") (pintype "passive"))
    )
    (net (code "139") (name "/bus24") (class "Default")
      (node (ref "P7") (pin "28") (pinfunction "28_28") (pintype "passive"))
      (node (ref "U11") (pin "1A35") (pinfunction "L6/L16p_1A35") (pintype "passive"))
      (node (ref "U4") (pin "9") (pinfunction "DI3_9") (pintype "passive"))
    )
    (net (code "140") (name "/bus24_n") (class "Default")
      (node (ref "J1") (pin "95") (pinfunction "B35_95") (pintype "passive"))
      (node (ref "J10") (pin "95") (pinfunction "B35_95") (pintype "passive"))
      (node (ref "J11") (pin "95") (pinfunction "B35_95") (pintype "passive"))
      (node (ref "J12") (pin "95") (pinfunction "B35_95") (pintype "passive"))
      (node (ref "J13") (pin "95") (pinfunction "B35_95") (pintype "passive"))
      (node (ref "J14") (pin "95") (pinfunction "B35_95") (pintype "passive"))
      (node (ref "J15") (pin "95") (pinfunction "B35_95") (pintype "passive"))
      (node (ref "J16") (pin "95") (pinfunction "B35_95") (pintype "passive"))
      (node (ref "J2") (pin "95") (pinfunction "B35_95") (pintype "passive"))
      (node (ref "J3") (pin "95") (pinfunction "B35_95") (pintype "passive"))
      (node (ref "J4") (pin "95") (pinfunction "B35_95") (pintype "passive"))
      (node (ref "J5") (pin "95") (pinfunction "B35_95") (pintype "passive"))
      (node (ref "J6") (pin "95") (pinfunction "B35_95") (pintype "passive"))
      (node (ref "J7") (pin "95") (pinfunction "B35_95") (pintype "passive"))
      (node (ref "J8") (pin "95") (pinfunction "B35_95") (pintype "passive"))
      (node (ref "J9") (pin "95") (pinfunction "B35_95") (pintype "passive"))
      (node (ref "R25") (pin "1") (pinfunction "1_1") (pintype "passive"))
      (node (ref "U4") (pin "10") (pinfunction "DO3+_10") (pintype "passive"))
    )
    (net (code "141") (name "/bus24_p") (class "Default")
      (node (ref "J1") (pin "96") (pinfunction "B36_96") (pintype "passive"))
      (node (ref "J10") (pin "96") (pinfunction "B36_96") (pintype "passive"))
      (node (ref "J11") (pin "96") (pinfunction "B36_96") (pintype "passive"))
      (node (ref "J12") (pin "96") (pinfunction "B36_96") (pintype "passive"))
      (node (ref "J13") (pin "96") (pinfunction "B36_96") (pintype "passive"))
      (node (ref "J14") (pin "96") (pinfunction "B36_96") (pintype "passive"))
      (node (ref "J15") (pin "96") (pinfunction "B36_96") (pintype "passive"))
      (node (ref "J16") (pin "96") (pinfunction "B36_96") (pintype "passive"))
      (node (ref "J2") (pin "96") (pinfunction "B36_96") (pintype "passive"))
      (node (ref "J3") (pin "96") (pinfunction "B36_96") (pintype "passive"))
      (node (ref "J4") (pin "96") (pinfunction "B36_96") (pintype "passive"))
      (node (ref "J5") (pin "96") (pinfunction "B36_96") (pintype "passive"))
      (node (ref "J6") (pin "96") (pinfunction "B36_96") (pintype "passive"))
      (node (ref "J7") (pin "96") (pinfunction "B36_96") (pintype "passive"))
      (node (ref "J8") (pin "96") (pinfunction "B36_96") (pintype "passive"))
      (node (ref "J9") (pin "96") (pinfunction "B36_96") (pintype "passive"))
      (node (ref "R25") (pin "2") (pinfunction "2_2") (pintype "passive"))
      (node (ref "U4") (pin "11") (pinfunction "DO3-_11") (pintype "passive"))
    )
    (net (code "142") (name "/bus25") (class "Default")
      (node (ref "P7") (pin "27") (pinfunction "27_27") (pintype "passive"))
      (node (ref "U11") (pin "1A34") (pinfunction "V5/B1n_1A34") (pintype "passive"))
      (node (ref "U4") (pin "15") (pinfunction "DI4_15") (pintype "passive"))
    )
    (net (code "143") (name "/bus25_n") (class "Default")
      (node (ref "J1") (pin "98") (pinfunction "B38_98") (pintype "passive"))
      (node (ref "J10") (pin "98") (pinfunction "B38_98") (pintype "passive"))
      (node (ref "J11") (pin "98") (pinfunction "B38_98") (pintype "passive"))
      (node (ref "J12") (pin "98") (pinfunction "B38_98") (pintype "passive"))
      (node (ref "J13") (pin "98") (pinfunction "B38_98") (pintype "passive"))
      (node (ref "J14") (pin "98") (pinfunction "B38_98") (pintype "passive"))
      (node (ref "J15") (pin "98") (pinfunction "B38_98") (pintype "passive"))
      (node (ref "J16") (pin "98") (pinfunction "B38_98") (pintype "passive"))
      (node (ref "J2") (pin "98") (pinfunction "B38_98") (pintype "passive"))
      (node (ref "J3") (pin "98") (pinfunction "B38_98") (pintype "passive"))
      (node (ref "J4") (pin "98") (pinfunction "B38_98") (pintype "passive"))
      (node (ref "J5") (pin "98") (pinfunction "B38_98") (pintype "passive"))
      (node (ref "J6") (pin "98") (pinfunction "B38_98") (pintype "passive"))
      (node (ref "J7") (pin "98") (pinfunction "B38_98") (pintype "passive"))
      (node (ref "J8") (pin "98") (pinfunction "B38_98") (pintype "passive"))
      (node (ref "J9") (pin "98") (pinfunction "B38_98") (pintype "passive"))
      (node (ref "R26") (pin "1") (pinfunction "1_1") (pintype "passive"))
      (node (ref "U4") (pin "14") (pinfunction "DO4+_14") (pintype "passive"))
    )
    (net (code "144") (name "/bus25_p") (class "Default")
      (node (ref "J1") (pin "97") (pinfunction "B37_97") (pintype "passive"))
      (node (ref "J10") (pin "97") (pinfunction "B37_97") (pintype "passive"))
      (node (ref "J11") (pin "97") (pinfunction "B37_97") (pintype "passive"))
      (node (ref "J12") (pin "97") (pinfunction "B37_97") (pintype "passive"))
      (node (ref "J13") (pin "97") (pinfunction "B37_97") (pintype "passive"))
      (node (ref "J14") (pin "97") (pinfunction "B37_97") (pintype "passive"))
      (node (ref "J15") (pin "97") (pinfunction "B37_97") (pintype "passive"))
      (node (ref "J16") (pin "97") (pinfunction "B37_97") (pintype "passive"))
      (node (ref "J2") (pin "97") (pinfunction "B37_97") (pintype "passive"))
      (node (ref "J3") (pin "97") (pinfunction "B37_97") (pintype "passive"))
      (node (ref "J4") (pin "97") (pinfunction "B37_97") (pintype "passive"))
      (node (ref "J5") (pin "97") (pinfunction "B37_97") (pintype "passive"))
      (node (ref "J6") (pin "97") (pinfunction "B37_97") (pintype "passive"))
      (node (ref "J7") (pin "97") (pinfunction "B37_97") (pintype "passive"))
      (node (ref "J8") (pin "97") (pinfunction "B37_97") (pintype "passive"))
      (node (ref "J9") (pin "97") (pinfunction "B37_97") (pintype "passive"))
      (node (ref "R26") (pin "2") (pinfunction "2_2") (pintype "passive"))
      (node (ref "U4") (pin "13") (pinfunction "DO4-_13") (pintype "passive"))
    )
    (net (code "145") (name "/bus26") (class "Default")
      (node (ref "P7") (pin "30") (pinfunction "30_30") (pintype "passive"))
      (node (ref "U11") (pin "1B3") (pinfunction "M2/L17p_1B3") (pintype "passive"))
      (node (ref "U4") (pin "1") (pinfunction "DI1_1") (pintype "passive"))
    )
    (net (code "146") (name "/bus26_n") (class "Default")
      (node (ref "J1") (pin "91") (pinfunction "B31_91") (pintype "passive"))
      (node (ref "J10") (pin "91") (pinfunction "B31_91") (pintype "passive"))
      (node (ref "J11") (pin "91") (pinfunction "B31_91") (pintype "passive"))
      (node (ref "J12") (pin "91") (pinfunction "B31_91") (pintype "passive"))
      (node (ref "J13") (pin "91") (pinfunction "B31_91") (pintype "passive"))
      (node (ref "J14") (pin "91") (pinfunction "B31_91") (pintype "passive"))
      (node (ref "J15") (pin "91") (pinfunction "B31_91") (pintype "passive"))
      (node (ref "J16") (pin "91") (pinfunction "B31_91") (pintype "passive"))
      (node (ref "J2") (pin "91") (pinfunction "B31_91") (pintype "passive"))
      (node (ref "J3") (pin "91") (pinfunction "B31_91") (pintype "passive"))
      (node (ref "J4") (pin "91") (pinfunction "B31_91") (pintype "passive"))
      (node (ref "J5") (pin "91") (pinfunction "B31_91") (pintype "passive"))
      (node (ref "J6") (pin "91") (pinfunction "B31_91") (pintype "passive"))
      (node (ref "J7") (pin "91") (pinfunction "B31_91") (pintype "passive"))
      (node (ref "J8") (pin "91") (pinfunction "B31_91") (pintype "passive"))
      (node (ref "J9") (pin "91") (pinfunction "B31_91") (pintype "passive"))
      (node (ref "R27") (pin "1") (pinfunction "1_1") (pintype "passive"))
      (node (ref "U4") (pin "2") (pinfunction "DO1+_2") (pintype "passive"))
    )
    (net (code "147") (name "/bus26_p") (class "Default")
      (node (ref "J1") (pin "92") (pinfunction "B32_92") (pintype "passive"))
      (node (ref "J10") (pin "92") (pinfunction "B32_92") (pintype "passive"))
      (node (ref "J11") (pin "92") (pinfunction "B32_92") (pintype "passive"))
      (node (ref "J12") (pin "92") (pinfunction "B32_92") (pintype "passive"))
      (node (ref "J13") (pin "92") (pinfunction "B32_92") (pintype "passive"))
      (node (ref "J14") (pin "92") (pinfunction "B32_92") (pintype "passive"))
      (node (ref "J15") (pin "92") (pinfunction "B32_92") (pintype "passive"))
      (node (ref "J16") (pin "92") (pinfunction "B32_92") (pintype "passive"))
      (node (ref "J2") (pin "92") (pinfunction "B32_92") (pintype "passive"))
      (node (ref "J3") (pin "92") (pinfunction "B32_92") (pintype "passive"))
      (node (ref "J4") (pin "92") (pinfunction "B32_92") (pintype "passive"))
      (node (ref "J5") (pin "92") (pinfunction "B32_92") (pintype "passive"))
      (node (ref "J6") (pin "92") (pinfunction "B32_92") (pintype "passive"))
      (node (ref "J7") (pin "92") (pinfunction "B32_92") (pintype "passive"))
      (node (ref "J8") (pin "92") (pinfunction "B32_92") (pintype "passive"))
      (node (ref "J9") (pin "92") (pinfunction "B32_92") (pintype "passive"))
      (node (ref "R27") (pin "2") (pinfunction "2_2") (pintype "passive"))
      (node (ref "U4") (pin "3") (pinfunction "DO1-_3") (pintype "passive"))
    )
    (net (code "148") (name "/bus27") (class "Default")
      (node (ref "P7") (pin "29") (pinfunction "29_29") (pintype "passive"))
      (node (ref "U11") (pin "1A37") (pinfunction "M6/L16n_1A37") (pintype "passive"))
      (node (ref "U4") (pin "7") (pinfunction "DI2_7") (pintype "passive"))
    )
    (net (code "149") (name "/bus27_n") (class "Default")
      (node (ref "J1") (pin "94") (pinfunction "B34_94") (pintype "passive"))
      (node (ref "J10") (pin "94") (pinfunction "B34_94") (pintype "passive"))
      (node (ref "J11") (pin "94") (pinfunction "B34_94") (pintype "passive"))
      (node (ref "J12") (pin "94") (pinfunction "B34_94") (pintype "passive"))
      (node (ref "J13") (pin "94") (pinfunction "B34_94") (pintype "passive"))
      (node (ref "J14") (pin "94") (pinfunction "B34_94") (pintype "passive"))
      (node (ref "J15") (pin "94") (pinfunction "B34_94") (pintype "passive"))
      (node (ref "J16") (pin "94") (pinfunction "B34_94") (pintype "passive"))
      (node (ref "J2") (pin "94") (pinfunction "B34_94") (pintype "passive"))
      (node (ref "J3") (pin "94") (pinfunction "B34_94") (pintype "passive"))
      (node (ref "J4") (pin "94") (pinfunction "B34_94") (pintype "passive"))
      (node (ref "J5") (pin "94") (pinfunction "B34_94") (pintype "passive"))
      (node (ref "J6") (pin "94") (pinfunction "B34_94") (pintype "passive"))
      (node (ref "J7") (pin "94") (pinfunction "B34_94") (pintype "passive"))
      (node (ref "J8") (pin "94") (pinfunction "B34_94") (pintype "passive"))
      (node (ref "J9") (pin "94") (pinfunction "B34_94") (pintype "passive"))
      (node (ref "R28") (pin "1") (pinfunction "1_1") (pintype "passive"))
      (node (ref "U4") (pin "6") (pinfunction "DO2+_6") (pintype "passive"))
    )
    (net (code "150") (name "/bus27_p") (class "Default")
      (node (ref "J1") (pin "93") (pinfunction "B33_93") (pintype "passive"))
      (node (ref "J10") (pin "93") (pinfunction "B33_93") (pintype "passive"))
      (node (ref "J11") (pin "93") (pinfunction "B33_93") (pintype "passive"))
      (node (ref "J12") (pin "93") (pinfunction "B33_93") (pintype "passive"))
      (node (ref "J13") (pin "93") (pinfunction "B33_93") (pintype "passive"))
      (node (ref "J14") (pin "93") (pinfunction "B33_93") (pintype "passive"))
      (node (ref "J15") (pin "93") (pinfunction "B33_93") (pintype "passive"))
      (node (ref "J16") (pin "93") (pinfunction "B33_93") (pintype "passive"))
      (node (ref "J2") (pin "93") (pinfunction "B33_93") (pintype "passive"))
      (node (ref "J3") (pin "93") (pinfunction "B33_93") (pintype "passive"))
      (node (ref "J4") (pin "93") (pinfunction "B33_93") (pintype "passive"))
      (node (ref "J5") (pin "93") (pinfunction "B33_93") (pintype "passive"))
      (node (ref "J6") (pin "93") (pinfunction "B33_93") (pintype "passive"))
      (node (ref "J7") (pin "93") (pinfunction "B33_93") (pintype "passive"))
      (node (ref "J8") (pin "93") (pinfunction "B33_93") (pintype "passive"))
      (node (ref "J9") (pin "93") (pinfunction "B33_93") (pintype "passive"))
      (node (ref "R28") (pin "2") (pinfunction "2_2") (pintype "passive"))
      (node (ref "U4") (pin "5") (pinfunction "DO2-_5") (pintype "passive"))
    )
    (net (code "151") (name "/bus28") (class "Default")
      (node (ref "P7") (pin "31") (pinfunction "31_31") (pintype "passive"))
      (node (ref "U11") (pin "1B5") (pinfunction "M1/L17n_1B5") (pintype "passive"))
      (node (ref "U3") (pin "9") (pinfunction "DI3_9") (pintype "passive"))
    )
    (net (code "152") (name "/bus28_n") (class "Default")
      (node (ref "J1") (pin "86") (pinfunction "B26_86") (pintype "passive"))
      (node (ref "J10") (pin "86") (pinfunction "B26_86") (pintype "passive"))
      (node (ref "J11") (pin "86") (pinfunction "B26_86") (pintype "passive"))
      (node (ref "J12") (pin "86") (pinfunction "B26_86") (pintype "passive"))
      (node (ref "J13") (pin "86") (pinfunction "B26_86") (pintype "passive"))
      (node (ref "J14") (pin "86") (pinfunction "B26_86") (pintype "passive"))
      (node (ref "J15") (pin "86") (pinfunction "B26_86") (pintype "passive"))
      (node (ref "J16") (pin "86") (pinfunction "B26_86") (pintype "passive"))
      (node (ref "J2") (pin "86") (pinfunction "B26_86") (pintype "passive"))
      (node (ref "J3") (pin "86") (pinfunction "B26_86") (pintype "passive"))
      (node (ref "J4") (pin "86") (pinfunction "B26_86") (pintype "passive"))
      (node (ref "J5") (pin "86") (pinfunction "B26_86") (pintype "passive"))
      (node (ref "J6") (pin "86") (pinfunction "B26_86") (pintype "passive"))
      (node (ref "J7") (pin "86") (pinfunction "B26_86") (pintype "passive"))
      (node (ref "J8") (pin "86") (pinfunction "B26_86") (pintype "passive"))
      (node (ref "J9") (pin "86") (pinfunction "B26_86") (pintype "passive"))
      (node (ref "R29") (pin "1") (pinfunction "1_1") (pintype "passive"))
      (node (ref "U3") (pin "10") (pinfunction "DO3+_10") (pintype "passive"))
    )
    (net (code "153") (name "/bus28_p") (class "Default")
      (node (ref "J1") (pin "87") (pinfunction "B27_87") (pintype "passive"))
      (node (ref "J10") (pin "87") (pinfunction "B27_87") (pintype "passive"))
      (node (ref "J11") (pin "87") (pinfunction "B27_87") (pintype "passive"))
      (node (ref "J12") (pin "87") (pinfunction "B27_87") (pintype "passive"))
      (node (ref "J13") (pin "87") (pinfunction "B27_87") (pintype "passive"))
      (node (ref "J14") (pin "87") (pinfunction "B27_87") (pintype "passive"))
      (node (ref "J15") (pin "87") (pinfunction "B27_87") (pintype "passive"))
      (node (ref "J16") (pin "87") (pinfunction "B27_87") (pintype "passive"))
      (node (ref "J2") (pin "87") (pinfunction "B27_87") (pintype "passive"))
      (node (ref "J3") (pin "87") (pinfunction "B27_87") (pintype "passive"))
      (node (ref "J4") (pin "87") (pinfunction "B27_87") (pintype "passive"))
      (node (ref "J5") (pin "87") (pinfunction "B27_87") (pintype "passive"))
      (node (ref "J6") (pin "87") (pinfunction "B27_87") (pintype "passive"))
      (node (ref "J7") (pin "87") (pinfunction "B27_87") (pintype "passive"))
      (node (ref "J8") (pin "87") (pinfunction "B27_87") (pintype "passive"))
      (node (ref "J9") (pin "87") (pinfunction "B27_87") (pintype "passive"))
      (node (ref "R29") (pin "2") (pinfunction "2_2") (pintype "passive"))
      (node (ref "U3") (pin "11") (pinfunction "DO3-_11") (pintype "passive"))
    )
    (net (code "154") (name "/bus29") (class "Default")
      (node (ref "P7") (pin "32") (pinfunction "32_32") (pintype "passive"))
      (node (ref "U11") (pin "1B4") (pinfunction "U7/B2p_1B4") (pintype "passive"))
      (node (ref "U3") (pin "15") (pinfunction "DI4_15") (pintype "passive"))
    )
    (net (code "155") (name "/bus29_n") (class "Default")
      (node (ref "J1") (pin "89") (pinfunction "B29_89") (pintype "passive"))
      (node (ref "J10") (pin "89") (pinfunction "B29_89") (pintype "passive"))
      (node (ref "J11") (pin "89") (pinfunction "B29_89") (pintype "passive"))
      (node (ref "J12") (pin "89") (pinfunction "B29_89") (pintype "passive"))
      (node (ref "J13") (pin "89") (pinfunction "B29_89") (pintype "passive"))
      (node (ref "J14") (pin "89") (pinfunction "B29_89") (pintype "passive"))
      (node (ref "J15") (pin "89") (pinfunction "B29_89") (pintype "passive"))
      (node (ref "J16") (pin "89") (pinfunction "B29_89") (pintype "passive"))
      (node (ref "J2") (pin "89") (pinfunction "B29_89") (pintype "passive"))
      (node (ref "J3") (pin "89") (pinfunction "B29_89") (pintype "passive"))
      (node (ref "J4") (pin "89") (pinfunction "B29_89") (pintype "passive"))
      (node (ref "J5") (pin "89") (pinfunction "B29_89") (pintype "passive"))
      (node (ref "J6") (pin "89") (pinfunction "B29_89") (pintype "passive"))
      (node (ref "J7") (pin "89") (pinfunction "B29_89") (pintype "passive"))
      (node (ref "J8") (pin "89") (pinfunction "B29_89") (pintype "passive"))
      (node (ref "J9") (pin "89") (pinfunction "B29_89") (pintype "passive"))
      (node (ref "R30") (pin "1") (pinfunction "1_1") (pintype "passive"))
      (node (ref "U3") (pin "14") (pinfunction "DO4+_14") (pintype "passive"))
    )
    (net (code "156") (name "/bus29_p") (class "Default")
      (node (ref "J1") (pin "88") (pinfunction "B28_88") (pintype "passive"))
      (node (ref "J10") (pin "88") (pinfunction "B28_88") (pintype "passive"))
      (node (ref "J11") (pin "88") (pinfunction "B28_88") (pintype "passive"))
      (node (ref "J12") (pin "88") (pinfunction "B28_88") (pintype "passive"))
      (node (ref "J13") (pin "88") (pinfunction "B28_88") (pintype "passive"))
      (node (ref "J14") (pin "88") (pinfunction "B28_88") (pintype "passive"))
      (node (ref "J15") (pin "88") (pinfunction "B28_88") (pintype "passive"))
      (node (ref "J16") (pin "88") (pinfunction "B28_88") (pintype "passive"))
      (node (ref "J2") (pin "88") (pinfunction "B28_88") (pintype "passive"))
      (node (ref "J3") (pin "88") (pinfunction "B28_88") (pintype "passive"))
      (node (ref "J4") (pin "88") (pinfunction "B28_88") (pintype "passive"))
      (node (ref "J5") (pin "88") (pinfunction "B28_88") (pintype "passive"))
      (node (ref "J6") (pin "88") (pinfunction "B28_88") (pintype "passive"))
      (node (ref "J7") (pin "88") (pinfunction "B28_88") (pintype "passive"))
      (node (ref "J8") (pin "88") (pinfunction "B28_88") (pintype "passive"))
      (node (ref "J9") (pin "88") (pinfunction "B28_88") (pintype "passive"))
      (node (ref "R30") (pin "2") (pinfunction "2_2") (pintype "passive"))
      (node (ref "U3") (pin "13") (pinfunction "DO4-_13") (pintype "passive"))
    )
    (net (code "157") (name "/bus30") (class "Default")
      (node (ref "P7") (pin "34") (pinfunction "34_34") (pintype "passive"))
      (node (ref "U11") (pin "1B7") (pinfunction "M4/L18p_1B7") (pintype "passive"))
      (node (ref "U3") (pin "1") (pinfunction "DI1_1") (pintype "passive"))
    )
    (net (code "158") (name "/bus30_n") (class "Default")
      (node (ref "J1") (pin "82") (pinfunction "B22_82") (pintype "passive"))
      (node (ref "J10") (pin "82") (pinfunction "B22_82") (pintype "passive"))
      (node (ref "J11") (pin "82") (pinfunction "B22_82") (pintype "passive"))
      (node (ref "J12") (pin "82") (pinfunction "B22_82") (pintype "passive"))
      (node (ref "J13") (pin "82") (pinfunction "B22_82") (pintype "passive"))
      (node (ref "J14") (pin "82") (pinfunction "B22_82") (pintype "passive"))
      (node (ref "J15") (pin "82") (pinfunction "B22_82") (pintype "passive"))
      (node (ref "J16") (pin "82") (pinfunction "B22_82") (pintype "passive"))
      (node (ref "J2") (pin "82") (pinfunction "B22_82") (pintype "passive"))
      (node (ref "J3") (pin "82") (pinfunction "B22_82") (pintype "passive"))
      (node (ref "J4") (pin "82") (pinfunction "B22_82") (pintype "passive"))
      (node (ref "J5") (pin "82") (pinfunction "B22_82") (pintype "passive"))
      (node (ref "J6") (pin "82") (pinfunction "B22_82") (pintype "passive"))
      (node (ref "J7") (pin "82") (pinfunction "B22_82") (pintype "passive"))
      (node (ref "J8") (pin "82") (pinfunction "B22_82") (pintype "passive"))
      (node (ref "J9") (pin "82") (pinfunction "B22_82") (pintype "passive"))
      (node (ref "R31") (pin "1") (pinfunction "1_1") (pintype "passive"))
      (node (ref "U3") (pin "2") (pinfunction "DO1+_2") (pintype "passive"))
    )
    (net (code "159") (name "/bus30_p") (class "Default")
      (node (ref "J1") (pin "83") (pinfunction "B23_83") (pintype "passive"))
      (node (ref "J10") (pin "83") (pinfunction "B23_83") (pintype "passive"))
      (node (ref "J11") (pin "83") (pinfunction "B23_83") (pintype "passive"))
      (node (ref "J12") (pin "83") (pinfunction "B23_83") (pintype "passive"))
      (node (ref "J13") (pin "83") (pinfunction "B23_83") (pintype "passive"))
      (node (ref "J14") (pin "83") (pinfunction "B23_83") (pintype "passive"))
      (node (ref "J15") (pin "83") (pinfunction "B23_83") (pintype "passive"))
      (node (ref "J16") (pin "83") (pinfunction "B23_83") (pintype "passive"))
      (node (ref "J2") (pin "83") (pinfunction "B23_83") (pintype "passive"))
      (node (ref "J3") (pin "83") (pinfunction "B23_83") (pintype "passive"))
      (node (ref "J4") (pin "83") (pinfunction "B23_83") (pintype "passive"))
      (node (ref "J5") (pin "83") (pinfunction "B23_83") (pintype "passive"))
      (node (ref "J6") (pin "83") (pinfunction "B23_83") (pintype "passive"))
      (node (ref "J7") (pin "83") (pinfunction "B23_83") (pintype "passive"))
      (node (ref "J8") (pin "83") (pinfunction "B23_83") (pintype "passive"))
      (node (ref "J9") (pin "83") (pinfunction "B23_83") (pintype "passive"))
      (node (ref "R31") (pin "2") (pinfunction "2_2") (pintype "passive"))
      (node (ref "U3") (pin "3") (pinfunction "DO1-_3") (pintype "passive"))
    )
    (net (code "160") (name "/bus31") (class "Default")
      (node (ref "P7") (pin "33") (pinfunction "33_33") (pintype "passive"))
      (node (ref "U11") (pin "1B6") (pinfunction "U8/B2n_1B6") (pintype "passive"))
      (node (ref "U3") (pin "7") (pinfunction "DI2_7") (pintype "passive"))
    )
    (net (code "161") (name "/bus31_n") (class "Default")
      (node (ref "J1") (pin "85") (pinfunction "B25_85") (pintype "passive"))
      (node (ref "J10") (pin "85") (pinfunction "B25_85") (pintype "passive"))
      (node (ref "J11") (pin "85") (pinfunction "B25_85") (pintype "passive"))
      (node (ref "J12") (pin "85") (pinfunction "B25_85") (pintype "passive"))
      (node (ref "J13") (pin "85") (pinfunction "B25_85") (pintype "passive"))
      (node (ref "J14") (pin "85") (pinfunction "B25_85") (pintype "passive"))
      (node (ref "J15") (pin "85") (pinfunction "B25_85") (pintype "passive"))
      (node (ref "J16") (pin "85") (pinfunction "B25_85") (pintype "passive"))
      (node (ref "J2") (pin "85") (pinfunction "B25_85") (pintype "passive"))
      (node (ref "J3") (pin "85") (pinfunction "B25_85") (pintype "passive"))
      (node (ref "J4") (pin "85") (pinfunction "B25_85") (pintype "passive"))
      (node (ref "J5") (pin "85") (pinfunction "B25_85") (pintype "passive"))
      (node (ref "J6") (pin "85") (pinfunction "B25_85") (pintype "passive"))
      (node (ref "J7") (pin "85") (pinfunction "B25_85") (pintype "passive"))
      (node (ref "J8") (pin "85") (pinfunction "B25_85") (pintype "passive"))
      (node (ref "J9") (pin "85") (pinfunction "B25_85") (pintype "passive"))
      (node (ref "R32") (pin "1") (pinfunction "1_1") (pintype "passive"))
      (node (ref "U3") (pin "6") (pinfunction "DO2+_6") (pintype "passive"))
    )
    (net (code "162") (name "/bus31_p") (class "Default")
      (node (ref "J1") (pin "84") (pinfunction "B24_84") (pintype "passive"))
      (node (ref "J10") (pin "84") (pinfunction "B24_84") (pintype "passive"))
      (node (ref "J11") (pin "84") (pinfunction "B24_84") (pintype "passive"))
      (node (ref "J12") (pin "84") (pinfunction "B24_84") (pintype "passive"))
      (node (ref "J13") (pin "84") (pinfunction "B24_84") (pintype "passive"))
      (node (ref "J14") (pin "84") (pinfunction "B24_84") (pintype "passive"))
      (node (ref "J15") (pin "84") (pinfunction "B24_84") (pintype "passive"))
      (node (ref "J16") (pin "84") (pinfunction "B24_84") (pintype "passive"))
      (node (ref "J2") (pin "84") (pinfunction "B24_84") (pintype "passive"))
      (node (ref "J3") (pin "84") (pinfunction "B24_84") (pintype "passive"))
      (node (ref "J4") (pin "84") (pinfunction "B24_84") (pintype "passive"))
      (node (ref "J5") (pin "84") (pinfunction "B24_84") (pintype "passive"))
      (node (ref "J6") (pin "84") (pinfunction "B24_84") (pintype "passive"))
      (node (ref "J7") (pin "84") (pinfunction "B24_84") (pintype "passive"))
      (node (ref "J8") (pin "84") (pinfunction "B24_84") (pintype "passive"))
      (node (ref "J9") (pin "84") (pinfunction "B24_84") (pintype "passive"))
      (node (ref "R32") (pin "2") (pinfunction "2_2") (pintype "passive"))
      (node (ref "U3") (pin "5") (pinfunction "DO2-_5") (pintype "passive"))
    )
    (net (code "163") (name "/bus32") (class "Default")
      (node (ref "P9") (pin "6") (pinfunction "6_6") (pintype "passive"))
      (node (ref "U11") (pin "1B13") (pinfunction "N1/L19n_1B13") (pintype "passive"))
      (node (ref "U2") (pin "11") (pinfunction "YD_11") (pintype "passive"))
    )
    (net (code "164") (name "/bus32_n") (class "Default")
      (node (ref "J1") (pin "15") (pinfunction "A15_15") (pintype "passive"))
      (node (ref "J10") (pin "15") (pinfunction "A15_15") (pintype "passive"))
      (node (ref "J11") (pin "15") (pinfunction "A15_15") (pintype "passive"))
      (node (ref "J12") (pin "15") (pinfunction "A15_15") (pintype "passive"))
      (node (ref "J13") (pin "15") (pinfunction "A15_15") (pintype "passive"))
      (node (ref "J14") (pin "15") (pinfunction "A15_15") (pintype "passive"))
      (node (ref "J15") (pin "15") (pinfunction "A15_15") (pintype "passive"))
      (node (ref "J16") (pin "15") (pinfunction "A15_15") (pintype "passive"))
      (node (ref "J2") (pin "15") (pinfunction "A15_15") (pintype "passive"))
      (node (ref "J3") (pin "15") (pinfunction "A15_15") (pintype "passive"))
      (node (ref "J4") (pin "15") (pinfunction "A15_15") (pintype "passive"))
      (node (ref "J5") (pin "15") (pinfunction "A15_15") (pintype "passive"))
      (node (ref "J6") (pin "15") (pinfunction "A15_15") (pintype "passive"))
      (node (ref "J7") (pin "15") (pinfunction "A15_15") (pintype "passive"))
      (node (ref "J8") (pin "15") (pinfunction "A15_15") (pintype "passive"))
      (node (ref "J9") (pin "15") (pinfunction "A15_15") (pintype "passive"))
      (node (ref "R33") (pin "1") (pinfunction "1_1") (pintype "passive"))
      (node (ref "U2") (pin "10") (pinfunction "D+_10") (pintype "passive"))
    )
    (net (code "165") (name "/bus32_p") (class "Default")
      (node (ref "J1") (pin "16") (pinfunction "A16_16") (pintype "passive"))
      (node (ref "J10") (pin "16") (pinfunction "A16_16") (pintype "passive"))
      (node (ref "J11") (pin "16") (pinfunction "A16_16") (pintype "passive"))
      (node (ref "J12") (pin "16") (pinfunction "A16_16") (pintype "passive"))
      (node (ref "J13") (pin "16") (pinfunction "A16_16") (pintype "passive"))
      (node (ref "J14") (pin "16") (pinfunction "A16_16") (pintype "passive"))
      (node (ref "J15") (pin "16") (pinfunction "A16_16") (pintype "passive"))
      (node (ref "J16") (pin "16") (pinfunction "A16_16") (pintype "passive"))
      (node (ref "J2") (pin "16") (pinfunction "A16_16") (pintype "passive"))
      (node (ref "J3") (pin "16") (pinfunction "A16_16") (pintype "passive"))
      (node (ref "J4") (pin "16") (pinfunction "A16_16") (pintype "passive"))
      (node (ref "J5") (pin "16") (pinfunction "A16_16") (pintype "passive"))
      (node (ref "J6") (pin "16") (pinfunction "A16_16") (pintype "passive"))
      (node (ref "J7") (pin "16") (pinfunction "A16_16") (pintype "passive"))
      (node (ref "J8") (pin "16") (pinfunction "A16_16") (pintype "passive"))
      (node (ref "J9") (pin "16") (pinfunction "A16_16") (pintype "passive"))
      (node (ref "R33") (pin "2") (pinfunction "2_2") (pintype "passive"))
      (node (ref "U2") (pin "9") (pinfunction "D-_9") (pintype "passive"))
    )
    (net (code "166") (name "/bus33") (class "Default")
      (node (ref "P9") (pin "5") (pinfunction "5_5") (pintype "passive"))
      (node (ref "U11") (pin "1B12") (pinfunction "AA5/B5p_1B12") (pintype "passive"))
      (node (ref "U2") (pin "13") (pinfunction "YB_13") (pintype "passive"))
    )
    (net (code "167") (name "/bus33_n") (class "Default")
      (node (ref "J1") (pin "14") (pinfunction "A14_14") (pintype "passive"))
      (node (ref "J10") (pin "14") (pinfunction "A14_14") (pintype "passive"))
      (node (ref "J11") (pin "14") (pinfunction "A14_14") (pintype "passive"))
      (node (ref "J12") (pin "14") (pinfunction "A14_14") (pintype "passive"))
      (node (ref "J13") (pin "14") (pinfunction "A14_14") (pintype "passive"))
      (node (ref "J14") (pin "14") (pinfunction "A14_14") (pintype "passive"))
      (node (ref "J15") (pin "14") (pinfunction "A14_14") (pintype "passive"))
      (node (ref "J16") (pin "14") (pinfunction "A14_14") (pintype "passive"))
      (node (ref "J2") (pin "14") (pinfunction "A14_14") (pintype "passive"))
      (node (ref "J3") (pin "14") (pinfunction "A14_14") (pintype "passive"))
      (node (ref "J4") (pin "14") (pinfunction "A14_14") (pintype "passive"))
      (node (ref "J5") (pin "14") (pinfunction "A14_14") (pintype "passive"))
      (node (ref "J6") (pin "14") (pinfunction "A14_14") (pintype "passive"))
      (node (ref "J7") (pin "14") (pinfunction "A14_14") (pintype "passive"))
      (node (ref "J8") (pin "14") (pinfunction "A14_14") (pintype "passive"))
      (node (ref "J9") (pin "14") (pinfunction "A14_14") (pintype "passive"))
      (node (ref "R34") (pin "1") (pinfunction "1_1") (pintype "passive"))
      (node (ref "U2") (pin "14") (pinfunction "B+_14") (pintype "passive"))
    )
    (net (code "168") (name "/bus33_p") (class "Default")
      (node (ref "J1") (pin "13") (pinfunction "A13_13") (pintype "passive"))
      (node (ref "J10") (pin "13") (pinfunction "A13_13") (pintype "passive"))
      (node (ref "J11") (pin "13") (pinfunction "A13_13") (pintype "passive"))
      (node (ref "J12") (pin "13") (pinfunction "A13_13") (pintype "passive"))
      (node (ref "J13") (pin "13") (pinfunction "A13_13") (pintype "passive"))
      (node (ref "J14") (pin "13") (pinfunction "A13_13") (pintype "passive"))
      (node (ref "J15") (pin "13") (pinfunction "A13_13") (pintype "passive"))
      (node (ref "J16") (pin "13") (pinfunction "A13_13") (pintype "passive"))
      (node (ref "J2") (pin "13") (pinfunction "A13_13") (pintype "passive"))
      (node (ref "J3") (pin "13") (pinfunction "A13_13") (pintype "passive"))
      (node (ref "J4") (pin "13") (pinfunction "A13_13") (pintype "passive"))
      (node (ref "J5") (pin "13") (pinfunction "A13_13") (pintype "passive"))
      (node (ref "J6") (pin "13") (pinfunction "A13_13") (pintype "passive"))
      (node (ref "J7") (pin "13") (pinfunction "A13_13") (pintype "passive"))
      (node (ref "J8") (pin "13") (pinfunction "A13_13") (pintype "passive"))
      (node (ref "J9") (pin "13") (pinfunction "A13_13") (pintype "passive"))
      (node (ref "R34") (pin "2") (pinfunction "2_2") (pintype "passive"))
      (node (ref "U2") (pin "15") (pinfunction "B-_15") (pintype "passive"))
    )
    (net (code "169") (name "/bus34") (class "Default")
      (node (ref "P9") (pin "8") (pinfunction "8_8") (pintype "passive"))
      (node (ref "U11") (pin "1B15") (pinfunction "P2/L20p_1B15") (pintype "passive"))
      (node (ref "U2") (pin "3") (pinfunction "YA_3") (pintype "passive"))
    )
    (net (code "170") (name "/bus34_n") (class "Default")
      (node (ref "J1") (pin "19") (pinfunction "A19_19") (pintype "passive"))
      (node (ref "J10") (pin "19") (pinfunction "A19_19") (pintype "passive"))
      (node (ref "J11") (pin "19") (pinfunction "A19_19") (pintype "passive"))
      (node (ref "J12") (pin "19") (pinfunction "A19_19") (pintype "passive"))
      (node (ref "J13") (pin "19") (pinfunction "A19_19") (pintype "passive"))
      (node (ref "J14") (pin "19") (pinfunction "A19_19") (pintype "passive"))
      (node (ref "J15") (pin "19") (pinfunction "A19_19") (pintype "passive"))
      (node (ref "J16") (pin "19") (pinfunction "A19_19") (pintype "passive"))
      (node (ref "J2") (pin "19") (pinfunction "A19_19") (pintype "passive"))
      (node (ref "J3") (pin "19") (pinfunction "A19_19") (pintype "passive"))
      (node (ref "J4") (pin "19") (pinfunction "A19_19") (pintype "passive"))
      (node (ref "J5") (pin "19") (pinfunction "A19_19") (pintype "passive"))
      (node (ref "J6") (pin "19") (pinfunction "A19_19") (pintype "passive"))
      (node (ref "J7") (pin "19") (pinfunction "A19_19") (pintype "passive"))
      (node (ref "J8") (pin "19") (pinfunction "A19_19") (pintype "passive"))
      (node (ref "J9") (pin "19") (pinfunction "A19_19") (pintype "passive"))
      (node (ref "R35") (pin "1") (pinfunction "1_1") (pintype "passive"))
      (node (ref "U2") (pin "2") (pinfunction "A+_2") (pintype "passive"))
    )
    (net (code "171") (name "/bus34_p") (class "Default")
      (node (ref "J1") (pin "20") (pinfunction "A20_20") (pintype "passive"))
      (node (ref "J10") (pin "20") (pinfunction "A20_20") (pintype "passive"))
      (node (ref "J11") (pin "20") (pinfunction "A20_20") (pintype "passive"))
      (node (ref "J12") (pin "20") (pinfunction "A20_20") (pintype "passive"))
      (node (ref "J13") (pin "20") (pinfunction "A20_20") (pintype "passive"))
      (node (ref "J14") (pin "20") (pinfunction "A20_20") (pintype "passive"))
      (node (ref "J15") (pin "20") (pinfunction "A20_20") (pintype "passive"))
      (node (ref "J16") (pin "20") (pinfunction "A20_20") (pintype "passive"))
      (node (ref "J2") (pin "20") (pinfunction "A20_20") (pintype "passive"))
      (node (ref "J3") (pin "20") (pinfunction "A20_20") (pintype "passive"))
      (node (ref "J4") (pin "20") (pinfunction "A20_20") (pintype "passive"))
      (node (ref "J5") (pin "20") (pinfunction "A20_20") (pintype "passive"))
      (node (ref "J6") (pin "20") (pinfunction "A20_20") (pintype "passive"))
      (node (ref "J7") (pin "20") (pinfunction "A20_20") (pintype "passive"))
      (node (ref "J8") (pin "20") (pinfunction "A20_20") (pintype "passive"))
      (node (ref "J9") (pin "20") (pinfunction "A20_20") (pintype "passive"))
      (node (ref "R35") (pin "2") (pinfunction "2_2") (pintype "passive"))
      (node (ref "U2") (pin "1") (pinfunction "A-_1") (pintype "passive"))
    )
    (net (code "172") (name "/bus35") (class "Default")
      (node (ref "P9") (pin "7") (pinfunction "7_7") (pintype "passive"))
      (node (ref "U11") (pin "1B14") (pinfunction "AA6/B5n_1B14") (pintype "passive"))
      (node (ref "U2") (pin "5") (pinfunction "YC_5") (pintype "passive"))
    )
    (net (code "173") (name "/bus35_n") (class "Default")
      (node (ref "J1") (pin "18") (pinfunction "A18_18") (pintype "passive"))
      (node (ref "J10") (pin "18") (pinfunction "A18_18") (pintype "passive"))
      (node (ref "J11") (pin "18") (pinfunction "A18_18") (pintype "passive"))
      (node (ref "J12") (pin "18") (pinfunction "A18_18") (pintype "passive"))
      (node (ref "J13") (pin "18") (pinfunction "A18_18") (pintype "passive"))
      (node (ref "J14") (pin "18") (pinfunction "A18_18") (pintype "passive"))
      (node (ref "J15") (pin "18") (pinfunction "A18_18") (pintype "passive"))
      (node (ref "J16") (pin "18") (pinfunction "A18_18") (pintype "passive"))
      (node (ref "J2") (pin "18") (pinfunction "A18_18") (pintype "passive"))
      (node (ref "J3") (pin "18") (pinfunction "A18_18") (pintype "passive"))
      (node (ref "J4") (pin "18") (pinfunction "A18_18") (pintype "passive"))
      (node (ref "J5") (pin "18") (pinfunction "A18_18") (pintype "passive"))
      (node (ref "J6") (pin "18") (pinfunction "A18_18") (pintype "passive"))
      (node (ref "J7") (pin "18") (pinfunction "A18_18") (pintype "passive"))
      (node (ref "J8") (pin "18") (pinfunction "A18_18") (pintype "passive"))
      (node (ref "J9") (pin "18") (pinfunction "A18_18") (pintype "passive"))
      (node (ref "R36") (pin "1") (pinfunction "1_1") (pintype "passive"))
      (node (ref "U2") (pin "6") (pinfunction "C+_6") (pintype "passive"))
    )
    (net (code "174") (name "/bus35_p") (class "Default")
      (node (ref "J1") (pin "17") (pinfunction "A17_17") (pintype "passive"))
      (node (ref "J10") (pin "17") (pinfunction "A17_17") (pintype "passive"))
      (node (ref "J11") (pin "17") (pinfunction "A17_17") (pintype "passive"))
      (node (ref "J12") (pin "17") (pinfunction "A17_17") (pintype "passive"))
      (node (ref "J13") (pin "17") (pinfunction "A17_17") (pintype "passive"))
      (node (ref "J14") (pin "17") (pinfunction "A17_17") (pintype "passive"))
      (node (ref "J15") (pin "17") (pinfunction "A17_17") (pintype "passive"))
      (node (ref "J16") (pin "17") (pinfunction "A17_17") (pintype "passive"))
      (node (ref "J2") (pin "17") (pinfunction "A17_17") (pintype "passive"))
      (node (ref "J3") (pin "17") (pinfunction "A17_17") (pintype "passive"))
      (node (ref "J4") (pin "17") (pinfunction "A17_17") (pintype "passive"))
      (node (ref "J5") (pin "17") (pinfunction "A17_17") (pintype "passive"))
      (node (ref "J6") (pin "17") (pinfunction "A17_17") (pintype "passive"))
      (node (ref "J7") (pin "17") (pinfunction "A17_17") (pintype "passive"))
      (node (ref "J8") (pin "17") (pinfunction "A17_17") (pintype "passive"))
      (node (ref "J9") (pin "17") (pinfunction "A17_17") (pintype "passive"))
      (node (ref "R36") (pin "2") (pinfunction "2_2") (pintype "passive"))
      (node (ref "U2") (pin "7") (pinfunction "C-_7") (pintype "passive"))
    )
    (net (code "175") (name "/bus36") (class "Default")
      (node (ref "P9") (pin "2") (pinfunction "2_2") (pintype "passive"))
      (node (ref "U1") (pin "11") (pinfunction "YD_11") (pintype "passive"))
      (node (ref "U11") (pin "1B9") (pinfunction "M3/L18n_1B9") (pintype "passive"))
    )
    (net (code "176") (name "/bus36_n") (class "Default")
      (node (ref "J1") (pin "78") (pinfunction "B18_78") (pintype "passive"))
      (node (ref "J10") (pin "78") (pinfunction "B18_78") (pintype "passive"))
      (node (ref "J11") (pin "78") (pinfunction "B18_78") (pintype "passive"))
      (node (ref "J12") (pin "78") (pinfunction "B18_78") (pintype "passive"))
      (node (ref "J13") (pin "78") (pinfunction "B18_78") (pintype "passive"))
      (node (ref "J14") (pin "78") (pinfunction "B18_78") (pintype "passive"))
      (node (ref "J15") (pin "78") (pinfunction "B18_78") (pintype "passive"))
      (node (ref "J16") (pin "78") (pinfunction "B18_78") (pintype "passive"))
      (node (ref "J2") (pin "78") (pinfunction "B18_78") (pintype "passive"))
      (node (ref "J3") (pin "78") (pinfunction "B18_78") (pintype "passive"))
      (node (ref "J4") (pin "78") (pinfunction "B18_78") (pintype "passive"))
      (node (ref "J5") (pin "78") (pinfunction "B18_78") (pintype "passive"))
      (node (ref "J6") (pin "78") (pinfunction "B18_78") (pintype "passive"))
      (node (ref "J7") (pin "78") (pinfunction "B18_78") (pintype "passive"))
      (node (ref "J8") (pin "78") (pinfunction "B18_78") (pintype "passive"))
      (node (ref "J9") (pin "78") (pinfunction "B18_78") (pintype "passive"))
      (node (ref "R37") (pin "1") (pinfunction "1_1") (pintype "passive"))
      (node (ref "U1") (pin "10") (pinfunction "D+_10") (pintype "passive"))
    )
    (net (code "177") (name "/bus36_p") (class "Default")
      (node (ref "J1") (pin "77") (pinfunction "B17_77") (pintype "passive"))
      (node (ref "J10") (pin "77") (pinfunction "B17_77") (pintype "passive"))
      (node (ref "J11") (pin "77") (pinfunction "B17_77") (pintype "passive"))
      (node (ref "J12") (pin "77") (pinfunction "B17_77") (pintype "passive"))
      (node (ref "J13") (pin "77") (pinfunction "B17_77") (pintype "passive"))
      (node (ref "J14") (pin "77") (pinfunction "B17_77") (pintype "passive"))
      (node (ref "J15") (pin "77") (pinfunction "B17_77") (pintype "passive"))
      (node (ref "J16") (pin "77") (pinfunction "B17_77") (pintype "passive"))
      (node (ref "J2") (pin "77") (pinfunction "B17_77") (pintype "passive"))
      (node (ref "J3") (pin "77") (pinfunction "B17_77") (pintype "passive"))
      (node (ref "J4") (pin "77") (pinfunction "B17_77") (pintype "passive"))
      (node (ref "J5") (pin "77") (pinfunction "B17_77") (pintype "passive"))
      (node (ref "J6") (pin "77") (pinfunction "B17_77") (pintype "passive"))
      (node (ref "J7") (pin "77") (pinfunction "B17_77") (pintype "passive"))
      (node (ref "J8") (pin "77") (pinfunction "B17_77") (pintype "passive"))
      (node (ref "J9") (pin "77") (pinfunction "B17_77") (pintype "passive"))
      (node (ref "R37") (pin "2") (pinfunction "2_2") (pintype "passive"))
      (node (ref "U1") (pin "9") (pinfunction "D-_9") (pintype "passive"))
    )
    (net (code "178") (name "/bus37") (class "Default")
      (node (ref "P9") (pin "1") (pinfunction "1_1") (pintype "passive"))
      (node (ref "U1") (pin "13") (pinfunction "YB_13") (pintype "passive"))
      (node (ref "U11") (pin "1B8") (pinfunction "W6/B4p_1B8") (pintype "passive"))
    )
    (net (code "179") (name "/bus37_n") (class "Default")
      (node (ref "J1") (pin "79") (pinfunction "B19_79") (pintype "passive"))
      (node (ref "J10") (pin "79") (pinfunction "B19_79") (pintype "passive"))
      (node (ref "J11") (pin "79") (pinfunction "B19_79") (pintype "passive"))
      (node (ref "J12") (pin "79") (pinfunction "B19_79") (pintype "passive"))
      (node (ref "J13") (pin "79") (pinfunction "B19_79") (pintype "passive"))
      (node (ref "J14") (pin "79") (pinfunction "B19_79") (pintype "passive"))
      (node (ref "J15") (pin "79") (pinfunction "B19_79") (pintype "passive"))
      (node (ref "J16") (pin "79") (pinfunction "B19_79") (pintype "passive"))
      (node (ref "J2") (pin "79") (pinfunction "B19_79") (pintype "passive"))
      (node (ref "J3") (pin "79") (pinfunction "B19_79") (pintype "passive"))
      (node (ref "J4") (pin "79") (pinfunction "B19_79") (pintype "passive"))
      (node (ref "J5") (pin "79") (pinfunction "B19_79") (pintype "passive"))
      (node (ref "J6") (pin "79") (pinfunction "B19_79") (pintype "passive"))
      (node (ref "J7") (pin "79") (pinfunction "B19_79") (pintype "passive"))
      (node (ref "J8") (pin "79") (pinfunction "B19_79") (pintype "passive"))
      (node (ref "J9") (pin "79") (pinfunction "B19_79") (pintype "passive"))
      (node (ref "R38") (pin "1") (pinfunction "1_1") (pintype "passive"))
      (node (ref "U1") (pin "14") (pinfunction "B+_14") (pintype "passive"))
    )
    (net (code "180") (name "/bus37_p") (class "Default")
      (node (ref "J1") (pin "80") (pinfunction "B20_80") (pintype "passive"))
      (node (ref "J10") (pin "80") (pinfunction "B20_80") (pintype "passive"))
      (node (ref "J11") (pin "80") (pinfunction "B20_80") (pintype "passive"))
      (node (ref "J12") (pin "80") (pinfunction "B20_80") (pintype "passive"))
      (node (ref "J13") (pin "80") (pinfunction "B20_80") (pintype "passive"))
      (node (ref "J14") (pin "80") (pinfunction "B20_80") (pintype "passive"))
      (node (ref "J15") (pin "80") (pinfunction "B20_80") (pintype "passive"))
      (node (ref "J16") (pin "80") (pinfunction "B20_80") (pintype "passive"))
      (node (ref "J2") (pin "80") (pinfunction "B20_80") (pintype "passive"))
      (node (ref "J3") (pin "80") (pinfunction "B20_80") (pintype "passive"))
      (node (ref "J4") (pin "80") (pinfunction "B20_80") (pintype "passive"))
      (node (ref "J5") (pin "80") (pinfunction "B20_80") (pintype "passive"))
      (node (ref "J6") (pin "80") (pinfunction "B20_80") (pintype "passive"))
      (node (ref "J7") (pin "80") (pinfunction "B20_80") (pintype "passive"))
      (node (ref "J8") (pin "80") (pinfunction "B20_80") (pintype "passive"))
      (node (ref "J9") (pin "80") (pinfunction "B20_80") (pintype "passive"))
      (node (ref "R38") (pin "2") (pinfunction "2_2") (pintype "passive"))
      (node (ref "U1") (pin "15") (pinfunction "B-_15") (pintype "passive"))
    )
    (net (code "181") (name "/bus38") (class "Default")
      (node (ref "P9") (pin "4") (pinfunction "4_4") (pintype "passive"))
      (node (ref "U1") (pin "3") (pinfunction "YA_3") (pintype "passive"))
      (node (ref "U11") (pin "1B11") (pinfunction "N2/L19p_1B11") (pintype "passive"))
    )
    (net (code "182") (name "/bus38_n") (class "Default")
      (node (ref "J1") (pin "74") (pinfunction "B14_74") (pintype "passive"))
      (node (ref "J10") (pin "74") (pinfunction "B14_74") (pintype "passive"))
      (node (ref "J11") (pin "74") (pinfunction "B14_74") (pintype "passive"))
      (node (ref "J12") (pin "74") (pinfunction "B14_74") (pintype "passive"))
      (node (ref "J13") (pin "74") (pinfunction "B14_74") (pintype "passive"))
      (node (ref "J14") (pin "74") (pinfunction "B14_74") (pintype "passive"))
      (node (ref "J15") (pin "74") (pinfunction "B14_74") (pintype "passive"))
      (node (ref "J16") (pin "74") (pinfunction "B14_74") (pintype "passive"))
      (node (ref "J2") (pin "74") (pinfunction "B14_74") (pintype "passive"))
      (node (ref "J3") (pin "74") (pinfunction "B14_74") (pintype "passive"))
      (node (ref "J4") (pin "74") (pinfunction "B14_74") (pintype "passive"))
      (node (ref "J5") (pin "74") (pinfunction "B14_74") (pintype "passive"))
      (node (ref "J6") (pin "74") (pinfunction "B14_74") (pintype "passive"))
      (node (ref "J7") (pin "74") (pinfunction "B14_74") (pintype "passive"))
      (node (ref "J8") (pin "74") (pinfunction "B14_74") (pintype "passive"))
      (node (ref "J9") (pin "74") (pinfunction "B14_74") (pintype "passive"))
      (node (ref "R39") (pin "1") (pinfunction "1_1") (pintype "passive"))
      (node (ref "U1") (pin "2") (pinfunction "A+_2") (pintype "passive"))
    )
    (net (code "183") (name "/bus38_p") (class "Default")
      (node (ref "J1") (pin "73") (pinfunction "B13_73") (pintype "passive"))
      (node (ref "J10") (pin "73") (pinfunction "B13_73") (pintype "passive"))
      (node (ref "J11") (pin "73") (pinfunction "B13_73") (pintype "passive"))
      (node (ref "J12") (pin "73") (pinfunction "B13_73") (pintype "passive"))
      (node (ref "J13") (pin "73") (pinfunction "B13_73") (pintype "passive"))
      (node (ref "J14") (pin "73") (pinfunction "B13_73") (pintype "passive"))
      (node (ref "J15") (pin "73") (pinfunction "B13_73") (pintype "passive"))
      (node (ref "J16") (pin "73") (pinfunction "B13_73") (pintype "passive"))
      (node (ref "J2") (pin "73") (pinfunction "B13_73") (pintype "passive"))
      (node (ref "J3") (pin "73") (pinfunction "B13_73") (pintype "passive"))
      (node (ref "J4") (pin "73") (pinfunction "B13_73") (pintype "passive"))
      (node (ref "J5") (pin "73") (pinfunction "B13_73") (pintype "passive"))
      (node (ref "J6") (pin "73") (pinfunction "B13_73") (pintype "passive"))
      (node (ref "J7") (pin "73") (pinfunction "B13_73") (pintype "passive"))
      (node (ref "J8") (pin "73") (pinfunction "B13_73") (pintype "passive"))
      (node (ref "J9") (pin "73") (pinfunction "B13_73") (pintype "passive"))
      (node (ref "R39") (pin "2") (pinfunction "2_2") (pintype "passive"))
      (node (ref "U1") (pin "1") (pinfunction "A-_1") (pintype "passive"))
    )
    (net (code "184") (name "/bus39") (class "Default")
      (node (ref "P9") (pin "3") (pinfunction "3_3") (pintype "passive"))
      (node (ref "U1") (pin "5") (pinfunction "YC_5") (pintype "passive"))
      (node (ref "U11") (pin "1B10") (pinfunction "V7/B4n_1B10") (pintype "passive"))
    )
    (net (code "185") (name "/bus39_n") (class "Default")
      (node (ref "J1") (pin "75") (pinfunction "B15_75") (pintype "passive"))
      (node (ref "J10") (pin "75") (pinfunction "B15_75") (pintype "passive"))
      (node (ref "J11") (pin "75") (pinfunction "B15_75") (pintype "passive"))
      (node (ref "J12") (pin "75") (pinfunction "B15_75") (pintype "passive"))
      (node (ref "J13") (pin "75") (pinfunction "B15_75") (pintype "passive"))
      (node (ref "J14") (pin "75") (pinfunction "B15_75") (pintype "passive"))
      (node (ref "J15") (pin "75") (pinfunction "B15_75") (pintype "passive"))
      (node (ref "J16") (pin "75") (pinfunction "B15_75") (pintype "passive"))
      (node (ref "J2") (pin "75") (pinfunction "B15_75") (pintype "passive"))
      (node (ref "J3") (pin "75") (pinfunction "B15_75") (pintype "passive"))
      (node (ref "J4") (pin "75") (pinfunction "B15_75") (pintype "passive"))
      (node (ref "J5") (pin "75") (pinfunction "B15_75") (pintype "passive"))
      (node (ref "J6") (pin "75") (pinfunction "B15_75") (pintype "passive"))
      (node (ref "J7") (pin "75") (pinfunction "B15_75") (pintype "passive"))
      (node (ref "J8") (pin "75") (pinfunction "B15_75") (pintype "passive"))
      (node (ref "J9") (pin "75") (pinfunction "B15_75") (pintype "passive"))
      (node (ref "R40") (pin "1") (pinfunction "1_1") (pintype "passive"))
      (node (ref "U1") (pin "6") (pinfunction "C+_6") (pintype "passive"))
    )
    (net (code "186") (name "/bus39_p") (class "Default")
      (node (ref "J1") (pin "76") (pinfunction "B16_76") (pintype "passive"))
      (node (ref "J10") (pin "76") (pinfunction "B16_76") (pintype "passive"))
      (node (ref "J11") (pin "76") (pinfunction "B16_76") (pintype "passive"))
      (node (ref "J12") (pin "76") (pinfunction "B16_76") (pintype "passive"))
      (node (ref "J13") (pin "76") (pinfunction "B16_76") (pintype "passive"))
      (node (ref "J14") (pin "76") (pinfunction "B16_76") (pintype "passive"))
      (node (ref "J15") (pin "76") (pinfunction "B16_76") (pintype "passive"))
      (node (ref "J16") (pin "76") (pinfunction "B16_76") (pintype "passive"))
      (node (ref "J2") (pin "76") (pinfunction "B16_76") (pintype "passive"))
      (node (ref "J3") (pin "76") (pinfunction "B16_76") (pintype "passive"))
      (node (ref "J4") (pin "76") (pinfunction "B16_76") (pintype "passive"))
      (node (ref "J5") (pin "76") (pinfunction "B16_76") (pintype "passive"))
      (node (ref "J6") (pin "76") (pinfunction "B16_76") (pintype "passive"))
      (node (ref "J7") (pin "76") (pinfunction "B16_76") (pintype "passive"))
      (node (ref "J8") (pin "76") (pinfunction "B16_76") (pintype "passive"))
      (node (ref "J9") (pin "76") (pinfunction "B16_76") (pintype "passive"))
      (node (ref "R40") (pin "2") (pinfunction "2_2") (pintype "passive"))
      (node (ref "U1") (pin "7") (pinfunction "C-_7") (pintype "passive"))
    )
    (net (code "187") (name "3.3V_dig") (class "Default")
      (node (ref "C1") (pin "1") (pinfunction "1_1") (pintype "passive"))
      (node (ref "C2") (pin "1") (pinfunction "1_1") (pintype "passive"))
      (node (ref "C39") (pin "1") (pinfunction "1_1") (pintype "passive"))
      (node (ref "C40") (pin "1") (pinfunction "1_1") (pintype "passive"))
      (node (ref "C41") (pin "1") (pinfunction "1_1") (pintype "passive"))
      (node (ref "C42") (pin "1") (pinfunction "1_1") (pintype "passive"))
      (node (ref "C43") (pin "1") (pinfunction "1_1") (pintype "passive"))
      (node (ref "C44") (pin "1") (pinfunction "1_1") (pintype "passive"))
      (node (ref "C45") (pin "1") (pinfunction "1_1") (pintype "passive"))
      (node (ref "C46") (pin "1") (pinfunction "1_1") (pintype "passive"))
      (node (ref "C47") (pin "2") (pinfunction "2_2") (pintype "passive"))
      (node (ref "C48") (pin "2") (pinfunction "2_2") (pintype "passive"))
      (node (ref "C49") (pin "2") (pinfunction "2_2") (pintype "passive"))
      (node (ref "C50") (pin "2") (pinfunction "2_2") (pintype "passive"))
      (node (ref "U1") (pin "12") (pinfunction "ENBD_12") (pintype "passive"))
      (node (ref "U1") (pin "16") (pinfunction "Vcc_16") (pintype "passive"))
      (node (ref "U1") (pin "4") (pinfunction "EAC_4") (pintype "passive"))
      (node (ref "U10") (pin "16") (pinfunction "Vcc_16") (pintype "passive"))
      (node (ref "U10") (pin "4") (pinfunction "EN_4") (pintype "passive"))
      (node (ref "U11") (pin "1A1") (pinfunction "3.3V_1A1") (pintype "passive"))
      (node (ref "U11") (pin "1C1") (pinfunction "3.3V_1C1") (pintype "passive"))
      (node (ref "U12") (pin "1") (pinfunction "VCCA_1") (pintype "passive"))
      (node (ref "U12") (pin "5") (pinfunction "DIR_5") (pintype "passive"))
      (node (ref "U12") (pin "6") (pinfunction "VCCB_6") (pintype "passive"))
      (node (ref "U13") (pin "1") (pinfunction "VCCA_1") (pintype "passive"))
      (node (ref "U13") (pin "5") (pinfunction "DIR_5") (pintype "passive"))
      (node (ref "U13") (pin "6") (pinfunction "VCCB_6") (pintype "passive"))
      (node (ref "U14") (pin "1") (pinfunction "VCCA_1") (pintype "passive"))
      (node (ref "U14") (pin "5") (pinfunction "DIR_5") (pintype "passive"))
      (node (ref "U14") (pin "6") (pinfunction "VCCB_6") (pintype "passive"))
      (node (ref "U15") (pin "1") (pinfunction "VCCA_1") (pintype "passive"))
      (node (ref "U15") (pin "5") (pinfunction "DIR_5") (pintype "passive"))
      (node (ref "U15") (pin "6") (pinfunction "VCCB_6") (pintype "passive"))
      (node (ref "U2") (pin "12") (pinfunction "ENBD_12") (pintype "passive"))
      (node (ref "U2") (pin "16") (pinfunction "Vcc_16") (pintype "passive"))
      (node (ref "U2") (pin "4") (pinfunction "EAC_4") (pintype "passive"))
      (node (ref "U3") (pin "16") (pinfunction "Vcc_16") (pintype "passive"))
      (node (ref "U3") (pin "4") (pinfunction "EN_4") (pintype "passive"))
      (node (ref "U4") (pin "16") (pinfunction "Vcc_16") (pintype "passive"))
      (node (ref "U4") (pin "4") (pinfunction "EN_4") (pintype "passive"))
      (node (ref "U5") (pin "16") (pinfunction "Vcc_16") (pintype "passive"))
      (node (ref "U5") (pin "4") (pinfunction "EN_4") (pintype "passive"))
      (node (ref "U6") (pin "16") (pinfunction "Vcc_16") (pintype "passive"))
      (node (ref "U6") (pin "4") (pinfunction "EN_4") (pintype "passive"))
      (node (ref "U7") (pin "16") (pinfunction "Vcc_16") (pintype "passive"))
      (node (ref "U7") (pin "4") (pinfunction "EN_4") (pintype "passive"))
      (node (ref "U8") (pin "16") (pinfunction "Vcc_16") (pintype "passive"))
      (node (ref "U8") (pin "4") (pinfunction "EN_4") (pintype "passive"))
      (node (ref "U9") (pin "16") (pinfunction "Vcc_16") (pintype "passive"))
      (node (ref "U9") (pin "4") (pinfunction "EN_4") (pintype "passive"))
    )
    (net (code "188") (name "5V_ANA_BUS") (class "Default")
      (node (ref "C16") (pin "1") (pinfunction "1_1") (pintype "passive"))
      (node (ref "C18") (pin "1") (pinfunction "1_1") (pintype "passive"))
      (node (ref "C20") (pin "1") (pinfunction "1_1") (pintype "passive"))
      (node (ref "C22") (pin "1") (pinfunction "1_1") (pintype "passive"))
      (node (ref "C25") (pin "2") (pinfunction "2_2") (pintype "passive"))
      (node (ref "C26") (pin "2") (pinfunction "2_2") (pintype "passive"))
      (node (ref "C29") (pin "2") (pinfunction "2_2") (pintype "passive"))
      (node (ref "C30") (pin "2") (pinfunction "2_2") (pintype "passive"))
      (node (ref "C33") (pin "2") (pinfunction "2_2") (pintype "passive"))
      (node (ref "C34") (pin "2") (pinfunction "2_2") (pintype "passive"))
      (node (ref "C37") (pin "2") (pinfunction "2_2") (pintype "passive"))
      (node (ref "C38") (pin "2") (pinfunction "2_2") (pintype "passive"))
      (node (ref "J1") (pin "118") (pinfunction "B58_118") (pintype "passive"))
      (node (ref "J1") (pin "58") (pinfunction "A58_58") (pintype "passive"))
      (node (ref "J10") (pin "118") (pinfunction "B58_118") (pintype "passive"))
      (node (ref "J10") (pin "58") (pinfunction "A58_58") (pintype "passive"))
      (node (ref "J11") (pin "118") (pinfunction "B58_118") (pintype "passive"))
      (node (ref "J11") (pin "58") (pinfunction "A58_58") (pintype "passive"))
      (node (ref "J12") (pin "118") (pinfunction "B58_118") (pintype "passive"))
      (node (ref "J12") (pin "58") (pinfunction "A58_58") (pintype "passive"))
      (node (ref "J13") (pin "118") (pinfunction "B58_118") (pintype "passive"))
      (node (ref "J13") (pin "58") (pinfunction "A58_58") (pintype "passive"))
      (node (ref "J14") (pin "118") (pinfunction "B58_118") (pintype "passive"))
      (node (ref "J14") (pin "58") (pinfunction "A58_58") (pintype "passive"))
      (node (ref "J15") (pin "118") (pinfunction "B58_118") (pintype "passive"))
      (node (ref "J15") (pin "58") (pinfunction "A58_58") (pintype "passive"))
      (node (ref "J16") (pin "118") (pinfunction "B58_118") (pintype "passive"))
      (node (ref "J16") (pin "58") (pinfunction "A58_58") (pintype "passive"))
      (node (ref "J2") (pin "118") (pinfunction "B58_118") (pintype "passive"))
      (node (ref "J2") (pin "58") (pinfunction "A58_58") (pintype "passive"))
      (node (ref "J3") (pin "118") (pinfunction "B58_118") (pintype "passive"))
      (node (ref "J3") (pin "58") (pinfunction "A58_58") (pintype "passive"))
      (node (ref "J4") (pin "118") (pinfunction "B58_118") (pintype "passive"))
      (node (ref "J4") (pin "58") (pinfunction "A58_58") (pintype "passive"))
      (node (ref "J5") (pin "118") (pinfunction "B58_118") (pintype "passive"))
      (node (ref "J5") (pin "58") (pinfunction "A58_58") (pintype "passive"))
      (node (ref "J6") (pin "118") (pinfunction "B58_118") (pintype "passive"))
      (node (ref "J6") (pin "58") (pinfunction "A58_58") (pintype "passive"))
      (node (ref "J7") (pin "118") (pinfunction "B58_118") (pintype "passive"))
      (node (ref "J7") (pin "58") (pinfunction "A58_58") (pintype "passive"))
      (node (ref "J8") (pin "118") (pinfunction "B58_118") (pintype "passive"))
      (node (ref "J8") (pin "58") (pinfunction "A58_58") (pintype "passive"))
      (node (ref "J9") (pin "118") (pinfunction "B58_118") (pintype "passive"))
      (node (ref "J9") (pin "58") (pinfunction "A58_58") (pintype "passive"))
    )
    (net (code "189") (name "5V_DIG_BUS") (class "Default")
      (node (ref "C10") (pin "2") (pinfunction "2_2") (pintype "passive"))
      (node (ref "C11") (pin "2") (pinfunction "2_2") (pintype "passive"))
      (node (ref "C12") (pin "2") (pinfunction "2_2") (pintype "passive"))
      (node (ref "C13") (pin "2") (pinfunction "2_2") (pintype "passive"))
      (node (ref "C14") (pin "2") (pinfunction "2_2") (pintype "passive"))
      (node (ref "C3") (pin "1") (pinfunction "1_1") (pintype "passive"))
      (node (ref "C4") (pin "1") (pinfunction "1_1") (pintype "passive"))
      (node (ref "C5") (pin "1") (pinfunction "1_1") (pintype "passive"))
      (node (ref "C6") (pin "1") (pinfunction "1_1") (pintype "passive"))
      (node (ref "C7") (pin "2") (pinfunction "2_2") (pintype "passive"))
      (node (ref "C8") (pin "2") (pinfunction "2_2") (pintype "passive"))
      (node (ref "C9") (pin "2") (pinfunction "2_2") (pintype "passive"))
      (node (ref "J1") (pin "1") (pinfunction "A1_1") (pintype "passive"))
      (node (ref "J1") (pin "61") (pinfunction "B1_61") (pintype "passive"))
      (node (ref "J10") (pin "1") (pinfunction "A1_1") (pintype "passive"))
      (node (ref "J10") (pin "61") (pinfunction "B1_61") (pintype "passive"))
      (node (ref "J11") (pin "1") (pinfunction "A1_1") (pintype "passive"))
      (node (ref "J11") (pin "61") (pinfunction "B1_61") (pintype "passive"))
      (node (ref "J12") (pin "1") (pinfunction "A1_1") (pintype "passive"))
      (node (ref "J12") (pin "61") (pinfunction "B1_61") (pintype "passive"))
      (node (ref "J13") (pin "1") (pinfunction "A1_1") (pintype "passive"))
      (node (ref "J13") (pin "61") (pinfunction "B1_61") (pintype "passive"))
      (node (ref "J14") (pin "1") (pinfunction "A1_1") (pintype "passive"))
      (node (ref "J14") (pin "61") (pinfunction "B1_61") (pintype "passive"))
      (node (ref "J15") (pin "1") (pinfunction "A1_1") (pintype "passive"))
      (node (ref "J15") (pin "61") (pinfunction "B1_61") (pintype "passive"))
      (node (ref "J16") (pin "1") (pinfunction "A1_1") (pintype "passive"))
      (node (ref "J16") (pin "61") (pinfunction "B1_61") (pintype "passive"))
      (node (ref "J2") (pin "1") (pinfunction "A1_1") (pintype "passive"))
      (node (ref "J2") (pin "61") (pinfunction "B1_61") (pintype "passive"))
      (node (ref "J3") (pin "1") (pinfunction "A1_1") (pintype "passive"))
      (node (ref "J3") (pin "61") (pinfunction "B1_61") (pintype "passive"))
      (node (ref "J4") (pin "1") (pinfunction "A1_1") (pintype "passive"))
      (node (ref "J4") (pin "61") (pinfunction "B1_61") (pintype "passive"))
      (node (ref "J5") (pin "1") (pinfunction "A1_1") (pintype "passive"))
      (node (ref "J5") (pin "61") (pinfunction "B1_61") (pintype "passive"))
      (node (ref "J6") (pin "1") (pinfunction "A1_1") (pintype "passive"))
      (node (ref "J6") (pin "61") (pinfunction "B1_61") (pintype "passive"))
      (node (ref "J7") (pin "1") (pinfunction "A1_1") (pintype "passive"))
      (node (ref "J7") (pin "61") (pinfunction "B1_61") (pintype "passive"))
      (node (ref "J8") (pin "1") (pinfunction "A1_1") (pintype "passive"))
      (node (ref "J8") (pin "61") (pinfunction "B1_61") (pintype "passive"))
      (node (ref "J9") (pin "1") (pinfunction "A1_1") (pintype "passive"))
      (node (ref "J9") (pin "61") (pinfunction "B1_61") (pintype "passive"))
    )
    (net (code "190") (name "8V_BUS") (class "Default")
      (node (ref "C15") (pin "1") (pinfunction "1_1") (pintype "passive"))
      (node (ref "C17") (pin "1") (pinfunction "1_1") (pintype "passive"))
      (node (ref "C19") (pin "1") (pinfunction "1_1") (pintype "passive"))
      (node (ref "C21") (pin "1") (pinfunction "1_1") (pintype "passive"))
      (node (ref "C23") (pin "2") (pinfunction "2_2") (pintype "passive"))
      (node (ref "C24") (pin "2") (pinfunction "2_2") (pintype "passive"))
      (node (ref "C27") (pin "2") (pinfunction "2_2") (pintype "passive"))
      (node (ref "C28") (pin "2") (pinfunction "2_2") (pintype "passive"))
      (node (ref "C31") (pin "2") (pinfunction "2_2") (pintype "passive"))
      (node (ref "C32") (pin "2") (pinfunction "2_2") (pintype "passive"))
      (node (ref "C35") (pin "2") (pinfunction "2_2") (pintype "passive"))
      (node (ref "C36") (pin "2") (pinfunction "2_2") (pintype "passive"))
      (node (ref "J1") (pin "120") (pinfunction "B60_120") (pintype "passive"))
      (node (ref "J1") (pin "60") (pinfunction "A60_60") (pintype "passive"))
      (node (ref "J10") (pin "120") (pinfunction "B60_120") (pintype "passive"))
      (node (ref "J10") (pin "60") (pinfunction "A60_60") (pintype "passive"))
      (node (ref "J11") (pin "120") (pinfunction "B60_120") (pintype "passive"))
      (node (ref "J11") (pin "60") (pinfunction "A60_60") (pintype "passive"))
      (node (ref "J12") (pin "120") (pinfunction "B60_120") (pintype "passive"))
      (node (ref "J12") (pin "60") (pinfunction "A60_60") (pintype "passive"))
      (node (ref "J13") (pin "120") (pinfunction "B60_120") (pintype "passive"))
      (node (ref "J13") (pin "60") (pinfunction "A60_60") (pintype "passive"))
      (node (ref "J14") (pin "120") (pinfunction "B60_120") (pintype "passive"))
      (node (ref "J14") (pin "60") (pinfunction "A60_60") (pintype "passive"))
      (node (ref "J15") (pin "120") (pinfunction "B60_120") (pintype "passive"))
      (node (ref "J15") (pin "60") (pinfunction "A60_60") (pintype "passive"))
      (node (ref "J16") (pin "120") (pinfunction "B60_120") (pintype "passive"))
      (node (ref "J16") (pin "60") (pinfunction "A60_60") (pintype "passive"))
      (node (ref "J2") (pin "120") (pinfunction "B60_120") (pintype "passive"))
      (node (ref "J2") (pin "60") (pinfunction "A60_60") (pintype "passive"))
      (node (ref "J3") (pin "120") (pinfunction "B60_120") (pintype "passive"))
      (node (ref "J3") (pin "60") (pinfunction "A60_60") (pintype "passive"))
      (node (ref "J4") (pin "120") (pinfunction "B60_120") (pintype "passive"))
      (node (ref "J4") (pin "60") (pinfunction "A60_60") (pintype "passive"))
      (node (ref "J5") (pin "120") (pinfunction "B60_120") (pintype "passive"))
      (node (ref "J5") (pin "60") (pinfunction "A60_60") (pintype "passive"))
      (node (ref "J6") (pin "120") (pinfunction "B60_120") (pintype "passive"))
      (node (ref "J6") (pin "60") (pinfunction "A60_60") (pintype "passive"))
      (node (ref "J7") (pin "120") (pinfunction "B60_120") (pintype "passive"))
      (node (ref "J7") (pin "60") (pinfunction "A60_60") (pintype "passive"))
      (node (ref "J8") (pin "120") (pinfunction "B60_120") (pintype "passive"))
      (node (ref "J8") (pin "60") (pinfunction "A60_60") (pintype "passive"))
      (node (ref "J9") (pin "120") (pinfunction "B60_120") (pintype "passive"))
      (node (ref "J9") (pin "60") (pinfunction "A60_60") (pintype "passive"))
    )
    (net (code "191") (name "AGND") (class "Default")
      (node (ref "C15") (pin "2") (pinfunction "2_2") (pintype "passive"))
      (node (ref "C16") (pin "2") (pinfunction "2_2") (pintype "passive"))
      (node (ref "C17") (pin "2") (pinfunction "2_2") (pintype "passive"))
      (node (ref "C18") (pin "2") (pinfunction "2_2") (pintype "passive"))
      (node (ref "C19") (pin "2") (pinfunction "2_2") (pintype "passive"))
      (node (ref "C20") (pin "2") (pinfunction "2_2") (pintype "passive"))
      (node (ref "C21") (pin "2") (pinfunction "2_2") (pintype "passive"))
      (node (ref "C22") (pin "2") (pinfunction "2_2") (pintype "passive"))
      (node (ref "C23") (pin "1") (pinfunction "1_1") (pintype "passive"))
      (node (ref "C24") (pin "1") (pinfunction "1_1") (pintype "passive"))
      (node (ref "C25") (pin "1") (pinfunction "1_1") (pintype "passive"))
      (node (ref "C26") (pin "1") (pinfunction "1_1") (pintype "passive"))
      (node (ref "C27") (pin "1") (pinfunction "1_1") (pintype "passive"))
      (node (ref "C28") (pin "1") (pinfunction "1_1") (pintype "passive"))
      (node (ref "C29") (pin "1") (pinfunction "1_1") (pintype "passive"))
      (node (ref "C30") (pin "1") (pinfunction "1_1") (pintype "passive"))
      (node (ref "C31") (pin "1") (pinfunction "1_1") (pintype "passive"))
      (node (ref "C32") (pin "1") (pinfunction "1_1") (pintype "passive"))
      (node (ref "C33") (pin "1") (pinfunction "1_1") (pintype "passive"))
      (node (ref "C34") (pin "1") (pinfunction "1_1") (pintype "passive"))
      (node (ref "C35") (pin "1") (pinfunction "1_1") (pintype "passive"))
      (node (ref "C36") (pin "1") (pinfunction "1_1") (pintype "passive"))
      (node (ref "C37") (pin "1") (pinfunction "1_1") (pintype "passive"))
      (node (ref "C38") (pin "1") (pinfunction "1_1") (pintype "passive"))
      (node (ref "J1") (pin "117") (pinfunction "B57_117") (pintype "passive"))
      (node (ref "J1") (pin "119") (pinfunction "B59_119") (pintype "passive"))
      (node (ref "J1") (pin "57") (pinfunction "A57_57") (pintype "passive"))
      (node (ref "J1") (pin "59") (pinfunction "A59_59") (pintype "passive"))
      (node (ref "J10") (pin "117") (pinfunction "B57_117") (pintype "passive"))
      (node (ref "J10") (pin "119") (pinfunction "B59_119") (pintype "passive"))
      (node (ref "J10") (pin "57") (pinfunction "A57_57") (pintype "passive"))
      (node (ref "J10") (pin "59") (pinfunction "A59_59") (pintype "passive"))
      (node (ref "J11") (pin "117") (pinfunction "B57_117") (pintype "passive"))
      (node (ref "J11") (pin "119") (pinfunction "B59_119") (pintype "passive"))
      (node (ref "J11") (pin "57") (pinfunction "A57_57") (pintype "passive"))
      (node (ref "J11") (pin "59") (pinfunction "A59_59") (pintype "passive"))
      (node (ref "J12") (pin "117") (pinfunction "B57_117") (pintype "passive"))
      (node (ref "J12") (pin "119") (pinfunction "B59_119") (pintype "passive"))
      (node (ref "J12") (pin "57") (pinfunction "A57_57") (pintype "passive"))
      (node (ref "J12") (pin "59") (pinfunction "A59_59") (pintype "passive"))
      (node (ref "J13") (pin "117") (pinfunction "B57_117") (pintype "passive"))
      (node (ref "J13") (pin "119") (pinfunction "B59_119") (pintype "passive"))
      (node (ref "J13") (pin "57") (pinfunction "A57_57") (pintype "passive"))
      (node (ref "J13") (pin "59") (pinfunction "A59_59") (pintype "passive"))
      (node (ref "J14") (pin "117") (pinfunction "B57_117") (pintype "passive"))
      (node (ref "J14") (pin "119") (pinfunction "B59_119") (pintype "passive"))
      (node (ref "J14") (pin "57") (pinfunction "A57_57") (pintype "passive"))
      (node (ref "J14") (pin "59") (pinfunction "A59_59") (pintype "passive"))
      (node (ref "J15") (pin "117") (pinfunction "B57_117") (pintype "passive"))
      (node (ref "J15") (pin "119") (pinfunction "B59_119") (pintype "passive"))
      (node (ref "J15") (pin "57") (pinfunction "A57_57") (pintype "passive"))
      (node (ref "J15") (pin "59") (pinfunction "A59_59") (pintype "passive"))
      (node (ref "J16") (pin "117") (pinfunction "B57_117") (pintype "passive"))
      (node (ref "J16") (pin "119") (pinfunction "B59_119") (pintype "passive"))
      (node (ref "J16") (pin "57") (pinfunction "A57_57") (pintype "passive"))
      (node (ref "J16") (pin "59") (pinfunction "A59_59") (pintype "passive"))
      (node (ref "J2") (pin "117") (pinfunction "B57_117") (pintype "passive"))
      (node (ref "J2") (pin "119") (pinfunction "B59_119") (pintype "passive"))
      (node (ref "J2") (pin "57") (pinfunction "A57_57") (pintype "passive"))
      (node (ref "J2") (pin "59") (pinfunction "A59_59") (pintype "passive"))
      (node (ref "J3") (pin "117") (pinfunction "B57_117") (pintype "passive"))
      (node (ref "J3") (pin "119") (pinfunction "B59_119") (pintype "passive"))
      (node (ref "J3") (pin "57") (pinfunction "A57_57") (pintype "passive"))
      (node (ref "J3") (pin "59") (pinfunction "A59_59") (pintype "passive"))
      (node (ref "J4") (pin "117") (pinfunction "B57_117") (pintype "passive"))
      (node (ref "J4") (pin "119") (pinfunction "B59_119") (pintype "passive"))
      (node (ref "J4") (pin "57") (pinfunction "A57_57") (pintype "passive"))
      (node (ref "J4") (pin "59") (pinfunction "A59_59") (pintype "passive"))
      (node (ref "J5") (pin "117") (pinfunction "B57_117") (pintype "passive"))
      (node (ref "J5") (pin "119") (pinfunction "B59_119") (pintype "passive"))
      (node (ref "J5") (pin "57") (pinfunction "A57_57") (pintype "passive"))
      (node (ref "J5") (pin "59") (pinfunction "A59_59") (pintype "passive"))
      (node (ref "J6") (pin "117") (pinfunction "B57_117") (pintype "passive"))
      (node (ref "J6") (pin "119") (pinfunction "B59_119") (pintype "passive"))
      (node (ref "J6") (pin "57") (pinfunction "A57_57") (pintype "passive"))
      (node (ref "J6") (pin "59") (pinfunction "A59_59") (pintype "passive"))
      (node (ref "J7") (pin "117") (pinfunction "B57_117") (pintype "passive"))
      (node (ref "J7") (pin "119") (pinfunction "B59_119") (pintype "passive"))
      (node (ref "J7") (pin "57") (pinfunction "A57_57") (pintype "passive"))
      (node (ref "J7") (pin "59") (pinfunction "A59_59") (pintype "passive"))
      (node (ref "J8") (pin "117") (pinfunction "B57_117") (pintype "passive"))
      (node (ref "J8") (pin "119") (pinfunction "B59_119") (pintype "passive"))
      (node (ref "J8") (pin "57") (pinfunction "A57_57") (pintype "passive"))
      (node (ref "J8") (pin "59") (pinfunction "A59_59") (pintype "passive"))
      (node (ref "J9") (pin "117") (pinfunction "B57_117") (pintype "passive"))
      (node (ref "J9") (pin "119") (pinfunction "B59_119") (pintype "passive"))
      (node (ref "J9") (pin "57") (pinfunction "A57_57") (pintype "passive"))
      (node (ref "J9") (pin "59") (pinfunction "A59_59") (pintype "passive"))
    )
    (net (code "192") (name "DGND") (class "Default")
      (node (ref "C1") (pin "2") (pinfunction "2_2") (pintype "passive"))
      (node (ref "C10") (pin "1") (pinfunction "1_1") (pintype "passive"))
      (node (ref "C11") (pin "1") (pinfunction "1_1") (pintype "passive"))
      (node (ref "C12") (pin "1") (pinfunction "1_1") (pintype "passive"))
      (node (ref "C13") (pin "1") (pinfunction "1_1") (pintype "passive"))
      (node (ref "C14") (pin "1") (pinfunction "1_1") (pintype "passive"))
      (node (ref "C2") (pin "2") (pinfunction "2_2") (pintype "passive"))
      (node (ref "C3") (pin "2") (pinfunction "2_2") (pintype "passive"))
      (node (ref "C39") (pin "2") (pinfunction "2_2") (pintype "passive"))
      (node (ref "C4") (pin "2") (pinfunction "2_2") (pintype "passive"))
      (node (ref "C40") (pin "2") (pinfunction "2_2") (pintype "passive"))
      (node (ref "C41") (pin "2") (pinfunction "2_2") (pintype "passive"))
      (node (ref "C42") (pin "2") (pinfunction "2_2") (pintype "passive"))
      (node (ref "C43") (pin "2") (pinfunction "2_2") (pintype "passive"))
      (node (ref "C44") (pin "2") (pinfunction "2_2") (pintype "passive"))
      (node (ref "C45") (pin "2") (pinfunction "2_2") (pintype "passive"))
      (node (ref "C46") (pin "2") (pinfunction "2_2") (pintype "passive"))
      (node (ref "C47") (pin "1") (pinfunction "1_1") (pintype "passive"))
      (node (ref "C48") (pin "1") (pinfunction "1_1") (pintype "passive"))
      (node (ref "C49") (pin "1") (pinfunction "1_1") (pintype "passive"))
      (node (ref "C5") (pin "2") (pinfunction "2_2") (pintype "passive"))
      (node (ref "C50") (pin "1") (pinfunction "1_1") (pintype "passive"))
      (node (ref "C6") (pin "2") (pinfunction "2_2") (pintype "passive"))
      (node (ref "C7") (pin "1") (pinfunction "1_1") (pintype "passive"))
      (node (ref "C8") (pin "1") (pinfunction "1_1") (pintype "passive"))
      (node (ref "C9") (pin "1") (pinfunction "1_1") (pintype "passive"))
      (node (ref "J1") (pin "10") (pinfunction "A10_10") (pintype "passive"))
      (node (ref "J1") (pin "108") (pinfunction "B48_108") (pintype "passive"))
      (node (ref "J1") (pin "11") (pinfunction "A11_11") (pintype "passive"))
      (node (ref "J1") (pin "12") (pinfunction "A12_12") (pintype "passive"))
      (node (ref "J1") (pin "2") (pinfunction "A2_2") (pintype "passive"))
      (node (ref "J1") (pin "21") (pinfunction "A21_21") (pintype "passive"))
      (node (ref "J1") (pin "3") (pinfunction "A3_3") (pintype "passive"))
      (node (ref "J1") (pin "30") (pinfunction "A30_30") (pintype "passive"))
      (node (ref "J1") (pin "39") (pinfunction "A39_39") (pintype "passive"))
      (node (ref "J1") (pin "4") (pinfunction "A4_4") (pintype "passive"))
      (node (ref "J1") (pin "48") (pinfunction "A48_48") (pintype "passive"))
      (node (ref "J1") (pin "5") (pinfunction "A5_5") (pintype "passive"))
      (node (ref "J1") (pin "6") (pinfunction "A6_6") (pintype "passive"))
      (node (ref "J1") (pin "62") (pinfunction "B2_62") (pintype "passive"))
      (node (ref "J1") (pin "63") (pinfunction "B3_63") (pintype "passive"))
      (node (ref "J1") (pin "64") (pinfunction "B4_64") (pintype "passive"))
      (node (ref "J1") (pin "65") (pinfunction "B5_65") (pintype "passive"))
      (node (ref "J1") (pin "66") (pinfunction "B6_66") (pintype "passive"))
      (node (ref "J1") (pin "67") (pinfunction "B7_67") (pintype "passive"))
      (node (ref "J1") (pin "68") (pinfunction "B8_68") (pintype "passive"))
      (node (ref "J1") (pin "69") (pinfunction "B9_69") (pintype "passive"))
      (node (ref "J1") (pin "7") (pinfunction "A7_7") (pintype "passive"))
      (node (ref "J1") (pin "70") (pinfunction "B10_70") (pintype "passive"))
      (node (ref "J1") (pin "71") (pinfunction "B11_71") (pintype "passive"))
      (node (ref "J1") (pin "72") (pinfunction "B12_72") (pintype "passive"))
      (node (ref "J1") (pin "8") (pinfunction "A8_8") (pintype "passive"))
      (node (ref "J1") (pin "81") (pinfunction "B21_81") (pintype "passive"))
      (node (ref "J1") (pin "9") (pinfunction "A9_9") (pintype "passive"))
      (node (ref "J1") (pin "90") (pinfunction "B30_90") (pintype "passive"))
      (node (ref "J1") (pin "99") (pinfunction "B39_99") (pintype "passive"))
      (node (ref "J10") (pin "10") (pinfunction "A10_10") (pintype "passive"))
      (node (ref "J10") (pin "108") (pinfunction "B48_108") (pintype "passive"))
      (node (ref "J10") (pin "11") (pinfunction "A11_11") (pintype "passive"))
      (node (ref "J10") (pin "12") (pinfunction "A12_12") (pintype "passive"))
      (node (ref "J10") (pin "2") (pinfunction "A2_2") (pintype "passive"))
      (node (ref "J10") (pin "21") (pinfunction "A21_21") (pintype "passive"))
      (node (ref "J10") (pin "3") (pinfunction "A3_3") (pintype "passive"))
      (node (ref "J10") (pin "30") (pinfunction "A30_30") (pintype "passive"))
      (node (ref "J10") (pin "39") (pinfunction "A39_39") (pintype "passive"))
      (node (ref "J10") (pin "4") (pinfunction "A4_4") (pintype "passive"))
      (node (ref "J10") (pin "48") (pinfunction "A48_48") (pintype "passive"))
      (node (ref "J10") (pin "5") (pinfunction "A5_5") (pintype "passive"))
      (node (ref "J10") (pin "6") (pinfunction "A6_6") (pintype "passive"))
      (node (ref "J10") (pin "62") (pinfunction "B2_62") (pintype "passive"))
      (node (ref "J10") (pin "63") (pinfunction "B3_63") (pintype "passive"))
      (node (ref "J10") (pin "64") (pinfunction "B4_64") (pintype "passive"))
      (node (ref "J10") (pin "65") (pinfunction "B5_65") (pintype "passive"))
      (node (ref "J10") (pin "66") (pinfunction "B6_66") (pintype "passive"))
      (node (ref "J10") (pin "67") (pinfunction "B7_67") (pintype "passive"))
      (node (ref "J10") (pin "68") (pinfunction "B8_68") (pintype "passive"))
      (node (ref "J10") (pin "69") (pinfunction "B9_69") (pintype "passive"))
      (node (ref "J10") (pin "7") (pinfunction "A7_7") (pintype "passive"))
      (node (ref "J10") (pin "70") (pinfunction "B10_70") (pintype "passive"))
      (node (ref "J10") (pin "71") (pinfunction "B11_71") (pintype "passive"))
      (node (ref "J10") (pin "72") (pinfunction "B12_72") (pintype "passive"))
      (node (ref "J10") (pin "8") (pinfunction "A8_8") (pintype "passive"))
      (node (ref "J10") (pin "81") (pinfunction "B21_81") (pintype "passive"))
      (node (ref "J10") (pin "9") (pinfunction "A9_9") (pintype "passive"))
      (node (ref "J10") (pin "90") (pinfunction "B30_90") (pintype "passive"))
      (node (ref "J10") (pin "99") (pinfunction "B39_99") (pintype "passive"))
      (node (ref "J11") (pin "10") (pinfunction "A10_10") (pintype "passive"))
      (node (ref "J11") (pin "108") (pinfunction "B48_108") (pintype "passive"))
      (node (ref "J11") (pin "11") (pinfunction "A11_11") (pintype "passive"))
      (node (ref "J11") (pin "12") (pinfunction "A12_12") (pintype "passive"))
      (node (ref "J11") (pin "2") (pinfunction "A2_2") (pintype "passive"))
      (node (ref "J11") (pin "21") (pinfunction "A21_21") (pintype "passive"))
      (node (ref "J11") (pin "3") (pinfunction "A3_3") (pintype "passive"))
      (node (ref "J11") (pin "30") (pinfunction "A30_30") (pintype "passive"))
      (node (ref "J11") (pin "39") (pinfunction "A39_39") (pintype "passive"))
      (node (ref "J11") (pin "4") (pinfunction "A4_4") (pintype "passive"))
      (node (ref "J11") (pin "48") (pinfunction "A48_48") (pintype "passive"))
      (node (ref "J11") (pin "5") (pinfunction "A5_5") (pintype "passive"))
      (node (ref "J11") (pin "6") (pinfunction "A6_6") (pintype "passive"))
      (node (ref "J11") (pin "62") (pinfunction "B2_62") (pintype "passive"))
      (node (ref "J11") (pin "63") (pinfunction "B3_63") (pintype "passive"))
      (node (ref "J11") (pin "64") (pinfunction "B4_64") (pintype "passive"))
      (node (ref "J11") (pin "65") (pinfunction "B5_65") (pintype "passive"))
      (node (ref "J11") (pin "66") (pinfunction "B6_66") (pintype "passive"))
      (node (ref "J11") (pin "67") (pinfunction "B7_67") (pintype "passive"))
      (node (ref "J11") (pin "68") (pinfunction "B8_68") (pintype "passive"))
      (node (ref "J11") (pin "69") (pinfunction "B9_69") (pintype "passive"))
      (node (ref "J11") (pin "7") (pinfunction "A7_7") (pintype "passive"))
      (node (ref "J11") (pin "70") (pinfunction "B10_70") (pintype "passive"))
      (node (ref "J11") (pin "71") (pinfunction "B11_71") (pintype "passive"))
      (node (ref "J11") (pin "72") (pinfunction "B12_72") (pintype "passive"))
      (node (ref "J11") (pin "8") (pinfunction "A8_8") (pintype "passive"))
      (node (ref "J11") (pin "81") (pinfunction "B21_81") (pintype "passive"))
      (node (ref "J11") (pin "9") (pinfunction "A9_9") (pintype "passive"))
      (node (ref "J11") (pin "90") (pinfunction "B30_90") (pintype "passive"))
      (node (ref "J11") (pin "99") (pinfunction "B39_99") (pintype "passive"))
      (node (ref "J12") (pin "10") (pinfunction "A10_10") (pintype "passive"))
      (node (ref "J12") (pin "108") (pinfunction "B48_108") (pintype "passive"))
      (node (ref "J12") (pin "11") (pinfunction "A11_11") (pintype "passive"))
      (node (ref "J12") (pin "12") (pinfunction "A12_12") (pintype "passive"))
      (node (ref "J12") (pin "2") (pinfunction "A2_2") (pintype "passive"))
      (node (ref "J12") (pin "21") (pinfunction "A21_21") (pintype "passive"))
      (node (ref "J12") (pin "3") (pinfunction "A3_3") (pintype "passive"))
      (node (ref "J12") (pin "30") (pinfunction "A30_30") (pintype "passive"))
      (node (ref "J12") (pin "39") (pinfunction "A39_39") (pintype "passive"))
      (node (ref "J12") (pin "4") (pinfunction "A4_4") (pintype "passive"))
      (node (ref "J12") (pin "48") (pinfunction "A48_48") (pintype "passive"))
      (node (ref "J12") (pin "5") (pinfunction "A5_5") (pintype "passive"))
      (node (ref "J12") (pin "6") (pinfunction "A6_6") (pintype "passive"))
      (node (ref "J12") (pin "62") (pinfunction "B2_62") (pintype "passive"))
      (node (ref "J12") (pin "63") (pinfunction "B3_63") (pintype "passive"))
      (node (ref "J12") (pin "64") (pinfunction "B4_64") (pintype "passive"))
      (node (ref "J12") (pin "65") (pinfunction "B5_65") (pintype "passive"))
      (node (ref "J12") (pin "66") (pinfunction "B6_66") (pintype "passive"))
      (node (ref "J12") (pin "67") (pinfunction "B7_67") (pintype "passive"))
      (node (ref "J12") (pin "68") (pinfunction "B8_68") (pintype "passive"))
      (node (ref "J12") (pin "69") (pinfunction "B9_69") (pintype "passive"))
      (node (ref "J12") (pin "7") (pinfunction "A7_7") (pintype "passive"))
      (node (ref "J12") (pin "70") (pinfunction "B10_70") (pintype "passive"))
      (node (ref "J12") (pin "71") (pinfunction "B11_71") (pintype "passive"))
      (node (ref "J12") (pin "72") (pinfunction "B12_72") (pintype "passive"))
      (node (ref "J12") (pin "8") (pinfunction "A8_8") (pintype "passive"))
      (node (ref "J12") (pin "81") (pinfunction "B21_81") (pintype "passive"))
      (node (ref "J12") (pin "9") (pinfunction "A9_9") (pintype "passive"))
      (node (ref "J12") (pin "90") (pinfunction "B30_90") (pintype "passive"))
      (node (ref "J12") (pin "99") (pinfunction "B39_99") (pintype "passive"))
      (node (ref "J13") (pin "10") (pinfunction "A10_10") (pintype "passive"))
      (node (ref "J13") (pin "108") (pinfunction "B48_108") (pintype "passive"))
      (node (ref "J13") (pin "11") (pinfunction "A11_11") (pintype "passive"))
      (node (ref "J13") (pin "12") (pinfunction "A12_12") (pintype "passive"))
      (node (ref "J13") (pin "2") (pinfunction "A2_2") (pintype "passive"))
      (node (ref "J13") (pin "21") (pinfunction "A21_21") (pintype "passive"))
      (node (ref "J13") (pin "3") (pinfunction "A3_3") (pintype "passive"))
      (node (ref "J13") (pin "30") (pinfunction "A30_30") (pintype "passive"))
      (node (ref "J13") (pin "39") (pinfunction "A39_39") (pintype "passive"))
      (node (ref "J13") (pin "4") (pinfunction "A4_4") (pintype "passive"))
      (node (ref "J13") (pin "48") (pinfunction "A48_48") (pintype "passive"))
      (node (ref "J13") (pin "5") (pinfunction "A5_5") (pintype "passive"))
      (node (ref "J13") (pin "6") (pinfunction "A6_6") (pintype "passive"))
      (node (ref "J13") (pin "62") (pinfunction "B2_62") (pintype "passive"))
      (node (ref "J13") (pin "63") (pinfunction "B3_63") (pintype "passive"))
      (node (ref "J13") (pin "64") (pinfunction "B4_64") (pintype "passive"))
      (node (ref "J13") (pin "65") (pinfunction "B5_65") (pintype "passive"))
      (node (ref "J13") (pin "66") (pinfunction "B6_66") (pintype "passive"))
      (node (ref "J13") (pin "67") (pinfunction "B7_67") (pintype "passive"))
      (node (ref "J13") (pin "68") (pinfunction "B8_68") (pintype "passive"))
      (node (ref "J13") (pin "69") (pinfunction "B9_69") (pintype "passive"))
      (node (ref "J13") (pin "7") (pinfunction "A7_7") (pintype "passive"))
      (node (ref "J13") (pin "70") (pinfunction "B10_70") (pintype "passive"))
      (node (ref "J13") (pin "71") (pinfunction "B11_71") (pintype "passive"))
      (node (ref "J13") (pin "72") (pinfunction "B12_72") (pintype "passive"))
      (node (ref "J13") (pin "8") (pinfunction "A8_8") (pintype "passive"))
      (node (ref "J13") (pin "81") (pinfunction "B21_81") (pintype "passive"))
      (node (ref "J13") (pin "9") (pinfunction "A9_9") (pintype "passive"))
      (node (ref "J13") (pin "90") (pinfunction "B30_90") (pintype "passive"))
      (node (ref "J13") (pin "99") (pinfunction "B39_99") (pintype "passive"))
      (node (ref "J14") (pin "10") (pinfunction "A10_10") (pintype "passive"))
      (node (ref "J14") (pin "108") (pinfunction "B48_108") (pintype "passive"))
      (node (ref "J14") (pin "11") (pinfunction "A11_11") (pintype "passive"))
      (node (ref "J14") (pin "12") (pinfunction "A12_12") (pintype "passive"))
      (node (ref "J14") (pin "2") (pinfunction "A2_2") (pintype "passive"))
      (node (ref "J14") (pin "21") (pinfunction "A21_21") (pintype "passive"))
      (node (ref "J14") (pin "3") (pinfunction "A3_3") (pintype "passive"))
      (node (ref "J14") (pin "30") (pinfunction "A30_30") (pintype "passive"))
      (node (ref "J14") (pin "39") (pinfunction "A39_39") (pintype "passive"))
      (node (ref "J14") (pin "4") (pinfunction "A4_4") (pintype "passive"))
      (node (ref "J14") (pin "48") (pinfunction "A48_48") (pintype "passive"))
      (node (ref "J14") (pin "5") (pinfunction "A5_5") (pintype "passive"))
      (node (ref "J14") (pin "6") (pinfunction "A6_6") (pintype "passive"))
      (node (ref "J14") (pin "62") (pinfunction "B2_62") (pintype "passive"))
      (node (ref "J14") (pin "63") (pinfunction "B3_63") (pintype "passive"))
      (node (ref "J14") (pin "64") (pinfunction "B4_64") (pintype "passive"))
      (node (ref "J14") (pin "65") (pinfunction "B5_65") (pintype "passive"))
      (node (ref "J14") (pin "66") (pinfunction "B6_66") (pintype "passive"))
      (node (ref "J14") (pin "67") (pinfunction "B7_67") (pintype "passive"))
      (node (ref "J14") (pin "68") (pinfunction "B8_68") (pintype "passive"))
      (node (ref "J14") (pin "69") (pinfunction "B9_69") (pintype "passive"))
      (node (ref "J14") (pin "7") (pinfunction "A7_7") (pintype "passive"))
      (node (ref "J14") (pin "70") (pinfunction "B10_70") (pintype "passive"))
      (node (ref "J14") (pin "71") (pinfunction "B11_71") (pintype "passive"))
      (node (ref "J14") (pin "72") (pinfunction "B12_72") (pintype "passive"))
      (node (ref "J14") (pin "8") (pinfunction "A8_8") (pintype "passive"))
      (node (ref "J14") (pin "81") (pinfunction "B21_81") (pintype "passive"))
      (node (ref "J14") (pin "9") (pinfunction "A9_9") (pintype "passive"))
      (node (ref "J14") (pin "90") (pinfunction "B30_90") (pintype "passive"))
      (node (ref "J14") (pin "99") (pinfunction "B39_99") (pintype "passive"))
      (node (ref "J15") (pin "10") (pinfunction "A10_10") (pintype "passive"))
      (node (ref "J15") (pin "108") (pinfunction "B48_108") (pintype "passive"))
      (node (ref "J15") (pin "11") (pinfunction "A11_11") (pintype "passive"))
      (node (ref "J15") (pin "12") (pinfunction "A12_12") (pintype "passive"))
      (node (ref "J15") (pin "2") (pinfunction "A2_2") (pintype "passive"))
      (node (ref "J15") (pin "21") (pinfunction "A21_21") (pintype "passive"))
      (node (ref "J15") (pin "3") (pinfunction "A3_3") (pintype "passive"))
      (node (ref "J15") (pin "30") (pinfunction "A30_30") (pintype "passive"))
      (node (ref "J15") (pin "39") (pinfunction "A39_39") (pintype "passive"))
      (node (ref "J15") (pin "4") (pinfunction "A4_4") (pintype "passive"))
      (node (ref "J15") (pin "48") (pinfunction "A48_48") (pintype "passive"))
      (node (ref "J15") (pin "5") (pinfunction "A5_5") (pintype "passive"))
      (node (ref "J15") (pin "6") (pinfunction "A6_6") (pintype "passive"))
      (node (ref "J15") (pin "62") (pinfunction "B2_62") (pintype "passive"))
      (node (ref "J15") (pin "63") (pinfunction "B3_63") (pintype "passive"))
      (node (ref "J15") (pin "64") (pinfunction "B4_64") (pintype "passive"))
      (node (ref "J15") (pin "65") (pinfunction "B5_65") (pintype "passive"))
      (node (ref "J15") (pin "66") (pinfunction "B6_66") (pintype "passive"))
      (node (ref "J15") (pin "67") (pinfunction "B7_67") (pintype "passive"))
      (node (ref "J15") (pin "68") (pinfunction "B8_68") (pintype "passive"))
      (node (ref "J15") (pin "69") (pinfunction "B9_69") (pintype "passive"))
      (node (ref "J15") (pin "7") (pinfunction "A7_7") (pintype "passive"))
      (node (ref "J15") (pin "70") (pinfunction "B10_70") (pintype "passive"))
      (node (ref "J15") (pin "71") (pinfunction "B11_71") (pintype "passive"))
      (node (ref "J15") (pin "72") (pinfunction "B12_72") (pintype "passive"))
      (node (ref "J15") (pin "8") (pinfunction "A8_8") (pintype "passive"))
      (node (ref "J15") (pin "81") (pinfunction "B21_81") (pintype "passive"))
      (node (ref "J15") (pin "9") (pinfunction "A9_9") (pintype "passive"))
      (node (ref "J15") (pin "90") (pinfunction "B30_90") (pintype "passive"))
      (node (ref "J15") (pin "99") (pinfunction "B39_99") (pintype "passive"))
      (node (ref "J16") (pin "10") (pinfunction "A10_10") (pintype "passive"))
      (node (ref "J16") (pin "108") (pinfunction "B48_108") (pintype "passive"))
      (node (ref "J16") (pin "11") (pinfunction "A11_11") (pintype "passive"))
      (node (ref "J16") (pin "12") (pinfunction "A12_12") (pintype "passive"))
      (node (ref "J16") (pin "2") (pinfunction "A2_2") (pintype "passive"))
      (node (ref "J16") (pin "21") (pinfunction "A21_21") (pintype "passive"))
      (node (ref "J16") (pin "3") (pinfunction "A3_3") (pintype "passive"))
      (node (ref "J16") (pin "30") (pinfunction "A30_30") (pintype "passive"))
      (node (ref "J16") (pin "39") (pinfunction "A39_39") (pintype "passive"))
      (node (ref "J16") (pin "4") (pinfunction "A4_4") (pintype "passive"))
      (node (ref "J16") (pin "48") (pinfunction "A48_48") (pintype "passive"))
      (node (ref "J16") (pin "5") (pinfunction "A5_5") (pintype "passive"))
      (node (ref "J16") (pin "6") (pinfunction "A6_6") (pintype "passive"))
      (node (ref "J16") (pin "62") (pinfunction "B2_62") (pintype "passive"))
      (node (ref "J16") (pin "63") (pinfunction "B3_63") (pintype "passive"))
      (node (ref "J16") (pin "64") (pinfunction "B4_64") (pintype "passive"))
      (node (ref "J16") (pin "65") (pinfunction "B5_65") (pintype "passive"))
      (node (ref "J16") (pin "66") (pinfunction "B6_66") (pintype "passive"))
      (node (ref "J16") (pin "67") (pinfunction "B7_67") (pintype "passive"))
      (node (ref "J16") (pin "68") (pinfunction "B8_68") (pintype "passive"))
      (node (ref "J16") (pin "69") (pinfunction "B9_69") (pintype "passive"))
      (node (ref "J16") (pin "7") (pinfunction "A7_7") (pintype "passive"))
      (node (ref "J16") (pin "70") (pinfunction "B10_70") (pintype "passive"))
      (node (ref "J16") (pin "71") (pinfunction "B11_71") (pintype "passive"))
      (node (ref "J16") (pin "72") (pinfunction "B12_72") (pintype "passive"))
      (node (ref "J16") (pin "8") (pinfunction "A8_8") (pintype "passive"))
      (node (ref "J16") (pin "81") (pinfunction "B21_81") (pintype "passive"))
      (node (ref "J16") (pin "9") (pinfunction "A9_9") (pintype "passive"))
      (node (ref "J16") (pin "90") (pinfunction "B30_90") (pintype "passive"))
      (node (ref "J16") (pin "99") (pinfunction "B39_99") (pintype "passive"))
      (node (ref "J2") (pin "10") (pinfunction "A10_10") (pintype "passive"))
      (node (ref "J2") (pin "108") (pinfunction "B48_108") (pintype "passive"))
      (node (ref "J2") (pin "11") (pinfunction "A11_11") (pintype "passive"))
      (node (ref "J2") (pin "12") (pinfunction "A12_12") (pintype "passive"))
      (node (ref "J2") (pin "2") (pinfunction "A2_2") (pintype "passive"))
      (node (ref "J2") (pin "21") (pinfunction "A21_21") (pintype "passive"))
      (node (ref "J2") (pin "3") (pinfunction "A3_3") (pintype "passive"))
      (node (ref "J2") (pin "30") (pinfunction "A30_30") (pintype "passive"))
      (node (ref "J2") (pin "39") (pinfunction "A39_39") (pintype "passive"))
      (node (ref "J2") (pin "4") (pinfunction "A4_4") (pintype "passive"))
      (node (ref "J2") (pin "48") (pinfunction "A48_48") (pintype "passive"))
      (node (ref "J2") (pin "5") (pinfunction "A5_5") (pintype "passive"))
      (node (ref "J2") (pin "6") (pinfunction "A6_6") (pintype "passive"))
      (node (ref "J2") (pin "62") (pinfunction "B2_62") (pintype "passive"))
      (node (ref "J2") (pin "63") (pinfunction "B3_63") (pintype "passive"))
      (node (ref "J2") (pin "64") (pinfunction "B4_64") (pintype "passive"))
      (node (ref "J2") (pin "65") (pinfunction "B5_65") (pintype "passive"))
      (node (ref "J2") (pin "66") (pinfunction "B6_66") (pintype "passive"))
      (node (ref "J2") (pin "67") (pinfunction "B7_67") (pintype "passive"))
      (node (ref "J2") (pin "68") (pinfunction "B8_68") (pintype "passive"))
      (node (ref "J2") (pin "69") (pinfunction "B9_69") (pintype "passive"))
      (node (ref "J2") (pin "7") (pinfunction "A7_7") (pintype "passive"))
      (node (ref "J2") (pin "70") (pinfunction "B10_70") (pintype "passive"))
      (node (ref "J2") (pin "71") (pinfunction "B11_71") (pintype "passive"))
      (node (ref "J2") (pin "72") (pinfunction "B12_72") (pintype "passive"))
      (node (ref "J2") (pin "8") (pinfunction "A8_8") (pintype "passive"))
      (node (ref "J2") (pin "81") (pinfunction "B21_81") (pintype "passive"))
      (node (ref "J2") (pin "9") (pinfunction "A9_9") (pintype "passive"))
      (node (ref "J2") (pin "90") (pinfunction "B30_90") (pintype "passive"))
      (node (ref "J2") (pin "99") (pinfunction "B39_99") (pintype "passive"))
      (node (ref "J3") (pin "10") (pinfunction "A10_10") (pintype "passive"))
      (node (ref "J3") (pin "108") (pinfunction "B48_108") (pintype "passive"))
      (node (ref "J3") (pin "11") (pinfunction "A11_11") (pintype "passive"))
      (node (ref "J3") (pin "12") (pinfunction "A12_12") (pintype "passive"))
      (node (ref "J3") (pin "2") (pinfunction "A2_2") (pintype "passive"))
      (node (ref "J3") (pin "21") (pinfunction "A21_21") (pintype "passive"))
      (node (ref "J3") (pin "3") (pinfunction "A3_3") (pintype "passive"))
      (node (ref "J3") (pin "30") (pinfunction "A30_30") (pintype "passive"))
      (node (ref "J3") (pin "39") (pinfunction "A39_39") (pintype "passive"))
      (node (ref "J3") (pin "4") (pinfunction "A4_4") (pintype "passive"))
      (node (ref "J3") (pin "48") (pinfunction "A48_48") (pintype "passive"))
      (node (ref "J3") (pin "5") (pinfunction "A5_5") (pintype "passive"))
      (node (ref "J3") (pin "6") (pinfunction "A6_6") (pintype "passive"))
      (node (ref "J3") (pin "62") (pinfunction "B2_62") (pintype "passive"))
      (node (ref "J3") (pin "63") (pinfunction "B3_63") (pintype "passive"))
      (node (ref "J3") (pin "64") (pinfunction "B4_64") (pintype "passive"))
      (node (ref "J3") (pin "65") (pinfunction "B5_65") (pintype "passive"))
      (node (ref "J3") (pin "66") (pinfunction "B6_66") (pintype "passive"))
      (node (ref "J3") (pin "67") (pinfunction "B7_67") (pintype "passive"))
      (node (ref "J3") (pin "68") (pinfunction "B8_68") (pintype "passive"))
      (node (ref "J3") (pin "69") (pinfunction "B9_69") (pintype "passive"))
      (node (ref "J3") (pin "7") (pinfunction "A7_7") (pintype "passive"))
      (node (ref "J3") (pin "70") (pinfunction "B10_70") (pintype "passive"))
      (node (ref "J3") (pin "71") (pinfunction "B11_71") (pintype "passive"))
      (node (ref "J3") (pin "72") (pinfunction "B12_72") (pintype "passive"))
      (node (ref "J3") (pin "8") (pinfunction "A8_8") (pintype "passive"))
      (node (ref "J3") (pin "81") (pinfunction "B21_81") (pintype "passive"))
      (node (ref "J3") (pin "9") (pinfunction "A9_9") (pintype "passive"))
      (node (ref "J3") (pin "90") (pinfunction "B30_90") (pintype "passive"))
      (node (ref "J3") (pin "99") (pinfunction "B39_99") (pintype "passive"))
      (node (ref "J4") (pin "10") (pinfunction "A10_10") (pintype "passive"))
      (node (ref "J4") (pin "108") (pinfunction "B48_108") (pintype "passive"))
      (node (ref "J4") (pin "11") (pinfunction "A11_11") (pintype "passive"))
      (node (ref "J4") (pin "12") (pinfunction "A12_12") (pintype "passive"))
      (node (ref "J4") (pin "2") (pinfunction "A2_2") (pintype "passive"))
      (node (ref "J4") (pin "21") (pinfunction "A21_21") (pintype "passive"))
      (node (ref "J4") (pin "3") (pinfunction "A3_3") (pintype "passive"))
      (node (ref "J4") (pin "30") (pinfunction "A30_30") (pintype "passive"))
      (node (ref "J4") (pin "39") (pinfunction "A39_39") (pintype "passive"))
      (node (ref "J4") (pin "4") (pinfunction "A4_4") (pintype "passive"))
      (node (ref "J4") (pin "48") (pinfunction "A48_48") (pintype "passive"))
      (node (ref "J4") (pin "5") (pinfunction "A5_5") (pintype "passive"))
      (node (ref "J4") (pin "6") (pinfunction "A6_6") (pintype "passive"))
      (node (ref "J4") (pin "62") (pinfunction "B2_62") (pintype "passive"))
      (node (ref "J4") (pin "63") (pinfunction "B3_63") (pintype "passive"))
      (node (ref "J4") (pin "64") (pinfunction "B4_64") (pintype "passive"))
      (node (ref "J4") (pin "65") (pinfunction "B5_65") (pintype "passive"))
      (node (ref "J4") (pin "66") (pinfunction "B6_66") (pintype "passive"))
      (node (ref "J4") (pin "67") (pinfunction "B7_67") (pintype "passive"))
      (node (ref "J4") (pin "68") (pinfunction "B8_68") (pintype "passive"))
      (node (ref "J4") (pin "69") (pinfunction "B9_69") (pintype "passive"))
      (node (ref "J4") (pin "7") (pinfunction "A7_7") (pintype "passive"))
      (node (ref "J4") (pin "70") (pinfunction "B10_70") (pintype "passive"))
      (node (ref "J4") (pin "71") (pinfunction "B11_71") (pintype "passive"))
      (node (ref "J4") (pin "72") (pinfunction "B12_72") (pintype "passive"))
      (node (ref "J4") (pin "8") (pinfunction "A8_8") (pintype "passive"))
      (node (ref "J4") (pin "81") (pinfunction "B21_81") (pintype "passive"))
      (node (ref "J4") (pin "9") (pinfunction "A9_9") (pintype "passive"))
      (node (ref "J4") (pin "90") (pinfunction "B30_90") (pintype "passive"))
      (node (ref "J4") (pin "99") (pinfunction "B39_99") (pintype "passive"))
      (node (ref "J5") (pin "10") (pinfunction "A10_10") (pintype "passive"))
      (node (ref "J5") (pin "108") (pinfunction "B48_108") (pintype "passive"))
      (node (ref "J5") (pin "11") (pinfunction "A11_11") (pintype "passive"))
      (node (ref "J5") (pin "12") (pinfunction "A12_12") (pintype "passive"))
      (node (ref "J5") (pin "2") (pinfunction "A2_2") (pintype "passive"))
      (node (ref "J5") (pin "21") (pinfunction "A21_21") (pintype "passive"))
      (node (ref "J5") (pin "3") (pinfunction "A3_3") (pintype "passive"))
      (node (ref "J5") (pin "30") (pinfunction "A30_30") (pintype "passive"))
      (node (ref "J5") (pin "39") (pinfunction "A39_39") (pintype "passive"))
      (node (ref "J5") (pin "4") (pinfunction "A4_4") (pintype "passive"))
      (node (ref "J5") (pin "48") (pinfunction "A48_48") (pintype "passive"))
      (node (ref "J5") (pin "5") (pinfunction "A5_5") (pintype "passive"))
      (node (ref "J5") (pin "6") (pinfunction "A6_6") (pintype "passive"))
      (node (ref "J5") (pin "62") (pinfunction "B2_62") (pintype "passive"))
      (node (ref "J5") (pin "63") (pinfunction "B3_63") (pintype "passive"))
      (node (ref "J5") (pin "64") (pinfunction "B4_64") (pintype "passive"))
      (node (ref "J5") (pin "65") (pinfunction "B5_65") (pintype "passive"))
      (node (ref "J5") (pin "66") (pinfunction "B6_66") (pintype "passive"))
      (node (ref "J5") (pin "67") (pinfunction "B7_67") (pintype "passive"))
      (node (ref "J5") (pin "68") (pinfunction "B8_68") (pintype "passive"))
      (node (ref "J5") (pin "69") (pinfunction "B9_69") (pintype "passive"))
      (node (ref "J5") (pin "7") (pinfunction "A7_7") (pintype "passive"))
      (node (ref "J5") (pin "70") (pinfunction "B10_70") (pintype "passive"))
      (node (ref "J5") (pin "71") (pinfunction "B11_71") (pintype "passive"))
      (node (ref "J5") (pin "72") (pinfunction "B12_72") (pintype "passive"))
      (node (ref "J5") (pin "8") (pinfunction "A8_8") (pintype "passive"))
      (node (ref "J5") (pin "81") (pinfunction "B21_81") (pintype "passive"))
      (node (ref "J5") (pin "9") (pinfunction "A9_9") (pintype "passive"))
      (node (ref "J5") (pin "90") (pinfunction "B30_90") (pintype "passive"))
      (node (ref "J5") (pin "99") (pinfunction "B39_99") (pintype "passive"))
      (node (ref "J6") (pin "10") (pinfunction "A10_10") (pintype "passive"))
      (node (ref "J6") (pin "108") (pinfunction "B48_108") (pintype "passive"))
      (node (ref "J6") (pin "11") (pinfunction "A11_11") (pintype "passive"))
      (node (ref "J6") (pin "12") (pinfunction "A12_12") (pintype "passive"))
      (node (ref "J6") (pin "2") (pinfunction "A2_2") (pintype "passive"))
      (node (ref "J6") (pin "21") (pinfunction "A21_21") (pintype "passive"))
      (node (ref "J6") (pin "3") (pinfunction "A3_3") (pintype "passive"))
      (node (ref "J6") (pin "30") (pinfunction "A30_30") (pintype "passive"))
      (node (ref "J6") (pin "39") (pinfunction "A39_39") (pintype "passive"))
      (node (ref "J6") (pin "4") (pinfunction "A4_4") (pintype "passive"))
      (node (ref "J6") (pin "48") (pinfunction "A48_48") (pintype "passive"))
      (node (ref "J6") (pin "5") (pinfunction "A5_5") (pintype "passive"))
      (node (ref "J6") (pin "6") (pinfunction "A6_6") (pintype "passive"))
      (node (ref "J6") (pin "62") (pinfunction "B2_62") (pintype "passive"))
      (node (ref "J6") (pin "63") (pinfunction "B3_63") (pintype "passive"))
      (node (ref "J6") (pin "64") (pinfunction "B4_64") (pintype "passive"))
      (node (ref "J6") (pin "65") (pinfunction "B5_65") (pintype "passive"))
      (node (ref "J6") (pin "66") (pinfunction "B6_66") (pintype "passive"))
      (node (ref "J6") (pin "67") (pinfunction "B7_67") (pintype "passive"))
      (node (ref "J6") (pin "68") (pinfunction "B8_68") (pintype "passive"))
      (node (ref "J6") (pin "69") (pinfunction "B9_69") (pintype "passive"))
      (node (ref "J6") (pin "7") (pinfunction "A7_7") (pintype "passive"))
      (node (ref "J6") (pin "70") (pinfunction "B10_70") (pintype "passive"))
      (node (ref "J6") (pin "71") (pinfunction "B11_71") (pintype "passive"))
      (node (ref "J6") (pin "72") (pinfunction "B12_72") (pintype "passive"))
      (node (ref "J6") (pin "8") (pinfunction "A8_8") (pintype "passive"))
      (node (ref "J6") (pin "81") (pinfunction "B21_81") (pintype "passive"))
      (node (ref "J6") (pin "9") (pinfunction "A9_9") (pintype "passive"))
      (node (ref "J6") (pin "90") (pinfunction "B30_90") (pintype "passive"))
      (node (ref "J6") (pin "99") (pinfunction "B39_99") (pintype "passive"))
      (node (ref "J7") (pin "10") (pinfunction "A10_10") (pintype "passive"))
      (node (ref "J7") (pin "108") (pinfunction "B48_108") (pintype "passive"))
      (node (ref "J7") (pin "11") (pinfunction "A11_11") (pintype "passive"))
      (node (ref "J7") (pin "12") (pinfunction "A12_12") (pintype "passive"))
      (node (ref "J7") (pin "2") (pinfunction "A2_2") (pintype "passive"))
      (node (ref "J7") (pin "21") (pinfunction "A21_21") (pintype "passive"))
      (node (ref "J7") (pin "3") (pinfunction "A3_3") (pintype "passive"))
      (node (ref "J7") (pin "30") (pinfunction "A30_30") (pintype "passive"))
      (node (ref "J7") (pin "39") (pinfunction "A39_39") (pintype "passive"))
      (node (ref "J7") (pin "4") (pinfunction "A4_4") (pintype "passive"))
      (node (ref "J7") (pin "48") (pinfunction "A48_48") (pintype "passive"))
      (node (ref "J7") (pin "5") (pinfunction "A5_5") (pintype "passive"))
      (node (ref "J7") (pin "6") (pinfunction "A6_6") (pintype "passive"))
      (node (ref "J7") (pin "62") (pinfunction "B2_62") (pintype "passive"))
      (node (ref "J7") (pin "63") (pinfunction "B3_63") (pintype "passive"))
      (node (ref "J7") (pin "64") (pinfunction "B4_64") (pintype "passive"))
      (node (ref "J7") (pin "65") (pinfunction "B5_65") (pintype "passive"))
      (node (ref "J7") (pin "66") (pinfunction "B6_66") (pintype "passive"))
      (node (ref "J7") (pin "67") (pinfunction "B7_67") (pintype "passive"))
      (node (ref "J7") (pin "68") (pinfunction "B8_68") (pintype "passive"))
      (node (ref "J7") (pin "69") (pinfunction "B9_69") (pintype "passive"))
      (node (ref "J7") (pin "7") (pinfunction "A7_7") (pintype "passive"))
      (node (ref "J7") (pin "70") (pinfunction "B10_70") (pintype "passive"))
      (node (ref "J7") (pin "71") (pinfunction "B11_71") (pintype "passive"))
      (node (ref "J7") (pin "72") (pinfunction "B12_72") (pintype "passive"))
      (node (ref "J7") (pin "8") (pinfunction "A8_8") (pintype "passive"))
      (node (ref "J7") (pin "81") (pinfunction "B21_81") (pintype "passive"))
      (node (ref "J7") (pin "9") (pinfunction "A9_9") (pintype "passive"))
      (node (ref "J7") (pin "90") (pinfunction "B30_90") (pintype "passive"))
      (node (ref "J7") (pin "99") (pinfunction "B39_99") (pintype "passive"))
      (node (ref "J8") (pin "10") (pinfunction "A10_10") (pintype "passive"))
      (node (ref "J8") (pin "108") (pinfunction "B48_108") (pintype "passive"))
      (node (ref "J8") (pin "11") (pinfunction "A11_11") (pintype "passive"))
      (node (ref "J8") (pin "12") (pinfunction "A12_12") (pintype "passive"))
      (node (ref "J8") (pin "2") (pinfunction "A2_2") (pintype "passive"))
      (node (ref "J8") (pin "21") (pinfunction "A21_21") (pintype "passive"))
      (node (ref "J8") (pin "3") (pinfunction "A3_3") (pintype "passive"))
      (node (ref "J8") (pin "30") (pinfunction "A30_30") (pintype "passive"))
      (node (ref "J8") (pin "39") (pinfunction "A39_39") (pintype "passive"))
      (node (ref "J8") (pin "4") (pinfunction "A4_4") (pintype "passive"))
      (node (ref "J8") (pin "48") (pinfunction "A48_48") (pintype "passive"))
      (node (ref "J8") (pin "5") (pinfunction "A5_5") (pintype "passive"))
      (node (ref "J8") (pin "6") (pinfunction "A6_6") (pintype "passive"))
      (node (ref "J8") (pin "62") (pinfunction "B2_62") (pintype "passive"))
      (node (ref "J8") (pin "63") (pinfunction "B3_63") (pintype "passive"))
      (node (ref "J8") (pin "64") (pinfunction "B4_64") (pintype "passive"))
      (node (ref "J8") (pin "65") (pinfunction "B5_65") (pintype "passive"))
      (node (ref "J8") (pin "66") (pinfunction "B6_66") (pintype "passive"))
      (node (ref "J8") (pin "67") (pinfunction "B7_67") (pintype "passive"))
      (node (ref "J8") (pin "68") (pinfunction "B8_68") (pintype "passive"))
      (node (ref "J8") (pin "69") (pinfunction "B9_69") (pintype "passive"))
      (node (ref "J8") (pin "7") (pinfunction "A7_7") (pintype "passive"))
      (node (ref "J8") (pin "70") (pinfunction "B10_70") (pintype "passive"))
      (node (ref "J8") (pin "71") (pinfunction "B11_71") (pintype "passive"))
      (node (ref "J8") (pin "72") (pinfunction "B12_72") (pintype "passive"))
      (node (ref "J8") (pin "8") (pinfunction "A8_8") (pintype "passive"))
      (node (ref "J8") (pin "81") (pinfunction "B21_81") (pintype "passive"))
      (node (ref "J8") (pin "9") (pinfunction "A9_9") (pintype "passive"))
      (node (ref "J8") (pin "90") (pinfunction "B30_90") (pintype "passive"))
      (node (ref "J8") (pin "99") (pinfunction "B39_99") (pintype "passive"))
      (node (ref "J9") (pin "10") (pinfunction "A10_10") (pintype "passive"))
      (node (ref "J9") (pin "108") (pinfunction "B48_108") (pintype "passive"))
      (node (ref "J9") (pin "11") (pinfunction "A11_11") (pintype "passive"))
      (node (ref "J9") (pin "12") (pinfunction "A12_12") (pintype "passive"))
      (node (ref "J9") (pin "2") (pinfunction "A2_2") (pintype "passive"))
      (node (ref "J9") (pin "21") (pinfunction "A21_21") (pintype "passive"))
      (node (ref "J9") (pin "3") (pinfunction "A3_3") (pintype "passive"))
      (node (ref "J9") (pin "30") (pinfunction "A30_30") (pintype "passive"))
      (node (ref "J9") (pin "39") (pinfunction "A39_39") (pintype "passive"))
      (node (ref "J9") (pin "4") (pinfunction "A4_4") (pintype "passive"))
      (node (ref "J9") (pin "48") (pinfunction "A48_48") (pintype "passive"))
      (node (ref "J9") (pin "5") (pinfunction "A5_5") (pintype "passive"))
      (node (ref "J9") (pin "6") (pinfunction "A6_6") (pintype "passive"))
      (node (ref "J9") (pin "62") (pinfunction "B2_62") (pintype "passive"))
      (node (ref "J9") (pin "63") (pinfunction "B3_63") (pintype "passive"))
      (node (ref "J9") (pin "64") (pinfunction "B4_64") (pintype "passive"))
      (node (ref "J9") (pin "65") (pinfunction "B5_65") (pintype "passive"))
      (node (ref "J9") (pin "66") (pinfunction "B6_66") (pintype "passive"))
      (node (ref "J9") (pin "67") (pinfunction "B7_67") (pintype "passive"))
      (node (ref "J9") (pin "68") (pinfunction "B8_68") (pintype "passive"))
      (node (ref "J9") (pin "69") (pinfunction "B9_69") (pintype "passive"))
      (node (ref "J9") (pin "7") (pinfunction "A7_7") (pintype "passive"))
      (node (ref "J9") (pin "70") (pinfunction "B10_70") (pintype "passive"))
      (node (ref "J9") (pin "71") (pinfunction "B11_71") (pintype "passive"))
      (node (ref "J9") (pin "72") (pinfunction "B12_72") (pintype "passive"))
      (node (ref "J9") (pin "8") (pinfunction "A8_8") (pintype "passive"))
      (node (ref "J9") (pin "81") (pinfunction "B21_81") (pintype "passive"))
      (node (ref "J9") (pin "9") (pinfunction "A9_9") (pintype "passive"))
      (node (ref "J9") (pin "90") (pinfunction "B30_90") (pintype "passive"))
      (node (ref "J9") (pin "99") (pinfunction "B39_99") (pintype "passive"))
      (node (ref "P1") (pin "2") (pinfunction "Y_2") (pintype "passive"))
      (node (ref "P10") (pin "15") (pinfunction "15_15") (pintype "passive"))
      (node (ref "P10") (pin "38") (pinfunction "38_38") (pintype "passive"))
      (node (ref "P10") (pin "40") (pinfunction "40_40") (pintype "passive"))
      (node (ref "P2") (pin "2") (pinfunction "Y_2") (pintype "passive"))
      (node (ref "P3") (pin "2") (pinfunction "Y_2") (pintype "passive"))
      (node (ref "P4") (pin "2") (pinfunction "Y_2") (pintype "passive"))
      (node (ref "P5") (pin "1") (pinfunction "1_1") (pintype "passive"))
      (node (ref "P5") (pin "40") (pinfunction "40_40") (pintype "passive"))
      (node (ref "P6") (pin "1") (pinfunction "1_1") (pintype "passive"))
      (node (ref "P6") (pin "20") (pinfunction "20_20") (pintype "passive"))
      (node (ref "P7") (pin "1") (pinfunction "1_1") (pintype "passive"))
      (node (ref "P7") (pin "13") (pinfunction "13_13") (pintype "passive"))
      (node (ref "P7") (pin "14") (pinfunction "14_14") (pintype "passive"))
      (node (ref "P7") (pin "36") (pinfunction "36_36") (pintype "passive"))
      (node (ref "P8") (pin "14") (pinfunction "14_14") (pintype "passive"))
      (node (ref "P8") (pin "2") (pinfunction "2_2") (pintype "passive"))
      (node (ref "P8") (pin "35") (pinfunction "35_35") (pintype "passive"))
      (node (ref "P9") (pin "16") (pinfunction "16_16") (pintype "passive"))
      (node (ref "P9") (pin "38") (pinfunction "38_38") (pintype "passive"))
      (node (ref "P9") (pin "40") (pinfunction "40_40") (pintype "passive"))
      (node (ref "R41") (pin "1") (pinfunction "1_1") (pintype "passive"))
      (node (ref "R42") (pin "1") (pinfunction "1_1") (pintype "passive"))
      (node (ref "R43") (pin "1") (pinfunction "1_1") (pintype "passive"))
      (node (ref "R44") (pin "1") (pinfunction "1_1") (pintype "passive"))
      (node (ref "R45") (pin "1") (pinfunction "1_1") (pintype "passive"))
      (node (ref "R46") (pin "1") (pinfunction "1_1") (pintype "passive"))
      (node (ref "R47") (pin "1") (pinfunction "1_1") (pintype "passive"))
      (node (ref "R48") (pin "1") (pinfunction "1_1") (pintype "passive"))
      (node (ref "U1") (pin "8") (pinfunction "GND_8") (pintype "passive"))
      (node (ref "U10") (pin "12") (pinfunction "EN#_12") (pintype "passive"))
      (node (ref "U10") (pin "8") (pinfunction "GND_8") (pintype "passive"))
      (node (ref "U11") (pin "1A2") (pinfunction "GND_1A2") (pintype "passive"))
      (node (ref "U11") (pin "1B2") (pinfunction "GND_1B2") (pintype "passive"))
      (node (ref "U11") (pin "1B39") (pinfunction "GND_1B39") (pintype "passive"))
      (node (ref "U11") (pin "1C2") (pinfunction "GND_1C2") (pintype "passive"))
      (node (ref "U11") (pin "1C39") (pinfunction "GND_1C39") (pintype "passive"))
      (node (ref "U11") (pin "2A2") (pinfunction "GND_2A2") (pintype "passive"))
      (node (ref "U11") (pin "2A39") (pinfunction "GND_2A39") (pintype "passive"))
      (node (ref "U11") (pin "2B2") (pinfunction "GND_2B2") (pintype "passive"))
      (node (ref "U11") (pin "2B39") (pinfunction "GND_2B39") (pintype "passive"))
      (node (ref "U11") (pin "2C2") (pinfunction "GND_2C2") (pintype "passive"))
      (node (ref "U11") (pin "2C39") (pinfunction "GND_2C39") (pintype "passive"))
      (node (ref "U12") (pin "2") (pinfunction "GND_2") (pintype "passive"))
      (node (ref "U13") (pin "2") (pinfunction "GND_2") (pintype "passive"))
      (node (ref "U14") (pin "2") (pinfunction "GND_2") (pintype "passive"))
      (node (ref "U15") (pin "2") (pinfunction "GND_2") (pintype "passive"))
      (node (ref "U2") (pin "8") (pinfunction "GND_8") (pintype "passive"))
      (node (ref "U3") (pin "12") (pinfunction "EN#_12") (pintype "passive"))
      (node (ref "U3") (pin "8") (pinfunction "GND_8") (pintype "passive"))
      (node (ref "U4") (pin "12") (pinfunction "EN#_12") (pintype "passive"))
      (node (ref "U4") (pin "8") (pinfunction "GND_8") (pintype "passive"))
      (node (ref "U5") (pin "12") (pinfunction "EN#_12") (pintype "passive"))
      (node (ref "U5") (pin "8") (pinfunction "GND_8") (pintype "passive"))
      (node (ref "U6") (pin "12") (pinfunction "EN#_12") (pintype "passive"))
      (node (ref "U6") (pin "8") (pinfunction "GND_8") (pintype "passive"))
      (node (ref "U7") (pin "12") (pinfunction "EN#_12") (pintype "passive"))
      (node (ref "U7") (pin "8") (pinfunction "GND_8") (pintype "passive"))
      (node (ref "U8") (pin "12") (pinfunction "EN#_12") (pintype "passive"))
      (node (ref "U8") (pin "8") (pinfunction "GND_8") (pintype "passive"))
      (node (ref "U9") (pin "12") (pinfunction "EN#_12") (pintype "passive"))
      (node (ref "U9") (pin "8") (pinfunction "GND_8") (pintype "passive"))
    )
    (net (code "193") (name "Net-(D1-K)") (class "Default")
      (node (ref "D1") (pin "2") (pinfunction "K_2") (pintype "passive"))
      (node (ref "R41") (pin "2") (pinfunction "2_2") (pintype "passive"))
    )
    (net (code "194") (name "Net-(D2-K)") (class "Default")
      (node (ref "D2") (pin "2") (pinfunction "K_2") (pintype "passive"))
      (node (ref "R42") (pin "2") (pinfunction "2_2") (pintype "passive"))
    )
    (net (code "195") (name "Net-(D3-K)") (class "Default")
      (node (ref "D3") (pin "2") (pinfunction "K_2") (pintype "passive"))
      (node (ref "R43") (pin "2") (pinfunction "2_2") (pintype "passive"))
    )
    (net (code "196") (name "Net-(D4-K)") (class "Default")
      (node (ref "D4") (pin "2") (pinfunction "K_2") (pintype "passive"))
      (node (ref "R44") (pin "2") (pinfunction "2_2") (pintype "passive"))
    )
    (net (code "197") (name "Net-(D5-K)") (class "Default")
      (node (ref "D5") (pin "2") (pinfunction "K_2") (pintype "passive"))
      (node (ref "R45") (pin "2") (pinfunction "2_2") (pintype "passive"))
    )
    (net (code "198") (name "Net-(D6-K)") (class "Default")
      (node (ref "D6") (pin "2") (pinfunction "K_2") (pintype "passive"))
      (node (ref "R46") (pin "2") (pinfunction "2_2") (pintype "passive"))
    )
    (net (code "199") (name "Net-(D7-K)") (class "Default")
      (node (ref "D7") (pin "2") (pinfunction "K_2") (pintype "passive"))
      (node (ref "R47") (pin "2") (pinfunction "2_2") (pintype "passive"))
    )
    (net (code "200") (name "Net-(D8-K)") (class "Default")
      (node (ref "D8") (pin "2") (pinfunction "K_2") (pintype "passive"))
      (node (ref "R48") (pin "2") (pinfunction "2_2") (pintype "passive"))
    )
    (net (code "201") (name "Net-(P1-X)") (class "Default")
      (node (ref "P1") (pin "1") (pinfunction "X_1") (pintype "passive"))
      (node (ref "U12") (pin "3") (pinfunction "A_3") (pintype "passive"))
    )
    (net (code "202") (name "Net-(P2-X)") (class "Default")
      (node (ref "P2") (pin "1") (pinfunction "X_1") (pintype "passive"))
      (node (ref "U13") (pin "3") (pinfunction "A_3") (pintype "passive"))
    )
    (net (code "203") (name "Net-(P3-X)") (class "Default")
      (node (ref "P3") (pin "1") (pinfunction "X_1") (pintype "passive"))
      (node (ref "U14") (pin "3") (pinfunction "A_3") (pintype "passive"))
    )
    (net (code "204") (name "Net-(P4-X)") (class "Default")
      (node (ref "P4") (pin "1") (pinfunction "X_1") (pintype "passive"))
      (node (ref "U15") (pin "3") (pinfunction "A_3") (pintype "passive"))
    )
    (net (code "205") (name "unconnected-(P5-Pad38)") (class "Default")
      (node (ref "P5") (pin "38") (pinfunction "38_38") (pintype "passive"))
    )
    (net (code "206") (name "unconnected-(P5-Pad39)") (class "Default")
      (node (ref "P5") (pin "39") (pinfunction "39_39") (pintype "passive"))
    )
    (net (code "207") (name "unconnected-(P7-Pad2)") (class "Default")
      (node (ref "P7") (pin "2") (pinfunction "2_2") (pintype "passive"))
    )
    (net (code "208") (name "unconnected-(P7-Pad3)") (class "Default")
      (node (ref "P7") (pin "3") (pinfunction "3_3") (pintype "passive"))
    )
    (net (code "209") (name "unconnected-(P7-Pad4)") (class "Default")
      (node (ref "P7") (pin "4") (pinfunction "4_4") (pintype "passive"))
    )
    (net (code "210") (name "unconnected-(P7-Pad5)") (class "Default")
      (node (ref "P7") (pin "5") (pinfunction "5_5") (pintype "passive"))
    )
    (net (code "211") (name "unconnected-(P7-Pad6)") (class "Default")
      (node (ref "P7") (pin "6") (pinfunction "6_6") (pintype "passive"))
    )
    (net (code "212") (name "unconnected-(P7-Pad7)") (class "Default")
      (node (ref "P7") (pin "7") (pinfunction "7_7") (pintype "passive"))
    )
    (net (code "213") (name "unconnected-(P7-Pad8)") (class "Default")
      (node (ref "P7") (pin "8") (pinfunction "8_8") (pintype "passive"))
    )
    (net (code "214") (name "unconnected-(P7-Pad9)") (class "Default")
      (node (ref "P7") (pin "9") (pinfunction "9_9") (pintype "passive"))
    )
    (net (code "215") (name "unconnected-(P7-Pad10)") (class "Default")
      (node (ref "P7") (pin "10") (pinfunction "10_10") (pintype "passive"))
    )
    (net (code "216") (name "unconnected-(P7-Pad12)") (class "Default")
      (node (ref "P7") (pin "12") (pinfunction "12_12") (pintype "passive"))
    )
    (net (code "217") (name "unconnected-(P7-Pad21)") (class "Default")
      (node (ref "P7") (pin "21") (pinfunction "21_21") (pintype "passive"))
    )
    (net (code "218") (name "unconnected-(P7-Pad22)") (class "Default")
      (node (ref "P7") (pin "22") (pinfunction "22_22") (pintype "passive"))
    )
    (net (code "219") (name "unconnected-(P7-Pad23)") (class "Default")
      (node (ref "P7") (pin "23") (pinfunction "23_23") (pintype "passive"))
    )
    (net (code "220") (name "unconnected-(P7-Pad24)") (class "Default")
      (node (ref "P7") (pin "24") (pinfunction "24_24") (pintype "passive"))
    )
    (net (code "221") (name "unconnected-(P7-Pad35)") (class "Default")
      (node (ref "P7") (pin "35") (pinfunction "35_35") (pintype "passive"))
    )
    (net (code "222") (name "unconnected-(P7-Pad37)") (class "Default")
      (node (ref "P7") (pin "37") (pinfunction "37_37") (pintype "passive"))
    )
    (net (code "223") (name "unconnected-(P7-Pad38)") (class "Default")
      (node (ref "P7") (pin "38") (pinfunction "38_38") (pintype "passive"))
    )
    (net (code "224") (name "unconnected-(P7-Pad39)") (class "Default")
      (node (ref "P7") (pin "39") (pinfunction "39_39") (pintype "passive"))
    )
    (net (code "225") (name "unconnected-(P7-Pad40)") (class "Default")
      (node (ref "P7") (pin "40") (pinfunction "40_40") (pintype "passive"))
    )
    (net (code "226") (name "unconnected-(P8-Pad1)") (class "Default")
      (node (ref "P8") (pin "1") (pinfunction "1_1") (pintype "passive"))
    )
    (net (code "227") (name "unconnected-(P8-Pad3)") (class "Default")
      (node (ref "P8") (pin "3") (pinfunction "3_3") (pintype "passive"))
    )
    (net (code "228") (name "unconnected-(P8-Pad4)") (class "Default")
      (node (ref "P8") (pin "4") (pinfunction "4_4") (pintype "passive"))
    )
    (net (code "229") (name "unconnected-(P8-Pad5)") (class "Default")
      (node (ref "P8") (pin "5") (pinfunction "5_5") (pintype "passive"))
    )
    (net (code "230") (name "unconnected-(P8-Pad6)") (class "Default")
      (node (ref "P8") (pin "6") (pinfunction "6_6") (pintype "passive"))
    )
    (net (code "231") (name "unconnected-(P8-Pad7)") (class "Default")
      (node (ref "P8") (pin "7") (pinfunction "7_7") (pintype "passive"))
    )
    (net (code "232") (name "unconnected-(P8-Pad8)") (class "Default")
      (node (ref "P8") (pin "8") (pinfunction "8_8") (pintype "passive"))
    )
    (net (code "233") (name "unconnected-(P8-Pad9)") (class "Default")
      (node (ref "P8") (pin "9") (pinfunction "9_9") (pintype "passive"))
    )
    (net (code "234") (name "unconnected-(P8-Pad10)") (class "Default")
      (node (ref "P8") (pin "10") (pinfunction "10_10") (pintype "passive"))
    )
    (net (code "235") (name "unconnected-(P8-Pad11)") (class "Default")
      (node (ref "P8") (pin "11") (pinfunction "11_11") (pintype "passive"))
    )
    (net (code "236") (name "unconnected-(P8-Pad12)") (class "Default")
      (node (ref "P8") (pin "12") (pinfunction "12_12") (pintype "passive"))
    )
    (net (code "237") (name "unconnected-(P8-Pad13)") (class "Default")
      (node (ref "P8") (pin "13") (pinfunction "13_13") (pintype "passive"))
    )
    (net (code "238") (name "unconnected-(P8-Pad15)") (class "Default")
      (node (ref "P8") (pin "15") (pinfunction "15_15") (pintype "passive"))
    )
    (net (code "239") (name "unconnected-(P8-Pad16)") (class "Default")
      (node (ref "P8") (pin "16") (pinfunction "16_16") (pintype "passive"))
    )
    (net (code "240") (name "unconnected-(P8-Pad17)") (class "Default")
      (node (ref "P8") (pin "17") (pinfunction "17_17") (pintype "passive"))
    )
    (net (code "241") (name "unconnected-(P8-Pad18)") (class "Default")
      (node (ref "P8") (pin "18") (pinfunction "18_18") (pintype "passive"))
    )
    (net (code "242") (name "unconnected-(P8-Pad36)") (class "Default")
      (node (ref "P8") (pin "36") (pinfunction "36_36") (pintype "passive"))
    )
    (net (code "243") (name "unconnected-(P8-Pad39)") (class "Default")
      (node (ref "P8") (pin "39") (pinfunction "39_39") (pintype "passive"))
    )
    (net (code "244") (name "unconnected-(P8-Pad40)") (class "Default")
      (node (ref "P8") (pin "40") (pinfunction "40_40") (pintype "passive"))
    )
    (net (code "245") (name "unconnected-(P9-Pad15)") (class "Default")
      (node (ref "P9") (pin "15") (pinfunction "15_15") (pintype "passive"))
    )
    (net (code "246") (name "unconnected-(P9-Pad27)") (class "Default")
      (node (ref "P9") (pin "27") (pinfunction "27_27") (pintype "passive"))
    )
    (net (code "247") (name "unconnected-(P9-Pad28)") (class "Default")
      (node (ref "P9") (pin "28") (pinfunction "28_28") (pintype "passive"))
    )
    (net (code "248") (name "unconnected-(P9-Pad29)") (class "Default")
      (node (ref "P9") (pin "29") (pinfunction "29_29") (pintype "passive"))
    )
    (net (code "249") (name "unconnected-(P9-Pad30)") (class "Default")
      (node (ref "P9") (pin "30") (pinfunction "30_30") (pintype "passive"))
    )
    (net (code "250") (name "unconnected-(P9-Pad31)") (class "Default")
      (node (ref "P9") (pin "31") (pinfunction "31_31") (pintype "passive"))
    )
    (net (code "251") (name "unconnected-(P9-Pad33)") (class "Default")
      (node (ref "P9") (pin "33") (pinfunction "33_33") (pintype "passive"))
    )
    (net (code "252") (name "unconnected-(P9-Pad35)") (class "Default")
      (node (ref "P9") (pin "35") (pinfunction "35_35") (pintype "passive"))
    )
    (net (code "253") (name "unconnected-(P9-Pad37)") (class "Default")
      (node (ref "P9") (pin "37") (pinfunction "37_37") (pintype "passive"))
    )
    (net (code "254") (name "unconnected-(P9-Pad39)") (class "Default")
      (node (ref "P9") (pin "39") (pinfunction "39_39") (pintype "passive"))
    )
    (net (code "255") (name "unconnected-(P10-Pad16)") (class "Default")
      (node (ref "P10") (pin "16") (pinfunction "16_16") (pintype "passive"))
    )
    (net (code "256") (name "unconnected-(P10-Pad37)") (class "Default")
      (node (ref "P10") (pin "37") (pinfunction "37_37") (pintype "passive"))
    )
    (net (code "257") (name "unconnected-(P10-Pad39)") (class "Default")
      (node (ref "P10") (pin "39") (pinfunction "39_39") (pintype "passive"))
    )
    (net (code "258") (name "unconnected-(U11-1.2V-Pad1A4)") (class "Default")
      (node (ref "U11") (pin "1A4") (pinfunction "1.2V_1A4") (pintype "passive"))
    )
    (net (code "259") (name "unconnected-(U11-1.8V-Pad1A6)") (class "Default")
      (node (ref "U11") (pin "1A6") (pinfunction "1.8V_1A6") (pintype "passive"))
    )
    (net (code "260") (name "unconnected-(U11-2.5V-Pad2A18)") (class "Default")
      (node (ref "U11") (pin "2A18") (pinfunction "2.5V_2A18") (pintype "passive"))
    )
    (net (code "261") (name "unconnected-(U11-3.3V-Pad1B1)") (class "Default")
      (node (ref "U11") (pin "1B1") (pinfunction "3.3V_1B1") (pintype "passive"))
    )
    (net (code "262") (name "unconnected-(U11-3.3V-Pad2A1)") (class "Default")
      (node (ref "U11") (pin "2A1") (pinfunction "3.3V_2A1") (pintype "passive"))
    )
    (net (code "263") (name "unconnected-(U11-3.3V-Pad2B1)") (class "Default")
      (node (ref "U11") (pin "2B1") (pinfunction "3.3V_2B1") (pintype "passive"))
    )
    (net (code "264") (name "unconnected-(U11-3.3V-Pad2C1)") (class "Default")
      (node (ref "U11") (pin "2C1") (pinfunction "3.3V_2C1") (pintype "passive"))
    )
    (net (code "265") (name "unconnected-(U11-AA1{slash}L31n-Pad1B32)") (class "Default")
      (node (ref "U11") (pin "1B32") (pinfunction "AA1/L31n_1B32") (pintype "passive"))
    )
    (net (code "266") (name "unconnected-(U11-AA3{slash}CLKOUT-Pad1A19)") (class "Default")
      (node (ref "U11") (pin "1A19") (pinfunction "AA3/CLKOUT_1A19") (pintype "passive"))
    )
    (net (code "267") (name "unconnected-(U11-AA13{slash}B23p-Pad2A32)") (class "Default")
      (node (ref "U11") (pin "2A32") (pinfunction "AA13/B23p_2A32") (pintype "passive"))
    )
    (net (code "268") (name "unconnected-(U11-AB3{slash}CLKOUT-Pad1A21)") (class "Default")
      (node (ref "U11") (pin "1A21") (pinfunction "AB3/CLKOUT_1A21") (pintype "passive"))
    )
    (net (code "269") (name "unconnected-(U11-AB13{slash}B23n-Pad2A34)") (class "Default")
      (node (ref "U11") (pin "2A34") (pinfunction "AB13/B23n_2A34") (pintype "passive"))
    )
    (net (code "270") (name "unconnected-(U11-AB18{slash}IO-Pad2A30)") (class "Default")
      (node (ref "U11") (pin "2A30") (pinfunction "AB18/IO_2A30") (pintype "passive"))
    )
    (net (code "271") (name "unconnected-(U11-B11{slash}CLKIN-Pad1A13)") (class "Default")
      (node (ref "U11") (pin "1A13") (pinfunction "B11/CLKIN_1A13") (pintype "passive"))
    )
    (net (code "272") (name "unconnected-(U11-B21{slash}R3p-Pad2C23)") (class "Default")
      (node (ref "U11") (pin "2C23") (pinfunction "B21/R3p_2C23") (pintype "passive"))
    )
    (net (code "273") (name "unconnected-(U11-B22{slash}R3n-Pad2C25)") (class "Default")
      (node (ref "U11") (pin "2C25") (pinfunction "B22/R3n_2C25") (pintype "passive"))
    )
    (net (code "274") (name "unconnected-(U11-C20{slash}R2n-Pad2C29)") (class "Default")
      (node (ref "U11") (pin "2C29") (pinfunction "C20/R2n_2C29") (pintype "passive"))
    )
    (net (code "275") (name "unconnected-(U11-C22{slash}R4n-Pad2C21)") (class "Default")
      (node (ref "U11") (pin "2C21") (pinfunction "C22/R4n_2C21") (pintype "passive"))
    )
    (net (code "276") (name "unconnected-(U11-CHARGE_DET-Pad2A17)") (class "Default")
      (node (ref "U11") (pin "2A17") (pinfunction "CHARGE_DET_2A17") (pintype "passive"))
    )
    (net (code "277") (name "unconnected-(U11-D20{slash}R2p-Pad2C27)") (class "Default")
      (node (ref "U11") (pin "2C27") (pinfunction "D20/R2p_2C27") (pintype "passive"))
    )
    (net (code "278") (name "unconnected-(U11-F17{slash}R1n-Pad2C33)") (class "Default")
      (node (ref "U11") (pin "2C33") (pinfunction "F17/R1n_2C33") (pintype "passive"))
    )
    (net (code "279") (name "unconnected-(U11-G17{slash}R1p-Pad2C31)") (class "Default")
      (node (ref "U11") (pin "2C31") (pinfunction "G17/R1p_2C31") (pintype "passive"))
    )
    (net (code "280") (name "unconnected-(U11-GND-Pad1A39)") (class "Default")
      (node (ref "U11") (pin "1A39") (pinfunction "GND_1A39") (pintype "passive"))
    )
    (net (code "281") (name "unconnected-(U11-HSMC_VS0-Pad1A10)") (class "Default")
      (node (ref "U11") (pin "1A10") (pinfunction "HSMC_VS0_1A10") (pintype "passive"))
    )
    (net (code "282") (name "unconnected-(U11-HSMC_VS0-Pad2A10)") (class "Default")
      (node (ref "U11") (pin "2A10") (pinfunction "HSMC_VS0_2A10") (pintype "passive"))
    )
    (net (code "283") (name "unconnected-(U11-HSMC_VS1-Pad1A12)") (class "Default")
      (node (ref "U11") (pin "1A12") (pinfunction "HSMC_VS1_1A12") (pintype "passive"))
    )
    (net (code "284") (name "unconnected-(U11-HSMC_VS1-Pad2A12)") (class "Default")
      (node (ref "U11") (pin "2A12") (pinfunction "HSMC_VS1_2A12") (pintype "passive"))
    )
    (net (code "285") (name "unconnected-(U11-HSMC_VS2-Pad1A14)") (class "Default")
      (node (ref "U11") (pin "1A14") (pinfunction "HSMC_VS2_1A14") (pintype "passive"))
    )
    (net (code "286") (name "unconnected-(U11-HSMC_VS2-Pad2A14)") (class "Default")
      (node (ref "U11") (pin "2A14") (pinfunction "HSMC_VS2_2A14") (pintype "passive"))
    )
    (net (code "287") (name "unconnected-(U11-J17{slash}IO-Pad2C38)") (class "Default")
      (node (ref "U11") (pin "2C38") (pinfunction "J17/IO_2C38") (pintype "passive"))
    )
    (net (code "288") (name "unconnected-(U11-J18{slash}R12n-Pad2C36)") (class "Default")
      (node (ref "U11") (pin "2C36") (pinfunction "J18/R12n_2C36") (pintype "passive"))
    )
    (net (code "289") (name "unconnected-(U11-J19{slash}R10p-Pad2A35)") (class "Default")
      (node (ref "U11") (pin "2A35") (pinfunction "J19/R10p_2A35") (pintype "passive"))
    )
    (net (code "290") (name "unconnected-(U11-J20{slash}R10n-Pad2A37)") (class "Default")
      (node (ref "U11") (pin "2A37") (pinfunction "J20/R10n_2A37") (pintype "passive"))
    )
    (net (code "291") (name "unconnected-(U11-JTAG_TCK-Pad1A25)") (class "Default")
      (node (ref "U11") (pin "1A25") (pinfunction "JTAG_TCK_1A25") (pintype "passive"))
    )
    (net (code "292") (name "unconnected-(U11-JTAG_TCK-Pad2A25)") (class "Default")
      (node (ref "U11") (pin "2A25") (pinfunction "JTAG_TCK_2A25") (pintype "passive"))
    )
    (net (code "293") (name "unconnected-(U11-JTAG_TDI-Pad1A24)") (class "Default")
      (node (ref "U11") (pin "1A24") (pinfunction "JTAG_TDI_1A24") (pintype "passive"))
    )
    (net (code "294") (name "unconnected-(U11-JTAG_TDI-Pad2A24)") (class "Default")
      (node (ref "U11") (pin "2A24") (pinfunction "JTAG_TDI_2A24") (pintype "passive"))
    )
    (net (code "295") (name "unconnected-(U11-JTAG_TDO-Pad1A27)") (class "Default")
      (node (ref "U11") (pin "1A27") (pinfunction "JTAG_TDO_1A27") (pintype "passive"))
    )
    (net (code "296") (name "unconnected-(U11-JTAG_TDO-Pad2A27)") (class "Default")
      (node (ref "U11") (pin "2A27") (pinfunction "JTAG_TDO_2A27") (pintype "passive"))
    )
    (net (code "297") (name "unconnected-(U11-JTAG_TMC-Pad1A22)") (class "Default")
      (node (ref "U11") (pin "1A22") (pinfunction "JTAG_TMC_1A22") (pintype "passive"))
    )
    (net (code "298") (name "unconnected-(U11-JTAG_TMC-Pad2A22)") (class "Default")
      (node (ref "U11") (pin "2A22") (pinfunction "JTAG_TMC_2A22") (pintype "passive"))
    )
    (net (code "299") (name "unconnected-(U11-K21{slash}R16p-Pad2C35)") (class "Default")
      (node (ref "U11") (pin "2C35") (pinfunction "K21/R16p_2C35") (pintype "passive"))
    )
    (net (code "300") (name "unconnected-(U11-K22{slash}R16n-Pad2C37)") (class "Default")
      (node (ref "U11") (pin "2C37") (pinfunction "K22/R16n_2C37") (pintype "passive"))
    )
    (net (code "301") (name "unconnected-(U11-N5{slash}L22n-Pad1C36)") (class "Default")
      (node (ref "U11") (pin "1C36") (pinfunction "N5/L22n_1C36") (pintype "passive"))
    )
    (net (code "302") (name "unconnected-(U11-N7{slash}L30p-Pad1C15)") (class "Default")
      (node (ref "U11") (pin "1C15") (pinfunction "N7/L30p_1C15") (pintype "passive"))
    )
    (net (code "303") (name "unconnected-(U11-N17{slash}R21n-Pad2C26)") (class "Default")
      (node (ref "U11") (pin "2C26") (pinfunction "N17/R21n_2C26") (pintype "passive"))
    )
    (net (code "304") (name "unconnected-(U11-N18{slash}R21p-Pad2C24)") (class "Default")
      (node (ref "U11") (pin "2C24") (pinfunction "N18/R21p_2C24") (pintype "passive"))
    )
    (net (code "305") (name "unconnected-(U11-N20{slash}R22n-Pad2C22)") (class "Default")
      (node (ref "U11") (pin "2C22") (pinfunction "N20/R22n_2C22") (pintype "passive"))
    )
    (net (code "306") (name "unconnected-(U11-OVP_FLAG-Pad1A17)") (class "Default")
      (node (ref "U11") (pin "1A17") (pinfunction "OVP_FLAG_1A17") (pintype "passive"))
    )
    (net (code "307") (name "unconnected-(U11-P5{slash}L26p-Pad1C38)") (class "Default")
      (node (ref "U11") (pin "1C38") (pinfunction "P5/L26p_1C38") (pintype "passive"))
    )
    (net (code "308") (name "unconnected-(U11-P6{slash}L32p-Pad1C19)") (class "Default")
      (node (ref "U11") (pin "1C19") (pinfunction "P6/L32p_1C19") (pintype "passive"))
    )
    (net (code "309") (name "unconnected-(U11-P7{slash}L30n-Pad1C17)") (class "Default")
      (node (ref "U11") (pin "1C17") (pinfunction "P7/L30n_1C17") (pintype "passive"))
    )
    (net (code "310") (name "unconnected-(U11-Pad1A8)") (class "Default")
      (node (ref "U11") (pin "1A8") (pintype "passive"))
    )
    (net (code "311") (name "unconnected-(U11-Pad1A15)") (class "Default")
      (node (ref "U11") (pin "1A15") (pintype "passive"))
    )
    (net (code "312") (name "unconnected-(U11-Pad1A16)") (class "Default")
      (node (ref "U11") (pin "1A16") (pintype "passive"))
    )
    (net (code "313") (name "unconnected-(U11-Pad1A18)") (class "Default")
      (node (ref "U11") (pin "1A18") (pintype "passive"))
    )
    (net (code "314") (name "unconnected-(U11-Pad1A36)") (class "Default")
      (node (ref "U11") (pin "1A36") (pintype "passive"))
    )
    (net (code "315") (name "unconnected-(U11-Pad1A38)") (class "Default")
      (node (ref "U11") (pin "1A38") (pintype "passive"))
    )
    (net (code "316") (name "unconnected-(U11-R4{slash}L27p-Pad1C3)") (class "Default")
      (node (ref "U11") (pin "1C3") (pinfunction "R4/L27p_1C3") (pintype "passive"))
    )
    (net (code "317") (name "unconnected-(U11-R5{slash}L32n-Pad1C21)") (class "Default")
      (node (ref "U11") (pin "1C21") (pinfunction "R5/L32n_1C21") (pintype "passive"))
    )
    (net (code "318") (name "unconnected-(U11-R6{slash}L33n-Pad1C37)") (class "Default")
      (node (ref "U11") (pin "1C37") (pinfunction "R6/L33n_1C37") (pintype "passive"))
    )
    (net (code "319") (name "unconnected-(U11-R14{slash}B41p-Pad2C28)") (class "Default")
      (node (ref "U11") (pin "2C28") (pinfunction "R14/B41p_2C28") (pintype "passive"))
    )
    (net (code "320") (name "unconnected-(U11-R15{slash}B41n-Pad2C30)") (class "Default")
      (node (ref "U11") (pin "2C30") (pinfunction "R15/B41n_2C30") (pintype "passive"))
    )
    (net (code "321") (name "unconnected-(U11-R16{slash}IO{slash}CLKOUT-Pad2A21)") (class "Default")
      (node (ref "U11") (pin "2A21") (pinfunction "R16/IO/CLKOUT_2A21") (pintype "passive"))
    )
    (net (code "322") (name "unconnected-(U11-R17{slash}R30n-Pad1C22)") (class "Default")
      (node (ref "U11") (pin "1C22") (pinfunction "R17/R30n_1C22") (pintype "passive"))
    )
    (net (code "323") (name "unconnected-(U11-R18{slash}R26n-Pad1B33)") (class "Default")
      (node (ref "U11") (pin "1B33") (pinfunction "R18/R26n_1B33") (pintype "passive"))
    )
    (net (code "324") (name "unconnected-(U11-T5{slash}L33p-Pad1C35)") (class "Default")
      (node (ref "U11") (pin "1C35") (pinfunction "T5/L33p_1C35") (pintype "passive"))
    )
    (net (code "325") (name "unconnected-(U11-T10{slash}B13p-Pad1B36)") (class "Default")
      (node (ref "U11") (pin "1B36") (pinfunction "T10/B13p_1B36") (pintype "passive"))
    )
    (net (code "326") (name "unconnected-(U11-T11{slash}B13n-Pad1B38)") (class "Default")
      (node (ref "U11") (pin "1B38") (pinfunction "T11/B13n_1B38") (pintype "passive"))
    )
    (net (code "327") (name "unconnected-(U11-T16{slash}IO{slash}CLKOUT-Pad2A19)") (class "Default")
      (node (ref "U11") (pin "2A19") (pinfunction "T16/IO/CLKOUT_2A19") (pintype "passive"))
    )
    (net (code "328") (name "unconnected-(U11-T19{slash}R31p-Pad1C24)") (class "Default")
      (node (ref "U11") (pin "1C24") (pinfunction "T19/R31p_1C24") (pintype "passive"))
    )
    (net (code "329") (name "unconnected-(U11-T20{slash}R31n-Pad1C26)") (class "Default")
      (node (ref "U11") (pin "1C26") (pinfunction "T20/R31n_1C26") (pintype "passive"))
    )
    (net (code "330") (name "unconnected-(U11-T21{slash}CLKIN-Pad1A26)") (class "Default")
      (node (ref "U11") (pin "1A26") (pinfunction "T21/CLKIN_1A26") (pintype "passive"))
    )
    (net (code "331") (name "unconnected-(U11-T22{slash}CLKIN-Pad2A26)") (class "Default")
      (node (ref "U11") (pin "2A26") (pinfunction "T22/CLKIN_2A26") (pintype "passive"))
    )
    (net (code "332") (name "unconnected-(U11-U11{slash}B19p-Pad1C12)") (class "Default")
      (node (ref "U11") (pin "1C12") (pinfunction "U11/B19p_1C12") (pintype "passive"))
    )
    (net (code "333") (name "unconnected-(U11-U12{slash}B28p-Pad2A31)") (class "Default")
      (node (ref "U11") (pin "2A31") (pinfunction "U12/B28p_2A31") (pintype "passive"))
    )
    (net (code "334") (name "unconnected-(U11-U13{slash}B32p-Pad2A28)") (class "Default")
      (node (ref "U11") (pin "2A28") (pinfunction "U13/B32p_2A28") (pintype "passive"))
    )
    (net (code "335") (name "unconnected-(U11-U15{slash}B34p-Pad2C32)") (class "Default")
      (node (ref "U11") (pin "2C32") (pinfunction "U15/B34p_2C32") (pintype "passive"))
    )
    (net (code "336") (name "unconnected-(U11-U19{slash}R34p-Pad1C23)") (class "Default")
      (node (ref "U11") (pin "1C23") (pinfunction "U19/R34p_1C23") (pintype "passive"))
    )
    (net (code "337") (name "unconnected-(U11-U20{slash}R34n-Pad1C25)") (class "Default")
      (node (ref "U11") (pin "1C25") (pinfunction "U20/R34n_1C25") (pintype "passive"))
    )
    (net (code "338") (name "unconnected-(U11-U21{slash}R27p-Pad1C32)") (class "Default")
      (node (ref "U11") (pin "1C32") (pinfunction "U21/R27p_1C32") (pintype "passive"))
    )
    (net (code "339") (name "unconnected-(U11-U22{slash}R27n-Pad1C34)") (class "Default")
      (node (ref "U11") (pin "1C34") (pinfunction "U22/R27n_1C34") (pintype "passive"))
    )
    (net (code "340") (name "unconnected-(U11-V1{slash}L25n-Pad1B37)") (class "Default")
      (node (ref "U11") (pin "1B37") (pinfunction "V1/L25n_1B37") (pintype "passive"))
    )
    (net (code "341") (name "unconnected-(U11-V2{slash}L25p-Pad1B35)") (class "Default")
      (node (ref "U11") (pin "1B35") (pinfunction "V2/L25p_1B35") (pintype "passive"))
    )
    (net (code "342") (name "unconnected-(U11-V11{slash}B19n-Pad1C14)") (class "Default")
      (node (ref "U11") (pin "1C14") (pinfunction "V11/B19n_1C14") (pintype "passive"))
    )
    (net (code "343") (name "unconnected-(U11-V13{slash}B31p-Pad2A29)") (class "Default")
      (node (ref "U11") (pin "2A29") (pinfunction "V13/B31p_2A29") (pintype "passive"))
    )
    (net (code "344") (name "unconnected-(U11-V15{slash}B43n-Pad2C34)") (class "Default")
      (node (ref "U11") (pin "2C34") (pinfunction "V15/B43n_2C34") (pintype "passive"))
    )
    (net (code "345") (name "unconnected-(U11-V21{slash}R29p-Pad1C28)") (class "Default")
      (node (ref "U11") (pin "1C28") (pinfunction "V21/R29p_1C28") (pintype "passive"))
    )
    (net (code "346") (name "unconnected-(U11-V22{slash}R29n-Pad1C30)") (class "Default")
      (node (ref "U11") (pin "1C30") (pinfunction "V22/R29n_1C30") (pintype "passive"))
    )
    (net (code "347") (name "unconnected-(U11-VCCIO-Pad1A3)") (class "Default")
      (node (ref "U11") (pin "1A3") (pinfunction "VCCIO_1A3") (pintype "passive"))
    )
    (net (code "348") (name "unconnected-(U11-VCCIO-Pad1A5)") (class "Default")
      (node (ref "U11") (pin "1A5") (pinfunction "VCCIO_1A5") (pintype "passive"))
    )
    (net (code "349") (name "unconnected-(U11-VCCIO-Pad1A40)") (class "Default")
      (node (ref "U11") (pin "1A40") (pinfunction "VCCIO_1A40") (pintype "passive"))
    )
    (net (code "350") (name "unconnected-(U11-VCCIO-Pad1B40)") (class "Default")
      (node (ref "U11") (pin "1B40") (pinfunction "VCCIO_1B40") (pintype "passive"))
    )
    (net (code "351") (name "unconnected-(U11-VCCIO-Pad1C40)") (class "Default")
      (node (ref "U11") (pin "1C40") (pinfunction "VCCIO_1C40") (pintype "passive"))
    )
    (net (code "352") (name "unconnected-(U11-VCCIO-Pad2A7)") (class "Default")
      (node (ref "U11") (pin "2A7") (pinfunction "VCCIO_2A7") (pintype "passive"))
    )
    (net (code "353") (name "unconnected-(U11-VCCIO-Pad2A9)") (class "Default")
      (node (ref "U11") (pin "2A9") (pinfunction "VCCIO_2A9") (pintype "passive"))
    )
    (net (code "354") (name "unconnected-(U11-VCCIO-Pad2A11)") (class "Default")
      (node (ref "U11") (pin "2A11") (pinfunction "VCCIO_2A11") (pintype "passive"))
    )
    (net (code "355") (name "unconnected-(U11-VCCIO-Pad2A40)") (class "Default")
      (node (ref "U11") (pin "2A40") (pinfunction "VCCIO_2A40") (pintype "passive"))
    )
    (net (code "356") (name "unconnected-(U11-VCCIO-Pad2B40)") (class "Default")
      (node (ref "U11") (pin "2B40") (pinfunction "VCCIO_2B40") (pintype "passive"))
    )
    (net (code "357") (name "unconnected-(U11-VCCIO-Pad2C40)") (class "Default")
      (node (ref "U11") (pin "2C40") (pinfunction "VCCIO_2C40") (pintype "passive"))
    )
    (net (code "358") (name "unconnected-(U11-VDC-Pad2A3)") (class "Default")
      (node (ref "U11") (pin "2A3") (pinfunction "VDC_2A3") (pintype "passive"))
    )
    (net (code "359") (name "unconnected-(U11-VDC-Pad2A5)") (class "Default")
      (node (ref "U11") (pin "2A5") (pinfunction "VDC_2A5") (pintype "passive"))
    )
    (net (code "360") (name "unconnected-(U11-VREF-Pad1A7)") (class "Default")
      (node (ref "U11") (pin "1A7") (pinfunction "VREF_1A7") (pintype "passive"))
    )
    (net (code "361") (name "unconnected-(U11-VREF-Pad1A9)") (class "Default")
      (node (ref "U11") (pin "1A9") (pinfunction "VREF_1A9") (pintype "passive"))
    )
    (net (code "362") (name "unconnected-(U11-VREF-Pad2A13)") (class "Default")
      (node (ref "U11") (pin "2A13") (pinfunction "VREF_2A13") (pintype "passive"))
    )
    (net (code "363") (name "unconnected-(U11-VREF-Pad2A15)") (class "Default")
      (node (ref "U11") (pin "2A15") (pinfunction "VREF_2A15") (pintype "passive"))
    )
    (net (code "364") (name "unconnected-(U11-VREF-Pad2A16)") (class "Default")
      (node (ref "U11") (pin "2A16") (pinfunction "VREF_2A16") (pintype "passive"))
    )
    (net (code "365") (name "unconnected-(U11-W15{slash}B35p-Pad2A33)") (class "Default")
      (node (ref "U11") (pin "2A33") (pinfunction "W15/B35p_2A33") (pintype "passive"))
    )
    (net (code "366") (name "unconnected-(U11-W21{slash}R32p-Pad1C31)") (class "Default")
      (node (ref "U11") (pin "1C31") (pinfunction "W21/R32p_1C31") (pintype "passive"))
    )
    (net (code "367") (name "unconnected-(U11-W22{slash}R32n-Pad1C33)") (class "Default")
      (node (ref "U11") (pin "1C33") (pinfunction "W22/R32n_1C33") (pintype "passive"))
    )
    (net (code "368") (name "unconnected-(U11-Y1{slash}L29n-Pad1C13)") (class "Default")
      (node (ref "U11") (pin "1C13") (pinfunction "Y1/L29n_1C13") (pintype "passive"))
    )
    (net (code "369") (name "unconnected-(U11-Y4{slash}B3p-Pad2A23)") (class "Default")
      (node (ref "U11") (pin "2A23") (pinfunction "Y4/B3p_2A23") (pintype "passive"))
    )
    (net (code "370") (name "unconnected-(U11-Y8{slash}B11p-Pad1B34)") (class "Default")
      (node (ref "U11") (pin "1B34") (pinfunction "Y8/B11p_1B34") (pintype "passive"))
    )
    (net (code "371") (name "unconnected-(U11-Y21{slash}R35p-Pad1C27)") (class "Default")
      (node (ref "U11") (pin "1C27") (pinfunction "Y21/R35p_1C27") (pintype "passive"))
    )
    (net (code "372") (name "unconnected-(U11-Y22{slash}R35n-Pad1C29)") (class "Default")
      (node (ref "U11") (pin "1C29") (pinfunction "Y22/R35n_1C29") (pintype "passive"))
    )
    (net (code "373") (name "unconnected-(U11-n{slash}c-Pad2A4)") (class "Default")
      (node (ref "U11") (pin "2A4") (pinfunction "n/c_2A4") (pintype "passive"))
    )
    (net (code "374") (name "unconnected-(U11-n{slash}c-Pad2A6)") (class "Default")
      (node (ref "U11") (pin "2A6") (pinfunction "n/c_2A6") (pintype "passive"))
    )
    (net (code "375") (name "unconnected-(U11-n{slash}c-Pad2A8)") (class "Default")
      (node (ref "U11") (pin "2A8") (pinfunction "n/c_2A8") (pintype "passive"))
    )
    (net (code "376") (name "unconnected-(U11-n{slash}c-Pad2A20)") (class "Default")
      (node (ref "U11") (pin "2A20") (pinfunction "n/c_2A20") (pintype "passive"))
    )
    (net (code "377") (name "unconnected-(U11-n{slash}c-Pad2A36)") (class "Default")
      (node (ref "U11") (pin "2A36") (pinfunction "n/c_2A36") (pintype "passive"))
    )
    (net (code "378") (name "unconnected-(U11-n{slash}c-Pad2A38)") (class "Default")
      (node (ref "U11") (pin "2A38") (pinfunction "n/c_2A38") (pintype "passive"))
    )
  )
)
